# Schematic_Central_Unit_for_AgOpenGPS.net
KiCad netlist of a schematic drawn in EasyEDA
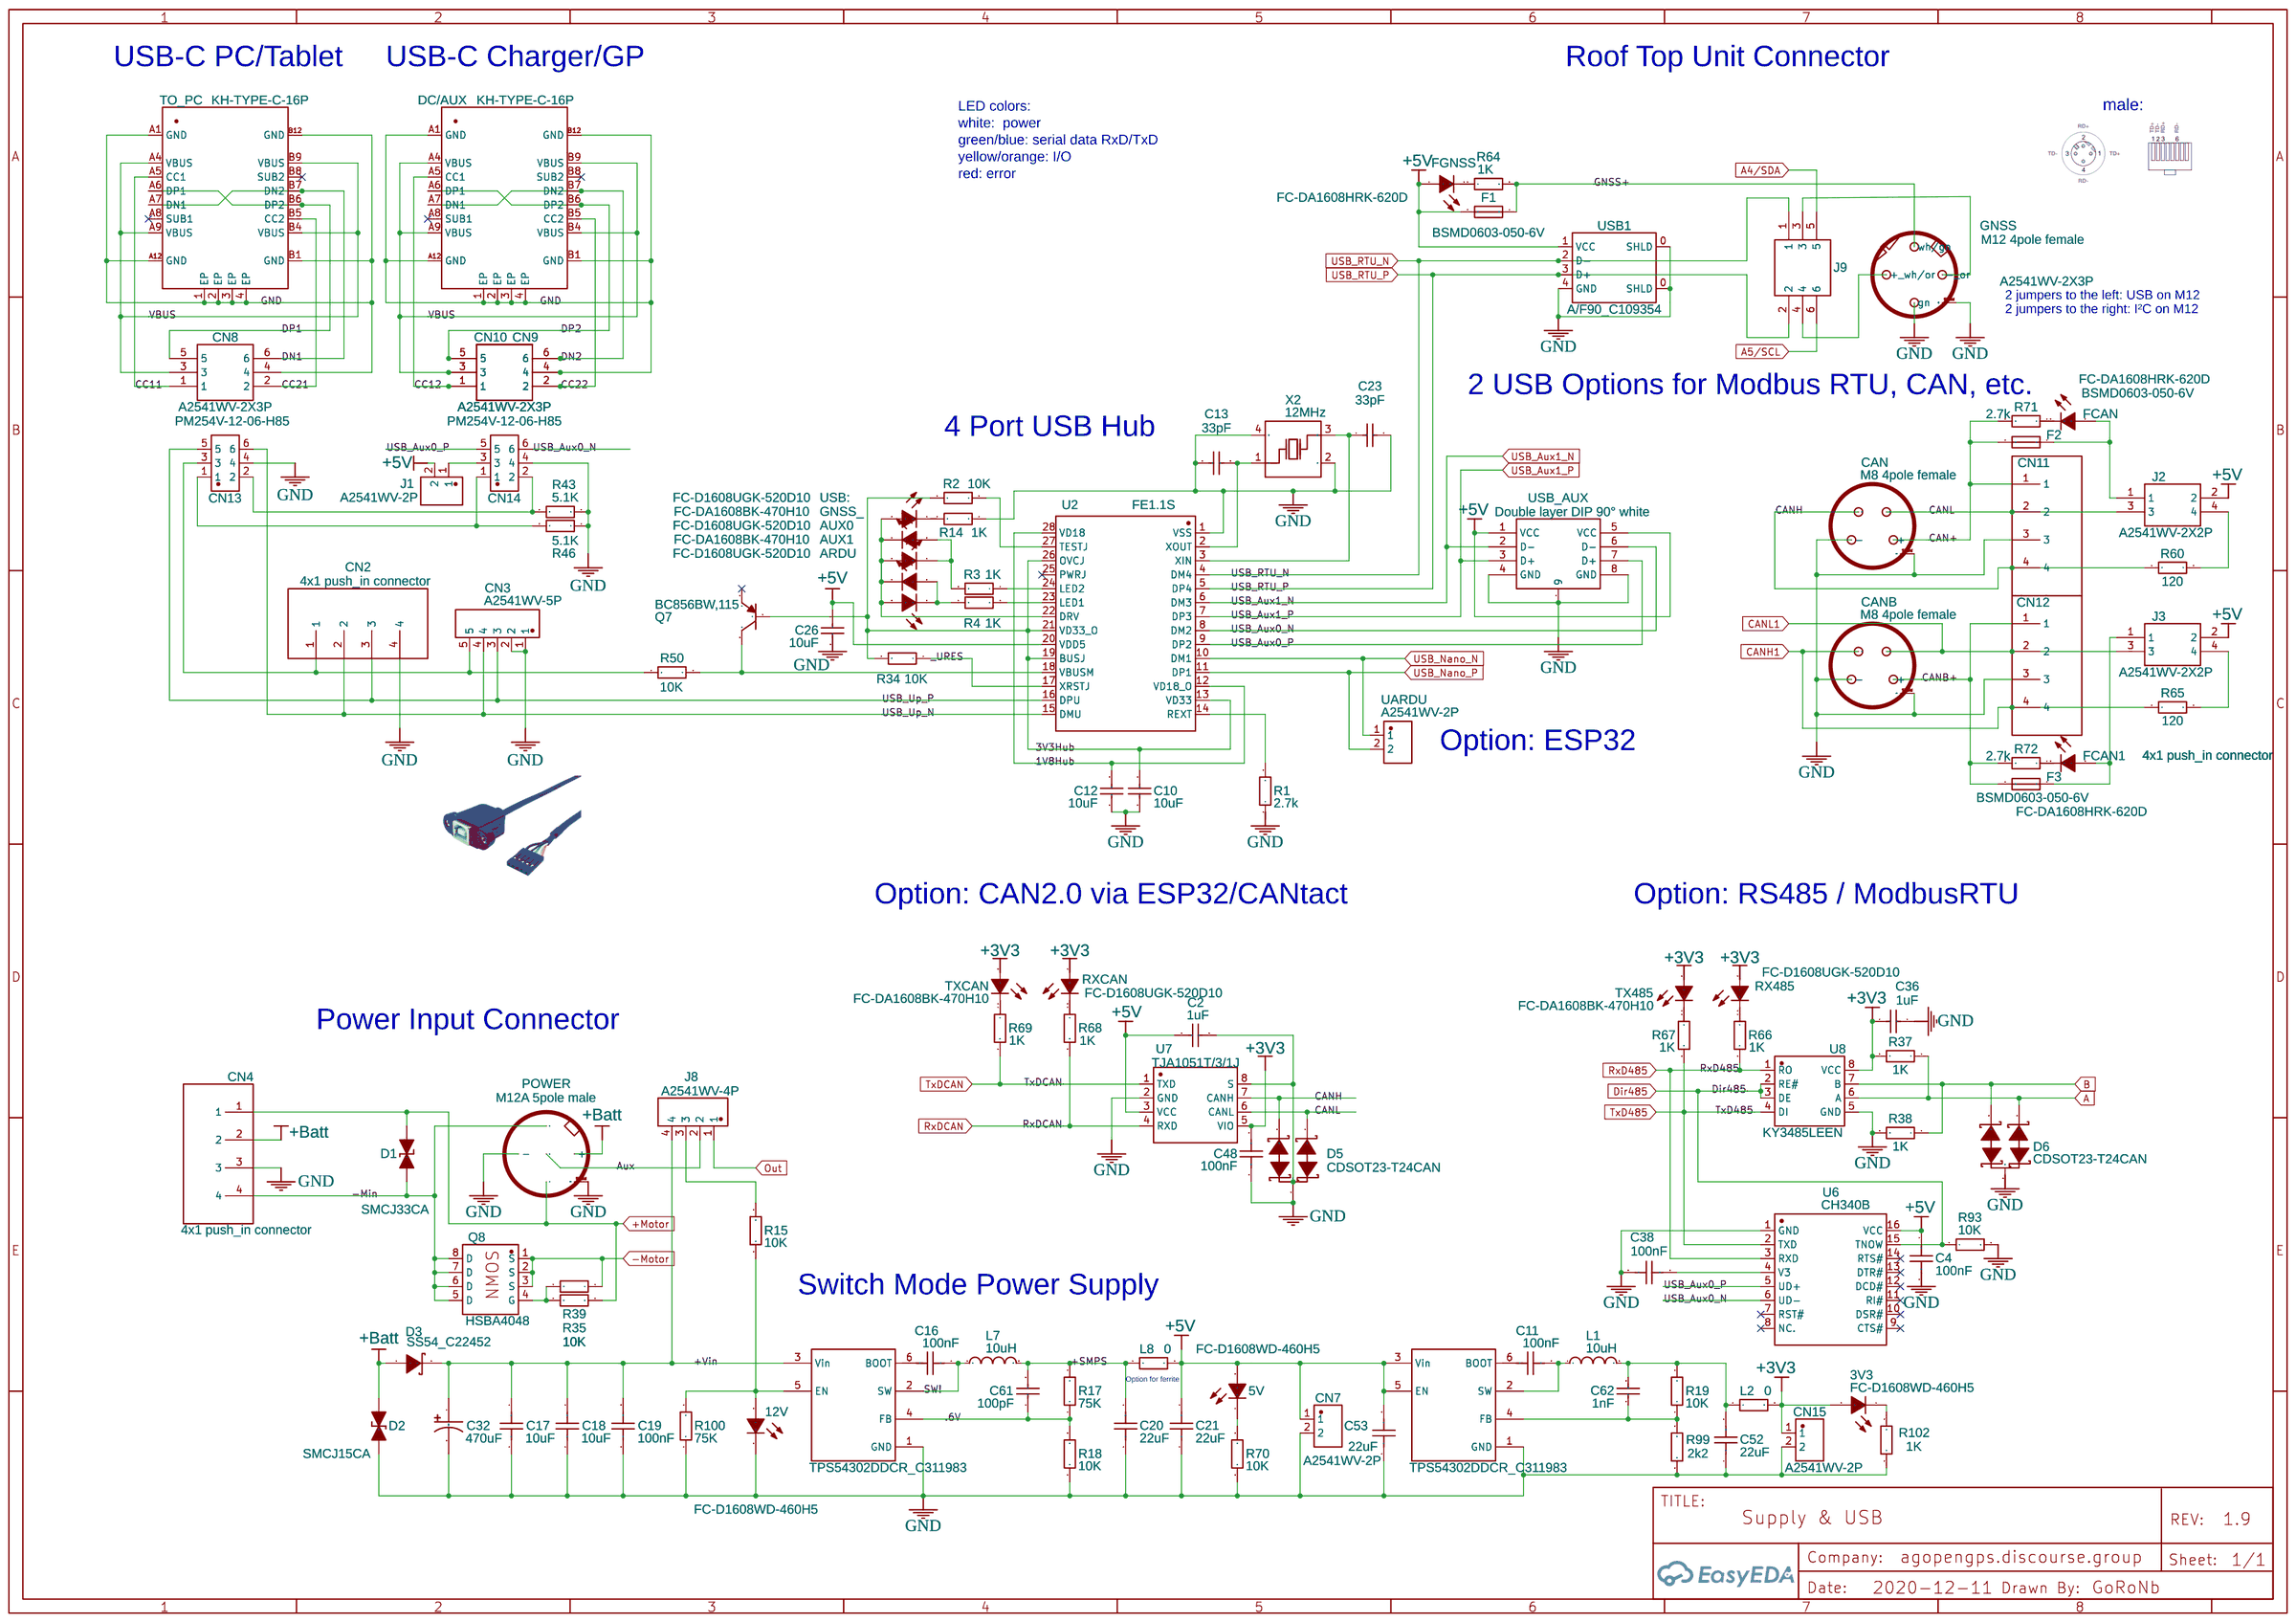
[diagram p0: Supply_USB]
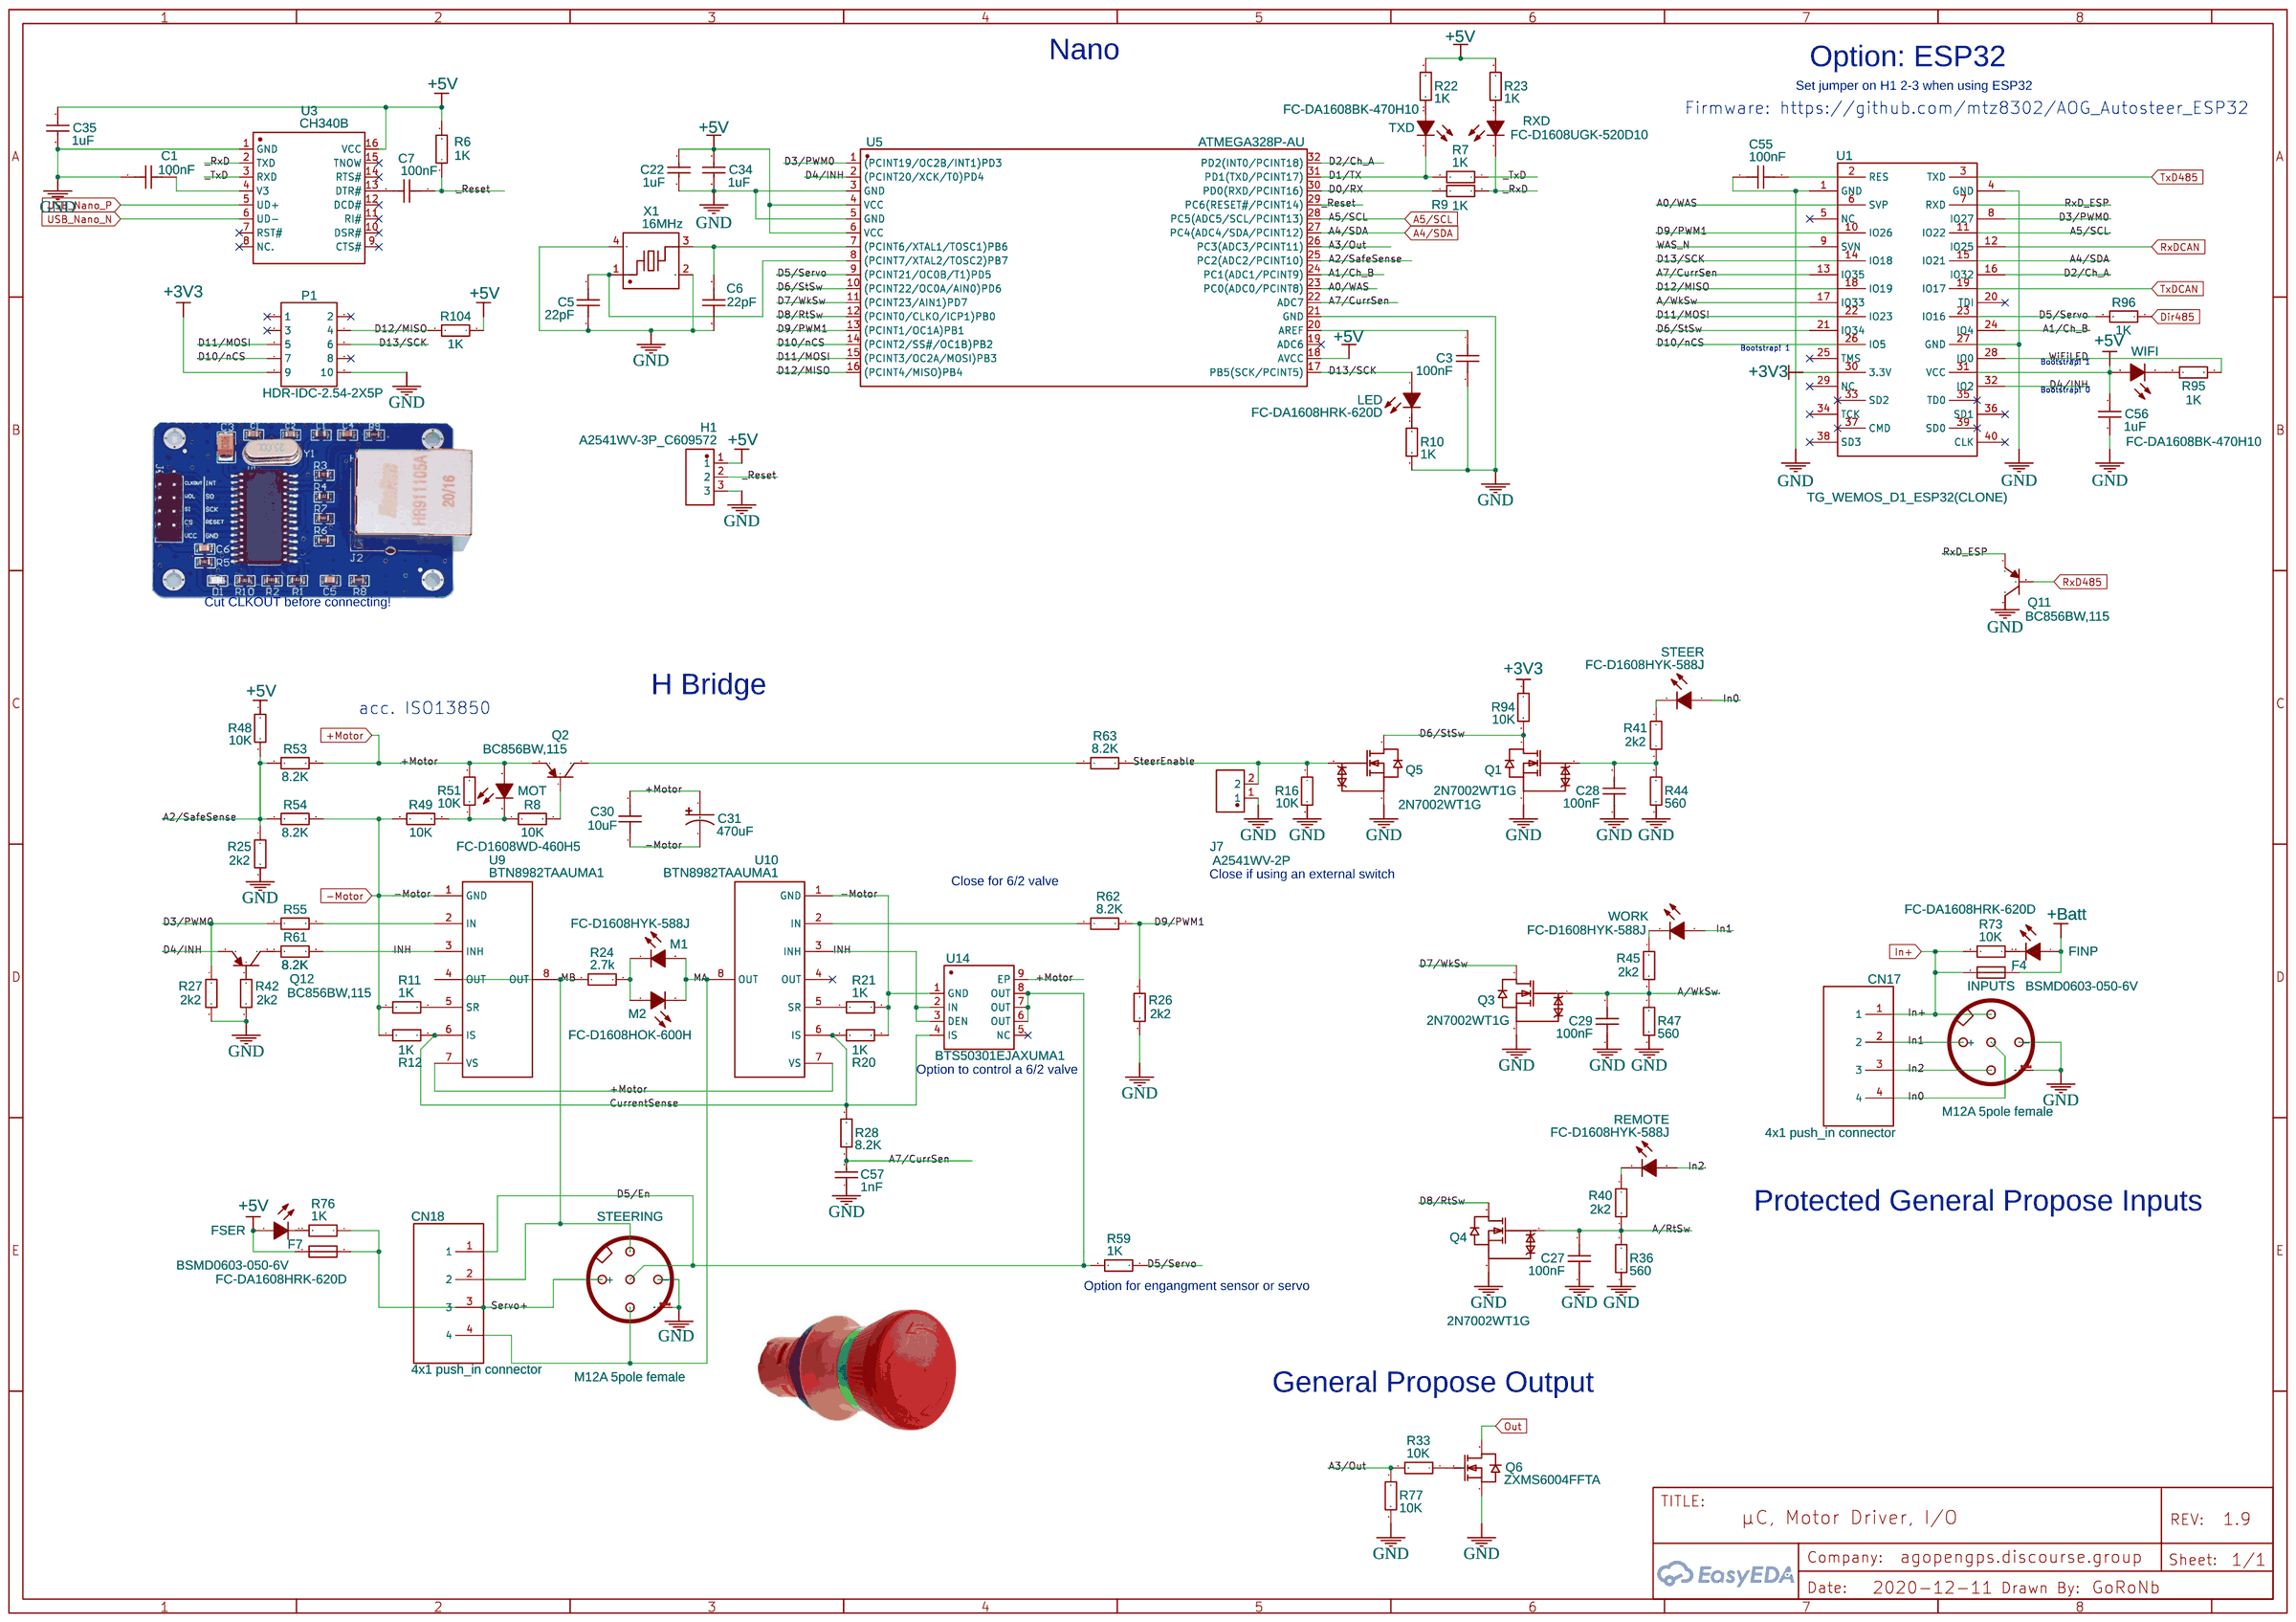
[diagram p1: Motor control]
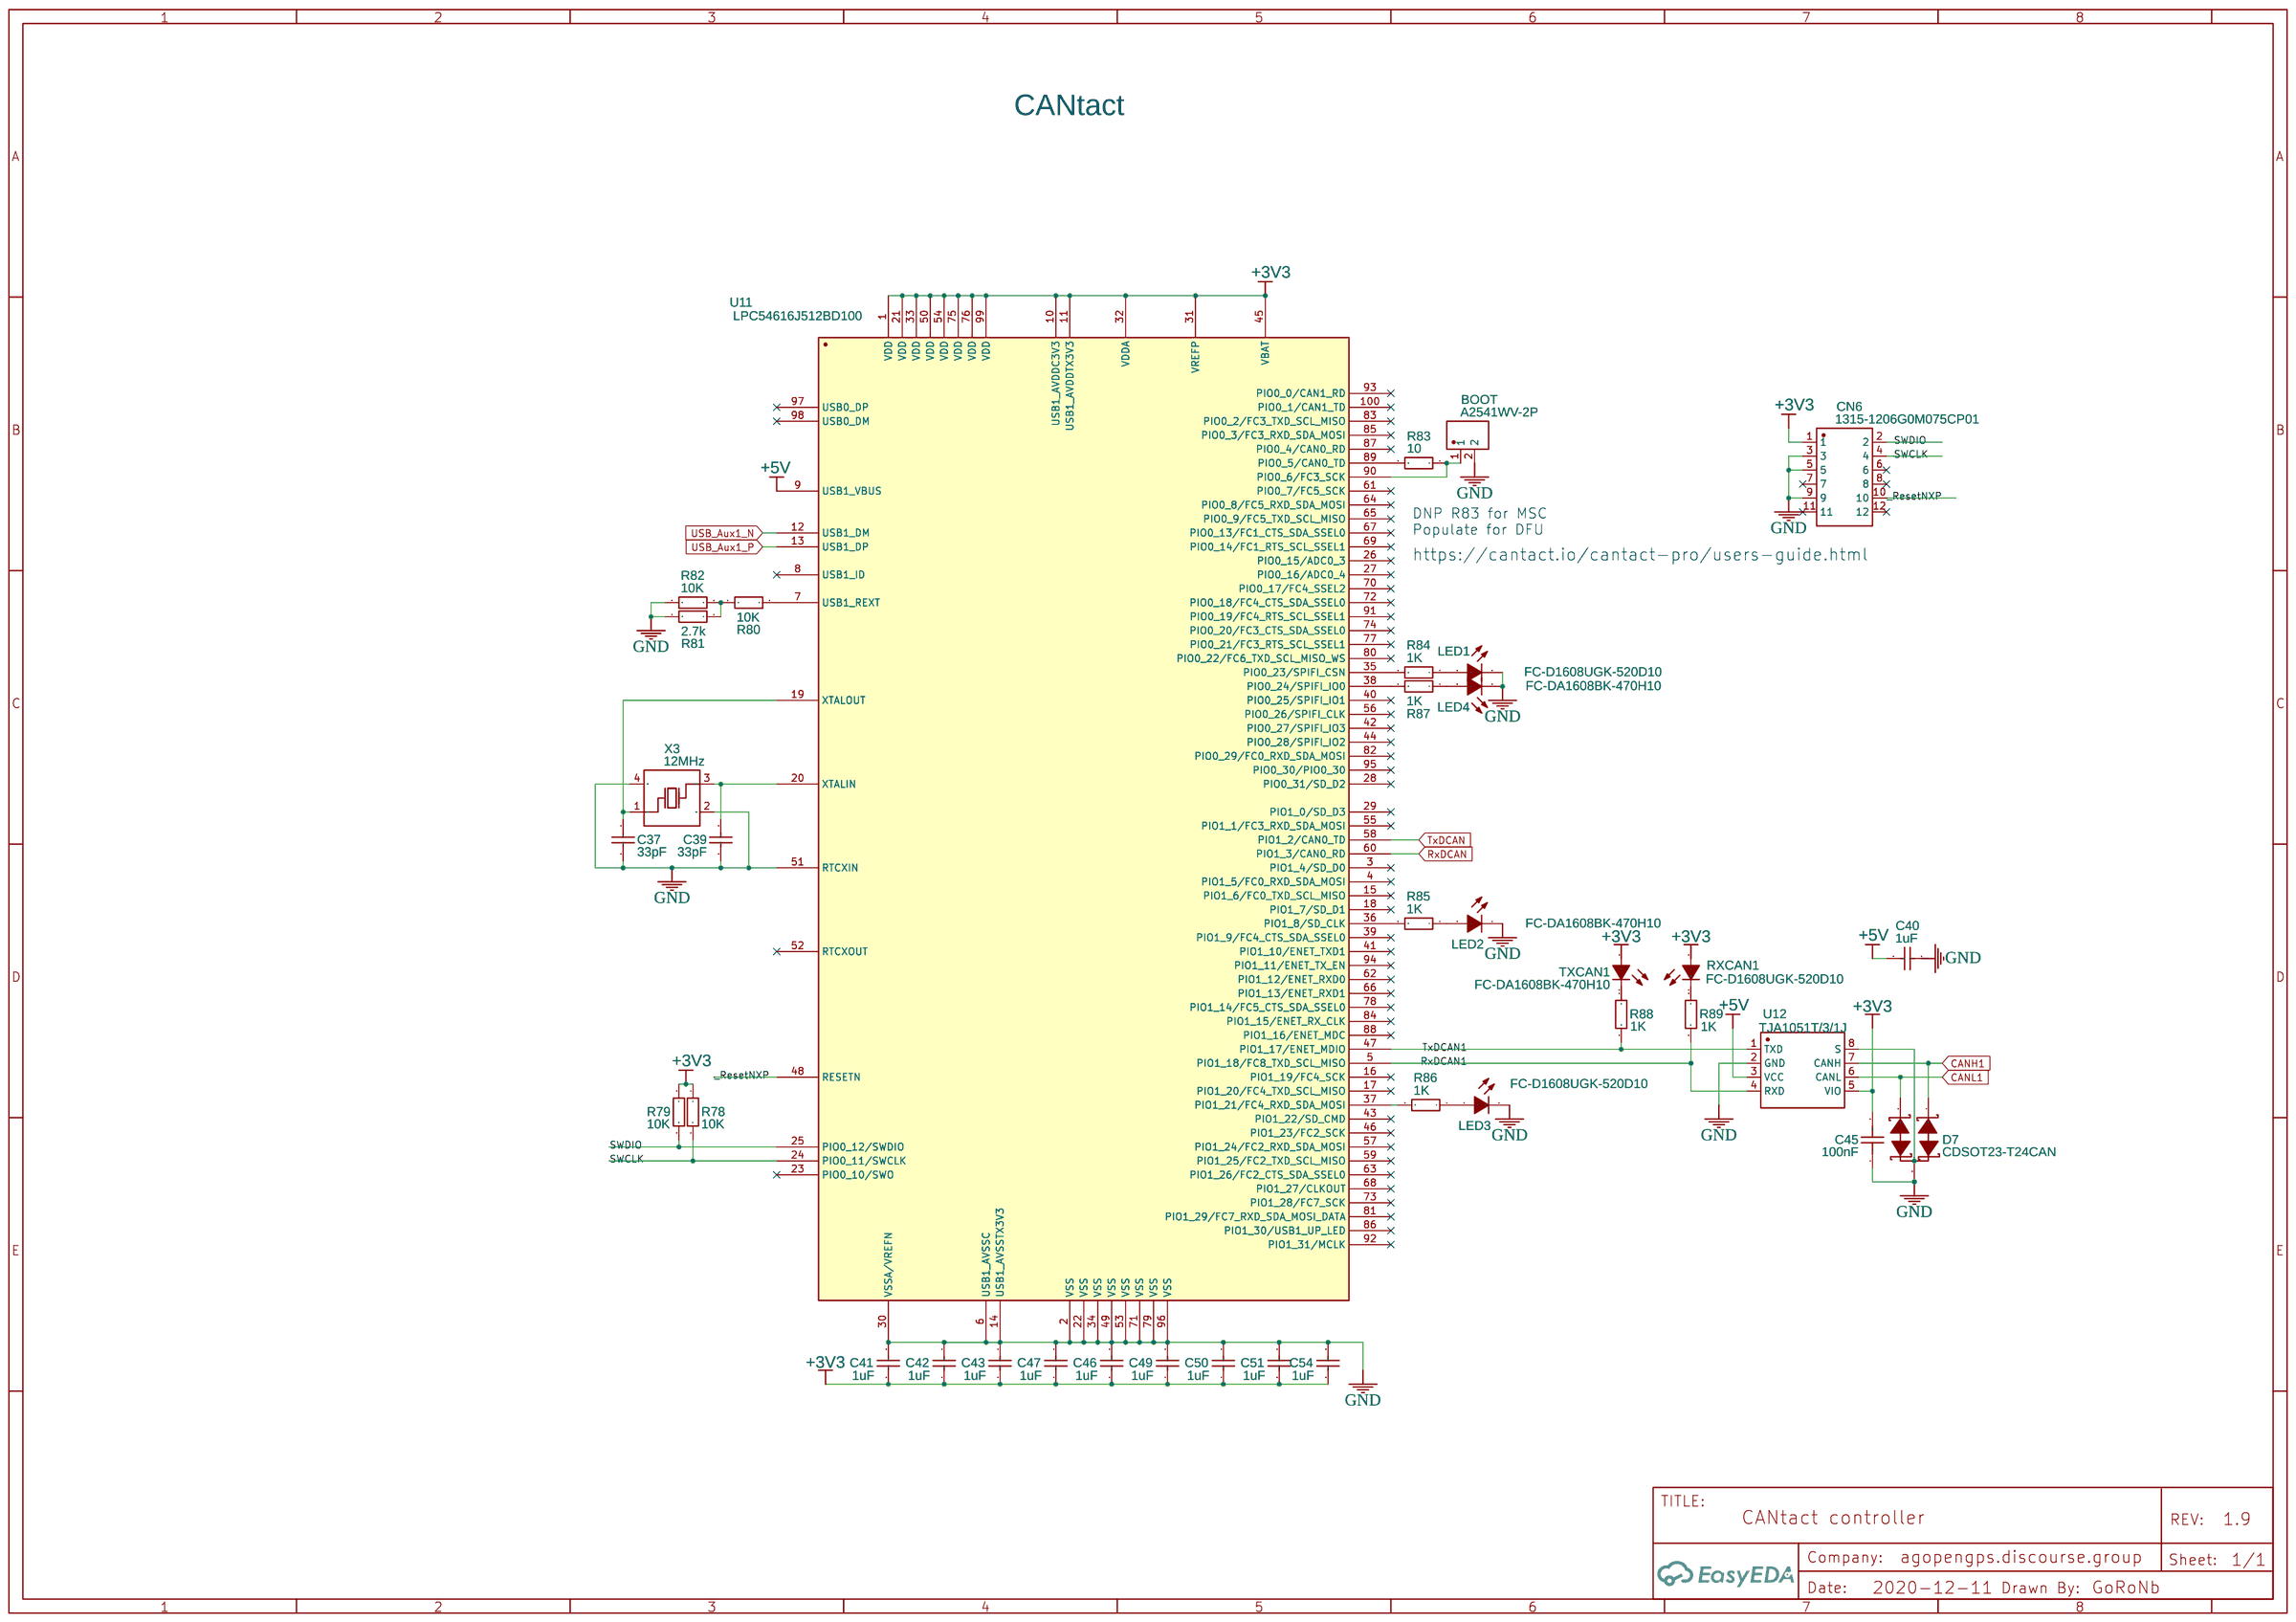
[diagram p2: CANtact]
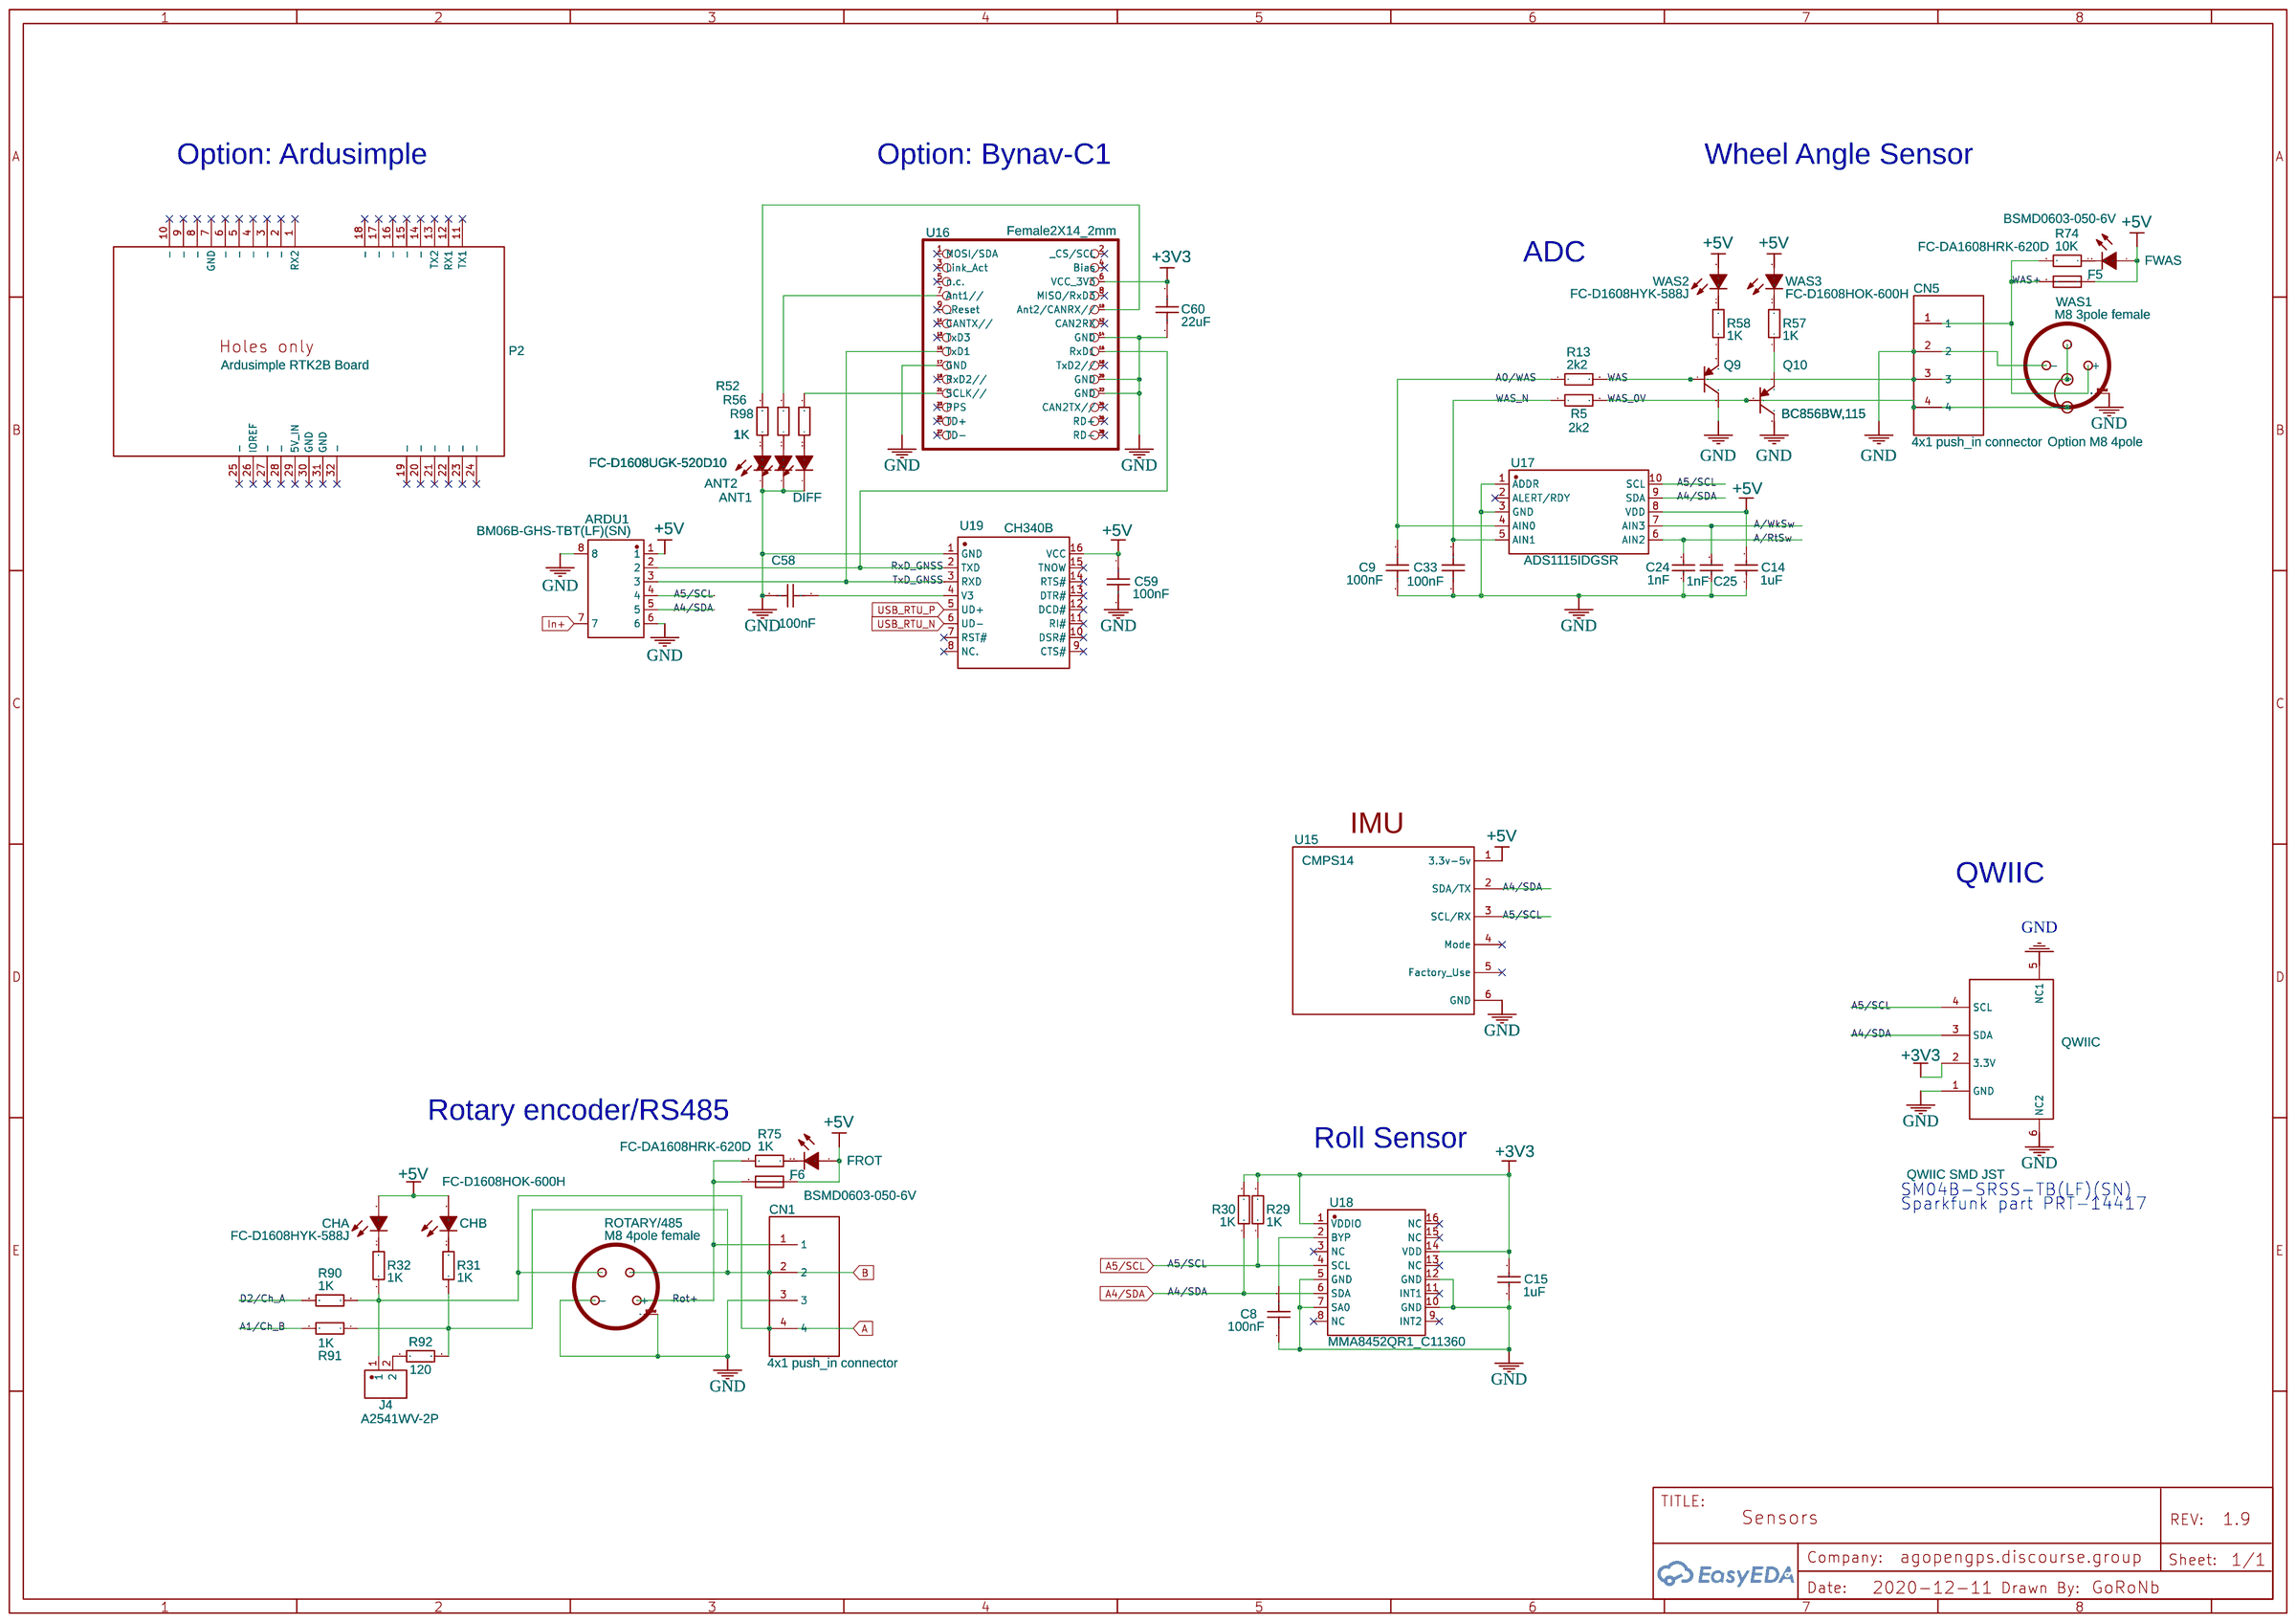
[diagram p3: Sensors]

(export (version "E")
  (design (tool "Eeschema 10.0.6"))
  (components
    (comp (ref "3V3")
      (value "FC-D1608WD-460H5")
      (fields (field (name "BOM_Supplier Part") "C84265"))
      (libsource (lib "") (part "FC-D1608WD-460H5_2"))
    )
    (comp (ref "5V")
      (value "FC-D1608WD-460H5")
      (fields (field (name "BOM_Supplier Part") "C84265"))
      (libsource (lib "") (part "FC-D1608WD-460H5_1"))
    )
    (comp (ref "12V")
      (value "FC-D1608WD-460H5")
      (fields (field (name "BOM_Supplier Part") "C84265"))
      (libsource (lib "") (part "FC-D1608WD-460H5"))
    )
    (comp (ref "ARDU")
      (value "FC-D1608UGK-520D10")
      (fields (field (name "BOM_Supplier Part") "C84267"))
      (libsource (lib "") (part "FC-D1608UGK-520D10_3"))
    )
    (comp (ref "AUX0")
      (value "FC-D1608UGK-520D10")
      (fields (field (name "BOM_Supplier Part") "C84267"))
      (libsource (lib "") (part "FC-D1608UGK-520D10_2"))
    )
    (comp (ref "AUX1")
      (value "FC-DA1608BK-470H10")
      (fields (field (name "BOM_Supplier Part") "C84266"))
      (libsource (lib "") (part "FC-DA1608BK-470H10"))
    )
    (comp (ref "C2")
      (value "1uF")
      (fields
        (field (name "BOM_Manufacturer Part") "CL10A105KP8NNNC")
        (field (name "BOM_Supplier Part") "C26413")
      )
      (libsource (lib "") (part "CL10A105KP8NNNC"))
    )
    (comp (ref "C4")
      (value "100nF")
      (fields
        (field (name "BOM_Manufacturer Part") "CC0603JRX7R8BB104")
        (field (name "BOM_Supplier Part") "C327087")
      )
      (libsource (lib "") (part "CC0603JRX7R8BB104_3"))
    )
    (comp (ref "C10")
      (value "10uF")
      (fields
        (field (name "BOM_Manufacturer Part") "0805X106K100")
        (field (name "BOM_Supplier Part") "C105505")
      )
      (libsource (lib "") (part "0805X106K100_2"))
    )
    (comp (ref "C11")
      (value "100nF")
      (fields
        (field (name "BOM_Manufacturer Part") "CC0603JRX7R8BB104")
        (field (name "BOM_Supplier Part") "C327087")
      )
      (libsource (lib "") (part "CC0603JRX7R8BB104"))
    )
    (comp (ref "C12")
      (value "10uF")
      (fields
        (field (name "BOM_Manufacturer Part") "0805X106K100")
        (field (name "BOM_Supplier Part") "C105505")
      )
      (libsource (lib "") (part "0805X106K100"))
    )
    (comp (ref "C13")
      (value "33pF")
      (fields
        (field (name "BOM_Manufacturer Part") "CL10C330JB8NNNC")
        (field (name "BOM_Supplier Part") "C1663")
      )
      (libsource (lib "") (part "CC0603JRNPO9BN330"))
    )
    (comp (ref "C16")
      (value "100nF")
      (fields
        (field (name "BOM_Manufacturer Part") "CC0603JRX7R8BB104")
        (field (name "BOM_Supplier Part") "C327087")
      )
      (libsource (lib "") (part "CC0603JRX7R8BB104"))
    )
    (comp (ref "C17")
      (value "10uF")
      (fields
        (field (name "BOM_Manufacturer Part") "TCC1206X7R106K250HT")
        (field (name "BOM_Supplier Part") "C380364")
      )
      (libsource (lib "") (part "TCC1206X7R106K250HT"))
    )
    (comp (ref "C18")
      (value "10uF")
      (fields
        (field (name "BOM_Manufacturer Part") "TCC1206X7R106K250HT")
        (field (name "BOM_Supplier Part") "C380364")
      )
      (libsource (lib "") (part "TCC1206X7R106K250HT"))
    )
    (comp (ref "C19")
      (value "100nF")
      (fields
        (field (name "BOM_Manufacturer Part") "CC0603JRX7R8BB104")
        (field (name "BOM_Supplier Part") "C327087")
      )
      (libsource (lib "") (part "CC0603JRX7R8BB104_1"))
    )
    (comp (ref "C20")
      (value "22uF")
      (fields
        (field (name "BOM_Manufacturer Part") "CL21A226MAQNNNE")
        (field (name "BOM_Supplier Part") "C45783")
      )
      (libsource (lib "") (part "CL21A226MAQNNNE"))
    )
    (comp (ref "C21")
      (value "22uF")
      (fields
        (field (name "BOM_Manufacturer Part") "CL21A226MAQNNNE")
        (field (name "BOM_Supplier Part") "C45783")
      )
      (libsource (lib "") (part "CL21A226MAQNNNE"))
    )
    (comp (ref "C23")
      (value "33pF")
      (fields
        (field (name "BOM_Manufacturer Part") "CL10C330JB8NNNC")
        (field (name "BOM_Supplier Part") "C1663")
      )
      (libsource (lib "") (part "CC0603JRNPO9BN330"))
    )
    (comp (ref "C26")
      (value "10uF")
      (fields
        (field (name "BOM_Manufacturer Part") "0805X106K100")
        (field (name "BOM_Supplier Part") "C105505")
      )
      (libsource (lib "") (part "0805X106K100_1"))
    )
    (comp (ref "C32")
      (value "470uF")
      (fields
        (field (name "BOM_Manufacturer Part") "HV471M016F105R")
        (field (name "BOM_Supplier Part") "C59924")
      )
      (libsource (lib "") (part "RT1E471M1010"))
    )
    (comp (ref "C36")
      (value "1uF")
      (fields
        (field (name "BOM_Manufacturer Part") "CL10A105KP8NNNC")
        (field (name "BOM_Supplier Part") "C26413")
      )
      (libsource (lib "") (part "CL10A105KP8NNNC"))
    )
    (comp (ref "C38")
      (value "100nF")
      (fields
        (field (name "BOM_Manufacturer Part") "CC0603JRX7R8BB104")
        (field (name "BOM_Supplier Part") "C327087")
      )
      (libsource (lib "") (part "CC0603JRX7R8BB104_2"))
    )
    (comp (ref "C48")
      (value "100nF")
      (fields
        (field (name "BOM_Manufacturer Part") "CC0603JRX7R8BB104")
        (field (name "BOM_Supplier Part") "C327087")
      )
      (libsource (lib "") (part "CC0603JRX7R8BB104_1"))
    )
    (comp (ref "C52")
      (value "22uF")
      (fields
        (field (name "BOM_Manufacturer Part") "CL21A226MAQNNNE")
        (field (name "BOM_Supplier Part") "C45783")
      )
      (libsource (lib "") (part "CL21A226MAQNNNE"))
    )
    (comp (ref "C53")
      (value "22uF")
      (fields
        (field (name "BOM_Manufacturer Part") "CL21A226MAQNNNE")
        (field (name "BOM_Supplier Part") "C45783")
      )
      (libsource (lib "") (part "CL21A226MAQNNNE"))
    )
    (comp (ref "C61")
      (value "100pF")
      (fields
        (field (name "BOM_Manufacturer Part") "CL10C101JB8NNNC")
        (field (name "BOM_Supplier Part") "C14858")
      )
      (libsource (lib "") (part "CL10C101JB8NNNC"))
    )
    (comp (ref "C62")
      (value "1nF")
      (fields
        (field (name "BOM_Manufacturer Part") "0603CG102F500NT")
        (field (name "BOM_Supplier Part") "C507408")
      )
      (libsource (lib "") (part "0603CG102F500NT"))
    )
    (comp (ref "CAN") (value "M8 4pole female") (libsource (lib "") (part "M8 4pole female_1")))
    (comp (ref "CANB") (value "M8 4pole female") (libsource (lib "") (part "M8 4pole female")))
    (comp (ref "CN2")
      (value "4x1 push_in connector")
      (fields
        (field (name "BOM_Manufacturer Part") "1825660000")
        (field (name "BOM_Supplier Part") "281-2044-ND")
      )
      (libsource (lib "") (part "4x1 push_in connector"))
    )
    (comp (ref "CN3")
      (value "A2541WV-5P")
      (fields (field (name "BOM_Supplier Part") "C225480"))
      (libsource (lib "") (part "A2541WV-5P"))
    )
    (comp (ref "CN4")
      (value "4x1 push_in connector")
      (fields
        (field (name "BOM_Manufacturer Part") "1825660000")
        (field (name "BOM_Supplier Part") "281-2044-ND")
      )
      (libsource (lib "") (part "4x1 push_in connector_2"))
    )
    (comp (ref "CN7")
      (value "A2541WV-2P")
      (fields (field (name "BOM_Supplier Part") "C225477"))
      (libsource (lib "") (part "A2541WV-2P"))
    )
    (comp (ref "CN8")
      (value "A2541WV-2X3P")
      (fields
        (field (name "BOM_Manufacturer Part") "A2541WV-2x3P")
        (field (name "BOM_Supplier Part") "C225518")
      )
      (libsource (lib "") (part "A2541WV-2X3P"))
    )
    (comp (ref "CN9")
      (value "A2541WV-2X3P")
      (fields
        (field (name "BOM_Manufacturer Part") "A2541WV-2x3P")
        (field (name "BOM_Supplier Part") "C225518")
      )
      (libsource (lib "") (part "A2541WV-2X3P"))
    )
    (comp (ref "CN10")
      (value "A2541WV-2X3P")
      (fields
        (field (name "BOM_Manufacturer Part") "A2541WV-2x3P")
        (field (name "BOM_Supplier Part") "C225518")
      )
      (libsource (lib "") (part "A2541WV-2X3P"))
    )
    (comp (ref "CN11")
      (value "4x1 push_in connector")
      (fields
        (field (name "BOM_Manufacturer Part") "1825660000")
        (field (name "BOM_Supplier Part") "281-2044-ND")
      )
      (libsource (lib "") (part "4x1 push_in connector_1"))
    )
    (comp (ref "CN12")
      (value "4x1 push_in connector")
      (fields
        (field (name "BOM_Manufacturer Part") "1825660000")
        (field (name "BOM_Supplier Part") "281-2044-ND")
      )
      (libsource (lib "") (part "4x1 push_in connector_1"))
    )
    (comp (ref "CN13")
      (value "PM254V-12-06-H85")
      (fields (field (name "BOM_Supplier Part") "C541853"))
      (libsource (lib "") (part "PM254V-12-06-H85"))
    )
    (comp (ref "CN14")
      (value "PM254V-12-06-H85")
      (fields (field (name "BOM_Supplier Part") "C541853"))
      (libsource (lib "") (part "PM254V-12-06-H85"))
    )
    (comp (ref "CN15")
      (value "A2541WV-2P")
      (fields (field (name "BOM_Supplier Part") "C225477"))
      (libsource (lib "") (part "A2541WV-2P"))
    )
    (comp (ref "D1")
      (value "SMCJ33CA")
      (fields (field (name "BOM_Supplier Part") "C310048"))
      (libsource (lib "") (part "SMCJ33CA_C310048"))
    )
    (comp (ref "D2")
      (value "SMCJ15CA")
      (fields (field (name "BOM_Supplier Part") "C310017"))
      (libsource (lib "") (part "SMCJ15CA_C310017"))
    )
    (comp (ref "D3")
      (value "SS54_C22452")
      (fields (field (name "BOM_Manufacturer Part") "SS54") (field (name "BOM_Supplier Part") "C22452"))
      (libsource (lib "") (part "SS54_C22452"))
    )
    (comp (ref "D5")
      (value "CDSOT23-T24CAN")
      (fields (field (name "BOM_Supplier Part") "C252430"))
      (libsource (lib "") (part "CDSOT23-T24CAN"))
    )
    (comp (ref "D6")
      (value "CDSOT23-T24CAN")
      (fields (field (name "BOM_Supplier Part") "C252430"))
      (libsource (lib "") (part "CDSOT23-T24CAN"))
    )
    (comp (ref "DC/AUX")
      (value "KH-TYPE-C-16P")
      (fields (field (name "BOM_Supplier Part") "C709357"))
      (libsource (lib "") (part "KH-TYPE-C-16P_1"))
    )
    (comp (ref "F1")
      (value "BSMD0603-050-6V")
      (fields (field (name "BOM_Supplier Part") "C883095"))
      (libsource (lib "") (part "BSMD0603-050-6V"))
    )
    (comp (ref "F2")
      (value "BSMD0603-050-6V")
      (fields (field (name "BOM_Supplier Part") "C883095"))
      (libsource (lib "") (part "BSMD0603-050-6V"))
    )
    (comp (ref "F3")
      (value "BSMD0603-050-6V")
      (fields (field (name "BOM_Supplier Part") "C883095"))
      (libsource (lib "") (part "BSMD0603-050-6V"))
    )
    (comp (ref "FCAN")
      (value "FC-DA1608HRK-620D")
      (fields (field (name "BOM_Supplier Part") "C84263"))
      (libsource (lib "") (part "FC-DA1608HRK-620D"))
    )
    (comp (ref "FCAN1")
      (value "FC-DA1608HRK-620D")
      (fields (field (name "BOM_Supplier Part") "C84263"))
      (libsource (lib "") (part "FC-DA1608HRK-620D"))
    )
    (comp (ref "FGNSS")
      (value "FC-DA1608HRK-620D")
      (fields (field (name "BOM_Supplier Part") "C84263"))
      (libsource (lib "") (part "FC-DA1608HRK-620D_1"))
    )
    (comp (ref "GNSS") (value "M12 4pole female") (libsource (lib "") (part "M12 4pole female")))
    (comp (ref "GNSS_")
      (value "FC-DA1608BK-470H10")
      (fields (field (name "BOM_Supplier Part") "C84266"))
      (libsource (lib "") (part "FC-DA1608BK-470H10_3"))
    )
    (comp (ref "J1")
      (value "A2541WV-2P")
      (fields (field (name "BOM_Supplier Part") "C225477"))
      (libsource (lib "") (part "A2541WV-2P_1"))
    )
    (comp (ref "J2")
      (value "A2541WV-2X2P")
      (fields
        (field (name "BOM_Manufacturer Part") "A2541WV-2x2P")
        (field (name "BOM_Supplier Part") "C225517")
      )
      (libsource (lib "") (part "A2541WV-2X2P"))
    )
    (comp (ref "J3")
      (value "A2541WV-2X2P")
      (fields
        (field (name "BOM_Manufacturer Part") "A2541WV-2x2P")
        (field (name "BOM_Supplier Part") "C225517")
      )
      (libsource (lib "") (part "A2541WV-2X2P"))
    )
    (comp (ref "J8")
      (value "A2541WV-4P")
      (fields (field (name "BOM_Supplier Part") "C225479"))
      (libsource (lib "") (part "A2541WV-4P"))
    )
    (comp (ref "J9")
      (value "A2541WV-2X3P")
      (fields
        (field (name "BOM_Manufacturer Part") "A2541WV-2x3P")
        (field (name "BOM_Supplier Part") "C225518")
      )
      (libsource (lib "") (part "A2541WV-2X3P_1"))
    )
    (comp (ref "L1")
      (value "10uH")
      (fields
        (field (name "BOM_Manufacturer Part") "MWSA0503-100MT")
        (field (name "BOM_Supplier Part") "C139506")
      )
      (libsource (lib "") (part "MWSA0503-100MT"))
    )
    (comp (ref "L2")
      (value "0")
      (fields
        (field (name "BOM_Manufacturer Part") "0603WAF0000T5E")
        (field (name "BOM_Supplier Part") "C21189")
      )
      (libsource (lib "") (part "0603WAF0000T5E"))
    )
    (comp (ref "L7")
      (value "10uH")
      (fields
        (field (name "BOM_Manufacturer Part") "MWSA0503-100MT")
        (field (name "BOM_Supplier Part") "C139506")
      )
      (libsource (lib "") (part "MWSA0503-100MT_1"))
    )
    (comp (ref "L8")
      (value "0")
      (fields
        (field (name "BOM_Manufacturer Part") "0603WAF0000T5E")
        (field (name "BOM_Supplier Part") "C21189")
      )
      (libsource (lib "") (part "0603WAF0000T5E"))
    )
    (comp (ref "POWER") (value "M12A 5pole male") (libsource (lib "") (part "M12A 5pole male")))
    (comp (ref "Q7")
      (value "BC856BW,115")
      (fields (field (name "BOM_Supplier Part") "C28063"))
      (libsource (lib "") (part "BC856BW,115"))
    )
    (comp (ref "Q8")
      (value "HSBA4048")
      (fields (field (name "BOM_Supplier Part") "C508827"))
      (libsource (lib "") (part "HSBA4048"))
    )
    (comp (ref "R1")
      (value "2.7k")
      (fields (field (name "BOM_Manufacturer Part") "RTT03272JTP"))
      (libsource (lib "") (part "RTT03473JTP_1"))
    )
    (comp (ref "R2")
      (value "10K")
      (fields
        (field (name "BOM_Manufacturer Part") "RTT03103JTP")
        (field (name "BOM_Supplier Part") "C103210")
      )
      (libsource (lib "") (part "RTT03103JTP"))
    )
    (comp (ref "R3")
      (value "1K")
      (fields
        (field (name "BOM_Manufacturer Part") "RTT03102JTP")
        (field (name "BOM_Supplier Part") "C103209")
      )
      (libsource (lib "") (part "RTT03102JTP_1"))
    )
    (comp (ref "R4")
      (value "1K")
      (fields
        (field (name "BOM_Manufacturer Part") "RTT03102JTP")
        (field (name "BOM_Supplier Part") "C103209")
      )
      (libsource (lib "") (part "RTT03102JTP"))
    )
    (comp (ref "R14")
      (value "1K")
      (fields
        (field (name "BOM_Manufacturer Part") "RTT03102JTP")
        (field (name "BOM_Supplier Part") "C103209")
      )
      (libsource (lib "") (part "RTT03102JTP_1"))
    )
    (comp (ref "R15")
      (value "10K")
      (fields
        (field (name "BOM_Manufacturer Part") "RTT03103JTP")
        (field (name "BOM_Supplier Part") "C103210")
      )
      (libsource (lib "") (part "RTT03103JTP_1"))
    )
    (comp (ref "R17")
      (value "75K")
      (fields
        (field (name "BOM_Manufacturer Part") "0603WAF7502T5E")
        (field (name "BOM_Supplier Part") "C23242")
      )
      (libsource (lib "") (part "0603WAF7502T5E"))
    )
    (comp (ref "R18")
      (value "10K")
      (fields
        (field (name "BOM_Manufacturer Part") "RTT03103JTP")
        (field (name "BOM_Supplier Part") "C103210")
      )
      (libsource (lib "") (part "RTT03103JTP_1"))
    )
    (comp (ref "R19")
      (value "10K")
      (fields
        (field (name "BOM_Manufacturer Part") "RTT03103JTP")
        (field (name "BOM_Supplier Part") "C103210")
      )
      (libsource (lib "") (part "RTT03103JTP_1"))
    )
    (comp (ref "R34")
      (value "10K")
      (fields
        (field (name "BOM_Manufacturer Part") "RTT03103JTP")
        (field (name "BOM_Supplier Part") "C103210")
      )
      (libsource (lib "") (part "RTT03103JTP"))
    )
    (comp (ref "R35")
      (value "10K")
      (fields
        (field (name "BOM_Manufacturer Part") "RTT03103JTP")
        (field (name "BOM_Supplier Part") "C103210")
      )
      (libsource (lib "") (part "RTT03103JTP"))
    )
    (comp (ref "R37")
      (value "1K")
      (fields
        (field (name "BOM_Manufacturer Part") "RTT03102JTP")
        (field (name "BOM_Supplier Part") "C103209")
      )
      (libsource (lib "") (part "RTT03102JTP_1"))
    )
    (comp (ref "R38")
      (value "1K")
      (fields
        (field (name "BOM_Manufacturer Part") "RTT03102JTP")
        (field (name "BOM_Supplier Part") "C103209")
      )
      (libsource (lib "") (part "RTT03102JTP_1"))
    )
    (comp (ref "R39")
      (value "10K")
      (fields
        (field (name "BOM_Manufacturer Part") "RTT03103JTP")
        (field (name "BOM_Supplier Part") "C103210")
      )
      (libsource (lib "") (part "RTT03103JTP"))
    )
    (comp (ref "R43")
      (value "5.1K")
      (fields
        (field (name "BOM_Manufacturer Part") "0603WAF5101T5E")
        (field (name "BOM_Supplier Part") "C23186")
      )
      (libsource (lib "") (part "0603WAF5101T5E"))
    )
    (comp (ref "R46")
      (value "5.1K")
      (fields
        (field (name "BOM_Manufacturer Part") "0603WAF5101T5E")
        (field (name "BOM_Supplier Part") "C23186")
      )
      (libsource (lib "") (part "0603WAF5101T5E"))
    )
    (comp (ref "R50")
      (value "10K")
      (fields
        (field (name "BOM_Manufacturer Part") "RTT03103JTP")
        (field (name "BOM_Supplier Part") "C103210")
      )
      (libsource (lib "") (part "RTT03103JTP_2"))
    )
    (comp (ref "R60")
      (value "120")
      (fields
        (field (name "BOM_Manufacturer Part") "RTT06121JTP")
        (field (name "BOM_Supplier Part") "C104621")
      )
      (libsource (lib "") (part "RTT06121JTP"))
    )
    (comp (ref "R64")
      (value "1K")
      (fields
        (field (name "BOM_Manufacturer Part") "RTT03102JTP")
        (field (name "BOM_Supplier Part") "C103209")
      )
      (libsource (lib "") (part "RTT03102JTP"))
    )
    (comp (ref "R65")
      (value "120")
      (fields
        (field (name "BOM_Manufacturer Part") "RTT06121JTP")
        (field (name "BOM_Supplier Part") "C104621")
      )
      (libsource (lib "") (part "RTT06121JTP"))
    )
    (comp (ref "R66")
      (value "1K")
      (fields
        (field (name "BOM_Manufacturer Part") "RTT03102JTP")
        (field (name "BOM_Supplier Part") "C103209")
      )
      (libsource (lib "") (part "RTT03102JTP_2"))
    )
    (comp (ref "R67")
      (value "1K")
      (fields
        (field (name "BOM_Manufacturer Part") "RTT03102JTP")
        (field (name "BOM_Supplier Part") "C103209")
      )
      (libsource (lib "") (part "RTT03102JTP_2"))
    )
    (comp (ref "R68")
      (value "1K")
      (fields
        (field (name "BOM_Manufacturer Part") "RTT03102JTP")
        (field (name "BOM_Supplier Part") "C103209")
      )
      (libsource (lib "") (part "RTT03102JTP_2"))
    )
    (comp (ref "R69")
      (value "1K")
      (fields
        (field (name "BOM_Manufacturer Part") "RTT03102JTP")
        (field (name "BOM_Supplier Part") "C103209")
      )
      (libsource (lib "") (part "RTT03102JTP_2"))
    )
    (comp (ref "R70")
      (value "10K")
      (fields
        (field (name "BOM_Manufacturer Part") "RTT03103JTP")
        (field (name "BOM_Supplier Part") "C103210")
      )
      (libsource (lib "") (part "RTT03103JTP_1"))
    )
    (comp (ref "R71")
      (value "2.7k")
      (fields (field (name "BOM_Manufacturer Part") "RTT03272JTP"))
      (libsource (lib "") (part "RTT03473JTP"))
    )
    (comp (ref "R72")
      (value "2.7k")
      (fields (field (name "BOM_Manufacturer Part") "RTT03272JTP"))
      (libsource (lib "") (part "RTT03473JTP"))
    )
    (comp (ref "R93")
      (value "10K")
      (fields
        (field (name "BOM_Manufacturer Part") "RTT03103JTP")
        (field (name "BOM_Supplier Part") "C103210")
      )
      (libsource (lib "") (part "RTT03103JTP_2"))
    )
    (comp (ref "R99")
      (value "2k2")
      (fields
        (field (name "BOM_Manufacturer Part") "RTT03222JTP")
        (field (name "BOM_Supplier Part") "C103203")
      )
      (libsource (lib "") (part "RTT03100JTP"))
    )
    (comp (ref "R100")
      (value "75K")
      (fields
        (field (name "BOM_Manufacturer Part") "0603WAF7502T5E")
        (field (name "BOM_Supplier Part") "C23242")
      )
      (libsource (lib "") (part "0603WAF7502T5E"))
    )
    (comp (ref "R102")
      (value "1K")
      (fields
        (field (name "BOM_Manufacturer Part") "RTT03102JTP")
        (field (name "BOM_Supplier Part") "C103209")
      )
      (libsource (lib "") (part "RTT03102JTP_2"))
    )
    (comp (ref "RX485")
      (value "FC-D1608UGK-520D10")
      (fields (field (name "BOM_Supplier Part") "C84267"))
      (libsource (lib "") (part "FC-D1608UGK-520D10_1"))
    )
    (comp (ref "RXCAN")
      (value "FC-D1608UGK-520D10")
      (fields (field (name "BOM_Supplier Part") "C84267"))
      (libsource (lib "") (part "FC-D1608UGK-520D10_4"))
    )
    (comp (ref "TO_PC")
      (value "KH-TYPE-C-16P")
      (fields (field (name "BOM_Supplier Part") "C709357"))
      (libsource (lib "") (part "KH-TYPE-C-16P"))
    )
    (comp (ref "TX485")
      (value "FC-DA1608BK-470H10")
      (fields (field (name "BOM_Supplier Part") "C84266"))
      (libsource (lib "") (part "FC-DA1608BK-470H10_2"))
    )
    (comp (ref "TXCAN")
      (value "FC-DA1608BK-470H10")
      (fields (field (name "BOM_Supplier Part") "C84266"))
      (libsource (lib "") (part "FC-DA1608BK-470H10_1"))
    )
    (comp (ref "U2")
      (value "FE1.1S")
      (fields (field (name "BOM_Supplier Part") "C9359"))
      (libsource (lib "") (part "FE1.1S"))
    )
    (comp (ref "U4")
      (value "TPS54302DDCR_C311983")
      (fields
        (field (name "BOM_Manufacturer Part") "TPS54302DDCR")
        (field (name "BOM_Supplier Part") "C311983")
      )
      (libsource (lib "") (part "TPS56339"))
    )
    (comp (ref "U6")
      (value "CH340B")
      (fields (field (name "BOM_Supplier Part") "C81010"))
      (libsource (lib "") (part "CH340B"))
    )
    (comp (ref "U7")
      (value "TJA1051T/3/1J")
      (fields (field (name "BOM_Supplier Part") "C38695"))
      (libsource (lib "") (part "TJA1051T/3/1J"))
    )
    (comp (ref "U8")
      (value "KY3485LEEN")
      (fields (field (name "BOM_Supplier Part") "C428902"))
      (libsource (lib "") (part "KY3485LEEN"))
    )
    (comp (ref "U13")
      (value "TPS54302DDCR_C311983")
      (fields
        (field (name "BOM_Manufacturer Part") "TPS54302DDCR")
        (field (name "BOM_Supplier Part") "C311983")
      )
      (libsource (lib "") (part "TPS56339"))
    )
    (comp (ref "UARDU")
      (value "A2541WV-2P")
      (fields (field (name "BOM_Supplier Part") "C225477"))
      (libsource (lib "") (part "A2541WV-2P_2"))
    )
    (comp (ref "USB1")
      (value "A/F90_C109354")
      (fields (field (name "BOM_Supplier Part") "C109354"))
      (libsource (lib "") (part "A/F90_C109354"))
    )
    (comp (ref "USB:")
      (value "FC-D1608UGK-520D10")
      (fields (field (name "BOM_Supplier Part") "C84267"))
      (libsource (lib "") (part "FC-D1608UGK-520D10"))
    )
    (comp (ref "USB_AUX")
      (value "Double layer DIP 90° white")
      (fields (field (name "BOM_Supplier Part") "C2341"))
      (libsource (lib "") (part "Double layer DIP 90° white"))
    )
    (comp (ref "X2")
      (value "12MHz")
      (fields
        (field (name "BOM_Manufacturer Part") "X322512MSB4SI")
        (field (name "BOM_Supplier Part") "C9002")
      )
      (libsource (lib "") (part "X322512MSB4SI"))
    )
    (comp (ref "C1")
      (value "100nF")
      (fields
        (field (name "BOM_Manufacturer Part") "CC0603JRX7R8BB104")
        (field (name "BOM_Supplier Part") "C327087")
      )
      (libsource (lib "") (part "CC0603JRX7R8BB104_1"))
    )
    (comp (ref "C3")
      (value "100nF")
      (fields
        (field (name "BOM_Manufacturer Part") "CC0603JRX7R8BB104")
        (field (name "BOM_Supplier Part") "C327087")
      )
      (libsource (lib "") (part "CC0603JRX7R8BB104_3"))
    )
    (comp (ref "C5")
      (value "22pF")
      (fields
        (field (name "BOM_Manufacturer Part") "TCC0603COG220J500CT")
        (field (name "BOM_Supplier Part") "C376775")
      )
      (libsource (lib "") (part "TCC0603COG220J500CT"))
    )
    (comp (ref "C6")
      (value "22pF")
      (fields
        (field (name "BOM_Manufacturer Part") "TCC0603COG220J500CT")
        (field (name "BOM_Supplier Part") "C376775")
      )
      (libsource (lib "") (part "TCC0603COG220J500CT_1"))
    )
    (comp (ref "C7")
      (value "100nF")
      (fields
        (field (name "BOM_Manufacturer Part") "CC0603JRX7R8BB104")
        (field (name "BOM_Supplier Part") "C327087")
      )
      (libsource (lib "") (part "CC0603JRX7R8BB104_1"))
    )
    (comp (ref "C22")
      (value "1uF")
      (fields
        (field (name "BOM_Manufacturer Part") "CL10A105KP8NNNC")
        (field (name "BOM_Supplier Part") "C26413")
      )
      (libsource (lib "") (part "CL10A105KP8NNNC"))
    )
    (comp (ref "C27")
      (value "100nF")
      (fields
        (field (name "BOM_Manufacturer Part") "CC0603JRX7R8BB104")
        (field (name "BOM_Supplier Part") "C327087")
      )
      (libsource (lib "") (part "CC0603JRX7R8BB104"))
    )
    (comp (ref "C28")
      (value "100nF")
      (fields
        (field (name "BOM_Manufacturer Part") "CC0603JRX7R8BB104")
        (field (name "BOM_Supplier Part") "C327087")
      )
      (libsource (lib "") (part "CC0603JRX7R8BB104"))
    )
    (comp (ref "C29")
      (value "100nF")
      (fields
        (field (name "BOM_Manufacturer Part") "CC0603JRX7R8BB104")
        (field (name "BOM_Supplier Part") "C327087")
      )
      (libsource (lib "") (part "CC0603JRX7R8BB104"))
    )
    (comp (ref "C30")
      (value "10uF")
      (fields
        (field (name "BOM_Manufacturer Part") "TCC1206X7R106K250HT")
        (field (name "BOM_Supplier Part") "C380364")
      )
      (libsource (lib "") (part "TCC1206X7R106K250HT"))
    )
    (comp (ref "C31")
      (value "470uF")
      (fields
        (field (name "BOM_Manufacturer Part") "HV471M016F105R")
        (field (name "BOM_Supplier Part") "C59924")
      )
      (libsource (lib "") (part "RT1E471M1010"))
    )
    (comp (ref "C34")
      (value "1uF")
      (fields
        (field (name "BOM_Manufacturer Part") "CL10A105KP8NNNC")
        (field (name "BOM_Supplier Part") "C26413")
      )
      (libsource (lib "") (part "CL10A105KP8NNNC_1"))
    )
    (comp (ref "C35")
      (value "1uF")
      (fields
        (field (name "BOM_Manufacturer Part") "CL10A105KP8NNNC")
        (field (name "BOM_Supplier Part") "C26413")
      )
      (libsource (lib "") (part "CL10A105KP8NNNC_1"))
    )
    (comp (ref "C55")
      (value "100nF")
      (fields
        (field (name "BOM_Manufacturer Part") "CC0603JRX7R8BB104")
        (field (name "BOM_Supplier Part") "C327087")
      )
      (libsource (lib "") (part "CC0603JRX7R8BB104_2"))
    )
    (comp (ref "C56")
      (value "1uF")
      (fields
        (field (name "BOM_Manufacturer Part") "CL10A105KP8NNNC")
        (field (name "BOM_Supplier Part") "C26413")
      )
      (libsource (lib "") (part "CL10A105KP8NNNC_1"))
    )
    (comp (ref "C57")
      (value "1nF")
      (fields
        (field (name "BOM_Manufacturer Part") "0603CG102F500NT")
        (field (name "BOM_Supplier Part") "C507408")
      )
      (libsource (lib "") (part "0603CG102F500NT"))
    )
    (comp (ref "CN17")
      (value "4x1 push_in connector")
      (fields
        (field (name "BOM_Manufacturer Part") "1825660000")
        (field (name "BOM_Supplier Part") "281-2044-ND")
      )
      (libsource (lib "") (part "4x1 push_in connector"))
    )
    (comp (ref "CN18")
      (value "4x1 push_in connector")
      (fields
        (field (name "BOM_Manufacturer Part") "1825660000")
        (field (name "BOM_Supplier Part") "281-2044-ND")
      )
      (libsource (lib "") (part "4x1 push_in connector"))
    )
    (comp (ref "F4")
      (value "BSMD0603-050-6V")
      (fields (field (name "BOM_Supplier Part") "C883095"))
      (libsource (lib "") (part "BSMD0603-050-6V"))
    )
    (comp (ref "F7")
      (value "BSMD0603-050-6V")
      (fields (field (name "BOM_Supplier Part") "C883095"))
      (libsource (lib "") (part "BSMD0603-050-6V_1"))
    )
    (comp (ref "FINP")
      (value "FC-DA1608HRK-620D")
      (fields (field (name "BOM_Supplier Part") "C84263"))
      (libsource (lib "") (part "FC-DA1608HRK-620D_2"))
    )
    (comp (ref "FSER")
      (value "FC-DA1608HRK-620D")
      (fields (field (name "BOM_Supplier Part") "C84263"))
      (libsource (lib "") (part "FC-DA1608HRK-620D_1"))
    )
    (comp (ref "H1")
      (value "A2541WV-3P_C609572")
      (fields
        (field (name "BOM_Manufacturer Part") "A2541WV-3P")
        (field (name "BOM_Supplier Part") "C609572")
      )
      (libsource (lib "") (part "A2541WV-3P_C609572"))
    )
    (comp (ref "INPUTS") (value "M12A 5pole female") (libsource (lib "") (part "M12A 5pole female_1")))
    (comp (ref "J7")
      (value "A2541WV-2P")
      (fields (field (name "BOM_Supplier Part") "C225477"))
      (libsource (lib "") (part "A2541WV-2P"))
    )
    (comp (ref "LED")
      (value "FC-DA1608HRK-620D")
      (fields (field (name "BOM_Supplier Part") "C84263"))
      (libsource (lib "") (part "FC-DA1608HRK-620D"))
    )
    (comp (ref "M1")
      (value "FC-D1608HYK-588J")
      (fields (field (name "BOM_Supplier Part") "C84268"))
      (libsource (lib "") (part "FC-D1608HYK-588J"))
    )
    (comp (ref "M2")
      (value "FC-D1608HOK-600H")
      (fields (field (name "BOM_Supplier Part") "C84269"))
      (libsource (lib "") (part "FC-D1608HOK-600H"))
    )
    (comp (ref "MOT")
      (value "FC-D1608WD-460H5")
      (fields (field (name "BOM_Supplier Part") "C84265"))
      (libsource (lib "") (part "FC-D1608WD-460H5"))
    )
    (comp (ref "P1")
      (value "HDR-IDC-2.54-2X5P")
      (fields
        (field (name "BOM_Manufacturer Part") "IDC Box 2.54mm 2X5P")
        (field (name "BOM_Supplier Part") "C5665")
      )
      (libsource (lib "") (part "HDR-IDC-2.54-2X5P"))
    )
    (comp (ref "Q1")
      (value "2N7002WT1G")
      (fields (field (name "BOM_Supplier Part") "C12778"))
      (libsource (lib "") (part "2N7002WT1G"))
    )
    (comp (ref "Q2")
      (value "BC856BW,115")
      (fields (field (name "BOM_Supplier Part") "C28063"))
      (libsource (lib "") (part "BC856BW,115_1"))
    )
    (comp (ref "Q3")
      (value "2N7002WT1G")
      (fields (field (name "BOM_Supplier Part") "C12778"))
      (libsource (lib "") (part "2N7002WT1G"))
    )
    (comp (ref "Q4")
      (value "2N7002WT1G")
      (fields (field (name "BOM_Supplier Part") "C12778"))
      (libsource (lib "") (part "2N7002WT1G"))
    )
    (comp (ref "Q5")
      (value "2N7002WT1G")
      (fields (field (name "BOM_Supplier Part") "C12778"))
      (libsource (lib "") (part "2N7002WT1G_1"))
    )
    (comp (ref "Q6")
      (value "ZXMS6004FFTA")
      (fields (field (name "BOM_Supplier Part") "C95063"))
      (libsource (lib "") (part "ZXMS6004FFTA"))
    )
    (comp (ref "Q11")
      (value "BC856BW,115")
      (fields (field (name "BOM_Supplier Part") "C28063"))
      (libsource (lib "") (part "BC856BW,115"))
    )
    (comp (ref "Q12")
      (value "BC856BW,115")
      (fields (field (name "BOM_Supplier Part") "C28063"))
      (libsource (lib "") (part "BC856BW,115_1"))
    )
    (comp (ref "R6")
      (value "1K")
      (fields
        (field (name "BOM_Manufacturer Part") "RTT03102JTP")
        (field (name "BOM_Supplier Part") "C103210")
      )
      (libsource (lib "") (part "RTT03103JTP_2"))
    )
    (comp (ref "R7")
      (value "1K")
      (fields
        (field (name "BOM_Manufacturer Part") "RTT03102JTP")
        (field (name "BOM_Supplier Part") "C103210")
      )
      (libsource (lib "") (part "RTT03103JTP"))
    )
    (comp (ref "R8")
      (value "10K")
      (fields
        (field (name "BOM_Manufacturer Part") "RTT03103JTP")
        (field (name "BOM_Supplier Part") "C103210")
      )
      (libsource (lib "") (part "RTT03103JTP_3"))
    )
    (comp (ref "R9")
      (value "1K")
      (fields
        (field (name "BOM_Manufacturer Part") "RTT03102JTP")
        (field (name "BOM_Supplier Part") "C103210")
      )
      (libsource (lib "") (part "RTT03103JTP_3"))
    )
    (comp (ref "R10")
      (value "1K")
      (fields
        (field (name "BOM_Manufacturer Part") "RTT03102JTP")
        (field (name "BOM_Supplier Part") "C103210")
      )
      (libsource (lib "") (part "RTT03103JTP_2"))
    )
    (comp (ref "R11")
      (value "1K")
      (fields
        (field (name "BOM_Manufacturer Part") "RTT03102JTP")
        (field (name "BOM_Supplier Part") "C103210")
      )
      (libsource (lib "") (part "RTT03103JTP_3"))
    )
    (comp (ref "R12")
      (value "1K")
      (fields
        (field (name "BOM_Manufacturer Part") "RTT03102JTP")
        (field (name "BOM_Supplier Part") "C103210")
      )
      (libsource (lib "") (part "RTT03103JTP_3"))
    )
    (comp (ref "R16")
      (value "10K")
      (fields
        (field (name "BOM_Manufacturer Part") "RTT03103JTP")
        (field (name "BOM_Supplier Part") "C103210")
      )
      (libsource (lib "") (part "RTT03103JTP_1"))
    )
    (comp (ref "R20")
      (value "1K")
      (fields
        (field (name "BOM_Manufacturer Part") "RTT03102JTP")
        (field (name "BOM_Supplier Part") "C103210")
      )
      (libsource (lib "") (part "RTT03103JTP_3"))
    )
    (comp (ref "R21")
      (value "1K")
      (fields
        (field (name "BOM_Manufacturer Part") "RTT03102JTP")
        (field (name "BOM_Supplier Part") "C103210")
      )
      (libsource (lib "") (part "RTT03103JTP_3"))
    )
    (comp (ref "R22")
      (value "1K")
      (fields
        (field (name "BOM_Manufacturer Part") "RTT03102JTP")
        (field (name "BOM_Supplier Part") "C103210")
      )
      (libsource (lib "") (part "RTT03103JTP_2"))
    )
    (comp (ref "R23")
      (value "1K")
      (fields
        (field (name "BOM_Manufacturer Part") "RTT03102JTP")
        (field (name "BOM_Supplier Part") "C103210")
      )
      (libsource (lib "") (part "RTT03103JTP_2"))
    )
    (comp (ref "R24")
      (value "2.7k")
      (fields (field (name "BOM_Manufacturer Part") "RTT03272JTP"))
      (libsource (lib "") (part "RTT03473JTP"))
    )
    (comp (ref "R25")
      (value "2k2")
      (fields
        (field (name "BOM_Manufacturer Part") "RTT03222JTP")
        (field (name "BOM_Supplier Part") "C103203")
      )
      (libsource (lib "") (part "RTT03100JTP"))
    )
    (comp (ref "R26")
      (value "2k2")
      (fields
        (field (name "BOM_Manufacturer Part") "RTT03222JTP")
        (field (name "BOM_Supplier Part") "C103203")
      )
      (libsource (lib "") (part "RTT03100JTP"))
    )
    (comp (ref "R27")
      (value "2k2")
      (fields
        (field (name "BOM_Manufacturer Part") "RTT03222JTP")
        (field (name "BOM_Supplier Part") "C103203")
      )
      (libsource (lib "") (part "RTT03100JTP"))
    )
    (comp (ref "R28")
      (value "8.2K")
      (fields
        (field (name "BOM_Manufacturer Part") "MElF-MFR02041/4WS130ΩFT50")
        (field (name "BOM_Supplier Part") "C265574")
      )
      (libsource (lib "") (part "MELF-MFR02041/4WS8.2KΩFT50"))
    )
    (comp (ref "R33")
      (value "10K")
      (fields
        (field (name "BOM_Manufacturer Part") "RTT03103JTP")
        (field (name "BOM_Supplier Part") "C103210")
      )
      (libsource (lib "") (part "RTT03103JTP"))
    )
    (comp (ref "R36")
      (value "560")
      (fields
        (field (name "BOM_Manufacturer Part") "RTT03561JTP")
        (field (name "BOM_Supplier Part") "C103717")
      )
      (libsource (lib "") (part "RTT03561JTP"))
    )
    (comp (ref "R40")
      (value "2k2")
      (fields
        (field (name "BOM_Manufacturer Part") "RTT03222JTP")
        (field (name "BOM_Supplier Part") "C103203")
      )
      (libsource (lib "") (part "RTT03100JTP"))
    )
    (comp (ref "R41")
      (value "2k2")
      (fields
        (field (name "BOM_Manufacturer Part") "RTT03222JTP")
        (field (name "BOM_Supplier Part") "C103203")
      )
      (libsource (lib "") (part "RTT03100JTP"))
    )
    (comp (ref "R42")
      (value "2k2")
      (fields
        (field (name "BOM_Manufacturer Part") "RTT03222JTP")
        (field (name "BOM_Supplier Part") "C103203")
      )
      (libsource (lib "") (part "RTT03100JTP"))
    )
    (comp (ref "R44")
      (value "560")
      (fields
        (field (name "BOM_Manufacturer Part") "RTT03561JTP")
        (field (name "BOM_Supplier Part") "C103717")
      )
      (libsource (lib "") (part "RTT03561JTP"))
    )
    (comp (ref "R45")
      (value "2k2")
      (fields
        (field (name "BOM_Manufacturer Part") "RTT03222JTP")
        (field (name "BOM_Supplier Part") "C103203")
      )
      (libsource (lib "") (part "RTT03100JTP"))
    )
    (comp (ref "R47")
      (value "560")
      (fields
        (field (name "BOM_Manufacturer Part") "RTT03561JTP")
        (field (name "BOM_Supplier Part") "C103717")
      )
      (libsource (lib "") (part "RTT03561JTP"))
    )
    (comp (ref "R48")
      (value "10K")
      (fields
        (field (name "BOM_Manufacturer Part") "RTT03103JTP")
        (field (name "BOM_Supplier Part") "C103210")
      )
      (libsource (lib "") (part "RTT03103JTP_1"))
    )
    (comp (ref "R49")
      (value "10K")
      (fields
        (field (name "BOM_Manufacturer Part") "RTT03103JTP")
        (field (name "BOM_Supplier Part") "C103210")
      )
      (libsource (lib "") (part "RTT03103JTP_3"))
    )
    (comp (ref "R51")
      (value "10K")
      (fields
        (field (name "BOM_Manufacturer Part") "RTT03103JTP")
        (field (name "BOM_Supplier Part") "C103210")
      )
      (libsource (lib "") (part "RTT03103JTP_2"))
    )
    (comp (ref "R53")
      (value "8.2K")
      (fields
        (field (name "BOM_Manufacturer Part") "MElF-MFR02041/4WS130ΩFT50")
        (field (name "BOM_Supplier Part") "C265574")
      )
      (libsource (lib "") (part "MELF-MFR02041/4WS8.2KΩFT50_1"))
    )
    (comp (ref "R54")
      (value "8.2K")
      (fields
        (field (name "BOM_Manufacturer Part") "MElF-MFR02041/4WS130ΩFT50")
        (field (name "BOM_Supplier Part") "C265574")
      )
      (libsource (lib "") (part "MELF-MFR02041/4WS8.2KΩFT50_1"))
    )
    (comp (ref "R55")
      (value "8.2K")
      (fields
        (field (name "BOM_Manufacturer Part") "MElF-MFR02041/4WS130ΩFT50")
        (field (name "BOM_Supplier Part") "C265574")
      )
      (libsource (lib "") (part "MELF-MFR02041/4WS8.2KΩFT50_1"))
    )
    (comp (ref "R59")
      (value "1K")
      (fields
        (field (name "BOM_Manufacturer Part") "RTT03102JTP")
        (field (name "BOM_Supplier Part") "C103210")
      )
      (libsource (lib "") (part "RTT03103JTP"))
    )
    (comp (ref "R61")
      (value "8.2K")
      (fields
        (field (name "BOM_Manufacturer Part") "MElF-MFR02041/4WS130ΩFT50")
        (field (name "BOM_Supplier Part") "C265574")
      )
      (libsource (lib "") (part "MELF-MFR02041/4WS8.2KΩFT50_1"))
    )
    (comp (ref "R62")
      (value "8.2K")
      (fields
        (field (name "BOM_Manufacturer Part") "MElF-MFR02041/4WS130ΩFT50")
        (field (name "BOM_Supplier Part") "C265574")
      )
      (libsource (lib "") (part "MELF-MFR02041/4WS8.2KΩFT50_1"))
    )
    (comp (ref "R63")
      (value "8.2K")
      (fields
        (field (name "BOM_Manufacturer Part") "MElF-MFR02041/4WS130ΩFT50")
        (field (name "BOM_Supplier Part") "C265574")
      )
      (libsource (lib "") (part "MELF-MFR02041/4WS8.2KΩFT50_1"))
    )
    (comp (ref "R73")
      (value "10K")
      (fields
        (field (name "BOM_Manufacturer Part") "RTT03103JTP")
        (field (name "BOM_Supplier Part") "C103210")
      )
      (libsource (lib "") (part "RTT03103JTP"))
    )
    (comp (ref "R76")
      (value "1K")
      (fields
        (field (name "BOM_Manufacturer Part") "RTT03102JTP")
        (field (name "BOM_Supplier Part") "C103210")
      )
      (libsource (lib "") (part "RTT03103JTP"))
    )
    (comp (ref "R77")
      (value "10K")
      (fields
        (field (name "BOM_Manufacturer Part") "RTT03103JTP")
        (field (name "BOM_Supplier Part") "C103210")
      )
      (libsource (lib "") (part "RTT03103JTP_1"))
    )
    (comp (ref "R94")
      (value "10K")
      (fields
        (field (name "BOM_Manufacturer Part") "RTT03103JTP")
        (field (name "BOM_Supplier Part") "C103210")
      )
      (libsource (lib "") (part "RTT03103JTP_1"))
    )
    (comp (ref "R95")
      (value "1K")
      (fields
        (field (name "BOM_Manufacturer Part") "RTT03102JTP")
        (field (name "BOM_Supplier Part") "C103210")
      )
      (libsource (lib "") (part "RTT03103JTP"))
    )
    (comp (ref "R96")
      (value "1K")
      (fields
        (field (name "BOM_Manufacturer Part") "RTT03102JTP")
        (field (name "BOM_Supplier Part") "C103210")
      )
      (libsource (lib "") (part "RTT03103JTP"))
    )
    (comp (ref "R104")
      (value "1K")
      (fields
        (field (name "BOM_Manufacturer Part") "RTT03102JTP")
        (field (name "BOM_Supplier Part") "C103210")
      )
      (libsource (lib "") (part "RTT03103JTP"))
    )
    (comp (ref "REMOTE")
      (value "FC-D1608HYK-588J")
      (fields (field (name "BOM_Supplier Part") "C84268"))
      (libsource (lib "") (part "FC-D1608HYK-588J_3"))
    )
    (comp (ref "RXD")
      (value "FC-D1608UGK-520D10")
      (fields (field (name "BOM_Supplier Part") "C84267"))
      (libsource (lib "") (part "FC-D1608UGK-520D10"))
    )
    (comp (ref "STEER")
      (value "FC-D1608HYK-588J")
      (fields (field (name "BOM_Supplier Part") "C84268"))
      (libsource (lib "") (part "FC-D1608HYK-588J_1"))
    )
    (comp (ref "STEERING") (value "M12A 5pole female") (libsource (lib "") (part "M12A 5pole female")))
    (comp (ref "TXD")
      (value "FC-DA1608BK-470H10")
      (fields (field (name "BOM_Supplier Part") "C84266"))
      (libsource (lib "") (part "FC-DA1608BK-470H10_1"))
    )
    (comp (ref "U1")
      (value "TG_WEMOS_D1_ESP32(CLONE)")
      (fields
        (field (name "BOM_Manufacturer Part") "New SchematicLib")
        (field (name "BOM_Supplier Part") "undefined")
      )
      (libsource (lib "") (part "TG_WEMOS_D1_ESP32(CLONE)"))
    )
    (comp (ref "U3")
      (value "CH340B")
      (fields (field (name "BOM_Supplier Part") "C81010"))
      (libsource (lib "") (part "CH340B"))
    )
    (comp (ref "U5")
      (value "ATMEGA328P-AU")
      (fields (field (name "BOM_Supplier Part") "C14877"))
      (libsource (lib "") (part "ATMEGA328P-AU"))
    )
    (comp (ref "U9")
      (value "BTN8982TAAUMA1")
      (fields (field (name "BOM_Supplier Part") "C74175"))
      (libsource (lib "") (part "BTN8982TAAUMA1_1"))
    )
    (comp (ref "U10")
      (value "BTN8982TAAUMA1")
      (fields (field (name "BOM_Supplier Part") "C74175"))
      (libsource (lib "") (part "BTN8982TAAUMA1"))
    )
    (comp (ref "U14")
      (value "BTS50301EJAXUMA1")
      (fields (field (name "BOM_Supplier Part") "C454924"))
      (libsource (lib "") (part "BTS50301EJAXUMA1"))
    )
    (comp (ref "WIFI")
      (value "FC-DA1608BK-470H10")
      (fields (field (name "BOM_Supplier Part") "C84266"))
      (libsource (lib "") (part "FC-DA1608BK-470H10"))
    )
    (comp (ref "WORK")
      (value "FC-D1608HYK-588J")
      (fields (field (name "BOM_Supplier Part") "C84268"))
      (libsource (lib "") (part "FC-D1608HYK-588J_2"))
    )
    (comp (ref "X1")
      (value "16MHz")
      (fields
        (field (name "BOM_Manufacturer Part") "X201616MPB4SC")
        (field (name "BOM_Supplier Part") "C108156")
      )
      (libsource (lib "") (part "TZ2315C"))
    )
    (comp (ref "BOOT")
      (value "A2541WV-2P")
      (fields (field (name "BOM_Supplier Part") "C225477"))
      (libsource (lib "") (part "A2541WV-2P"))
    )
    (comp (ref "C37")
      (value "33pF")
      (fields
        (field (name "BOM_Manufacturer Part") "CL10C330JB8NNNC")
        (field (name "BOM_Supplier Part") "C1663")
      )
      (libsource (lib "") (part "CC0603JRNPO9BN330_1"))
    )
    (comp (ref "C39")
      (value "33pF")
      (fields
        (field (name "BOM_Manufacturer Part") "CL10C330JB8NNNC")
        (field (name "BOM_Supplier Part") "C1663")
      )
      (libsource (lib "") (part "CC0603JRNPO9BN330"))
    )
    (comp (ref "C40")
      (value "1uF")
      (fields
        (field (name "BOM_Manufacturer Part") "CL10A105KP8NNNC")
        (field (name "BOM_Supplier Part") "C26413")
      )
      (libsource (lib "") (part "CL10A105KP8NNNC_1"))
    )
    (comp (ref "C41")
      (value "1uF")
      (fields
        (field (name "BOM_Manufacturer Part") "CL10A105KP8NNNC")
        (field (name "BOM_Supplier Part") "C26413")
      )
      (libsource (lib "") (part "CL10A105KP8NNNC"))
    )
    (comp (ref "C42")
      (value "1uF")
      (fields
        (field (name "BOM_Manufacturer Part") "CL10A105KP8NNNC")
        (field (name "BOM_Supplier Part") "C26413")
      )
      (libsource (lib "") (part "CL10A105KP8NNNC"))
    )
    (comp (ref "C43")
      (value "1uF")
      (fields
        (field (name "BOM_Manufacturer Part") "CL10A105KP8NNNC")
        (field (name "BOM_Supplier Part") "C26413")
      )
      (libsource (lib "") (part "CL10A105KP8NNNC"))
    )
    (comp (ref "C45")
      (value "100nF")
      (fields
        (field (name "BOM_Manufacturer Part") "CC0603JRX7R8BB104")
        (field (name "BOM_Supplier Part") "C327087")
      )
      (libsource (lib "") (part "CC0603JRX7R8BB104"))
    )
    (comp (ref "C46")
      (value "1uF")
      (fields
        (field (name "BOM_Manufacturer Part") "CL10A105KP8NNNC")
        (field (name "BOM_Supplier Part") "C26413")
      )
      (libsource (lib "") (part "CL10A105KP8NNNC"))
    )
    (comp (ref "C47")
      (value "1uF")
      (fields
        (field (name "BOM_Manufacturer Part") "CL10A105KP8NNNC")
        (field (name "BOM_Supplier Part") "C26413")
      )
      (libsource (lib "") (part "CL10A105KP8NNNC"))
    )
    (comp (ref "C49")
      (value "1uF")
      (fields
        (field (name "BOM_Manufacturer Part") "CL10A105KP8NNNC")
        (field (name "BOM_Supplier Part") "C26413")
      )
      (libsource (lib "") (part "CL10A105KP8NNNC"))
    )
    (comp (ref "C50")
      (value "1uF")
      (fields
        (field (name "BOM_Manufacturer Part") "CL10A105KP8NNNC")
        (field (name "BOM_Supplier Part") "C26413")
      )
      (libsource (lib "") (part "CL10A105KP8NNNC"))
    )
    (comp (ref "C51")
      (value "1uF")
      (fields
        (field (name "BOM_Manufacturer Part") "CL10A105KP8NNNC")
        (field (name "BOM_Supplier Part") "C26413")
      )
      (libsource (lib "") (part "CL10A105KP8NNNC"))
    )
    (comp (ref "C54")
      (value "1uF")
      (fields
        (field (name "BOM_Manufacturer Part") "CL10A105KP8NNNC")
        (field (name "BOM_Supplier Part") "C26413")
      )
      (libsource (lib "") (part "CL10A105KP8NNNC"))
    )
    (comp (ref "CN6")
      (value "1315-1206G0M075CP01")
      (fields (field (name "BOM_Supplier Part") "C721777"))
      (libsource (lib "") (part "1315-1206G0M075CP01"))
    )
    (comp (ref "D7")
      (value "CDSOT23-T24CAN")
      (fields (field (name "BOM_Supplier Part") "C252430"))
      (libsource (lib "") (part "CDSOT23-T24CAN"))
    )
    (comp (ref "LED1")
      (value "FC-D1608UGK-520D10")
      (fields (field (name "BOM_Supplier Part") "C84267"))
      (libsource (lib "") (part "FC-D1608UGK-520D10"))
    )
    (comp (ref "LED2")
      (value "FC-DA1608BK-470H10")
      (fields (field (name "BOM_Supplier Part") "C84266"))
      (libsource (lib "") (part "FC-DA1608BK-470H10_2"))
    )
    (comp (ref "LED3")
      (value "FC-D1608UGK-520D10")
      (fields (field (name "BOM_Supplier Part") "C84267"))
      (libsource (lib "") (part "FC-D1608UGK-520D10"))
    )
    (comp (ref "LED4")
      (value "FC-DA1608BK-470H10")
      (fields (field (name "BOM_Supplier Part") "C84266"))
      (libsource (lib "") (part "FC-DA1608BK-470H10"))
    )
    (comp (ref "R78")
      (value "10K")
      (fields
        (field (name "BOM_Manufacturer Part") "RTT03103JTP")
        (field (name "BOM_Supplier Part") "C103210")
      )
      (libsource (lib "") (part "RTT03103JTP_1"))
    )
    (comp (ref "R79")
      (value "10K")
      (fields
        (field (name "BOM_Manufacturer Part") "RTT03103JTP")
        (field (name "BOM_Supplier Part") "C103210")
      )
      (libsource (lib "") (part "RTT03103JTP_1"))
    )
    (comp (ref "R80")
      (value "10K")
      (fields
        (field (name "BOM_Manufacturer Part") "RTT03103JTP")
        (field (name "BOM_Supplier Part") "C103210")
      )
      (libsource (lib "") (part "RTT03103JTP"))
    )
    (comp (ref "R81")
      (value "2.7k")
      (fields (field (name "BOM_Manufacturer Part") "RTT03272JTP"))
      (libsource (lib "") (part "RTT03473JTP"))
    )
    (comp (ref "R82")
      (value "10K")
      (fields
        (field (name "BOM_Manufacturer Part") "RTT03103JTP")
        (field (name "BOM_Supplier Part") "C103210")
      )
      (libsource (lib "") (part "RTT03103JTP"))
    )
    (comp (ref "R83")
      (value "10")
      (fields
        (field (name "BOM_Manufacturer Part") "RTT03100JTP")
        (field (name "BOM_Supplier Part") "C103203")
      )
      (libsource (lib "") (part "RTT03100JTP"))
    )
    (comp (ref "R84")
      (value "1K")
      (fields
        (field (name "BOM_Manufacturer Part") "RTT03102JTP")
        (field (name "BOM_Supplier Part") "C103209")
      )
      (libsource (lib "") (part "RTT03102JTP"))
    )
    (comp (ref "R85")
      (value "1K")
      (fields
        (field (name "BOM_Manufacturer Part") "RTT03102JTP")
        (field (name "BOM_Supplier Part") "C103209")
      )
      (libsource (lib "") (part "RTT03102JTP"))
    )
    (comp (ref "R86")
      (value "1K")
      (fields
        (field (name "BOM_Manufacturer Part") "RTT03102JTP")
        (field (name "BOM_Supplier Part") "C103209")
      )
      (libsource (lib "") (part "RTT03102JTP"))
    )
    (comp (ref "R87")
      (value "1K")
      (fields
        (field (name "BOM_Manufacturer Part") "RTT03102JTP")
        (field (name "BOM_Supplier Part") "C103209")
      )
      (libsource (lib "") (part "RTT03102JTP"))
    )
    (comp (ref "R88")
      (value "1K")
      (fields
        (field (name "BOM_Manufacturer Part") "RTT03102JTP")
        (field (name "BOM_Supplier Part") "C103209")
      )
      (libsource (lib "") (part "RTT03102JTP_1"))
    )
    (comp (ref "R89")
      (value "1K")
      (fields
        (field (name "BOM_Manufacturer Part") "RTT03102JTP")
        (field (name "BOM_Supplier Part") "C103209")
      )
      (libsource (lib "") (part "RTT03102JTP_1"))
    )
    (comp (ref "RXCAN1")
      (value "FC-D1608UGK-520D10")
      (fields (field (name "BOM_Supplier Part") "C84267"))
      (libsource (lib "") (part "FC-D1608UGK-520D10_1"))
    )
    (comp (ref "TXCAN1")
      (value "FC-DA1608BK-470H10")
      (fields (field (name "BOM_Supplier Part") "C84266"))
      (libsource (lib "") (part "FC-DA1608BK-470H10_1"))
    )
    (comp (ref "U11")
      (value "LPC54616J512BD100")
      (fields (field (name "BOM_Supplier Part") "568-13457-ND"))
      (libsource (lib "") (part "LPC54616J512BD100"))
    )
    (comp (ref "U12")
      (value "TJA1051T/3/1J")
      (fields (field (name "BOM_Supplier Part") "C38695"))
      (libsource (lib "") (part "TJA1051T/3/1J"))
    )
    (comp (ref "X3")
      (value "12MHz")
      (fields
        (field (name "BOM_Manufacturer Part") "X322512MSB4SI")
        (field (name "BOM_Supplier Part") "C9002")
      )
      (libsource (lib "") (part "X322512MSB4SI"))
    )
    (comp (ref "ANT1")
      (value "FC-D1608UGK-520D10")
      (fields (field (name "BOM_Supplier Part") "C84267"))
      (libsource (lib "") (part "FC-D1608UGK-520D10_1"))
    )
    (comp (ref "ANT2")
      (value "FC-D1608UGK-520D10")
      (fields (field (name "BOM_Supplier Part") "C84267"))
      (libsource (lib "") (part "FC-D1608UGK-520D10_1"))
    )
    (comp (ref "ARDU1")
      (value "BM06B-GHS-TBT(LF)(SN)")
      (fields
        (field (name "BOM_Manufacturer Part") "SM06B-GHS-TB(LF)(SN)")
        (field (name "BOM_Supplier Part") "C133065")
      )
      (libsource (lib "") (part "SM06B-GHS-TB(LF)(SN)"))
    )
    (comp (ref "C8")
      (value "100nF")
      (fields
        (field (name "BOM_Manufacturer Part") "CC0603JRX7R8BB104")
        (field (name "BOM_Supplier Part") "C327087")
      )
      (libsource (lib "") (part "CC0603JRX7R8BB104"))
    )
    (comp (ref "C9")
      (value "100nF")
      (fields
        (field (name "BOM_Manufacturer Part") "CC0603JRX7R8BB104")
        (field (name "BOM_Supplier Part") "C327087")
      )
      (libsource (lib "") (part "CC0603JRX7R8BB104"))
    )
    (comp (ref "C14")
      (value "1uF")
      (fields
        (field (name "BOM_Manufacturer Part") "CL10A105KP8NNNC")
        (field (name "BOM_Supplier Part") "C26413")
      )
      (libsource (lib "") (part "CL10A105KP8NNNC"))
    )
    (comp (ref "C15")
      (value "1uF")
      (fields
        (field (name "BOM_Manufacturer Part") "CL10A105KP8NNNC")
        (field (name "BOM_Supplier Part") "C26413")
      )
      (libsource (lib "") (part "CL10A105KP8NNNC"))
    )
    (comp (ref "C24")
      (value "1nF")
      (fields
        (field (name "BOM_Manufacturer Part") "0603CG102F500NT")
        (field (name "BOM_Supplier Part") "C507408")
      )
      (libsource (lib "") (part "0603CG102F500NT"))
    )
    (comp (ref "C25")
      (value "1nF")
      (fields
        (field (name "BOM_Manufacturer Part") "0603CG102F500NT")
        (field (name "BOM_Supplier Part") "C507408")
      )
      (libsource (lib "") (part "0603CG102F500NT"))
    )
    (comp (ref "C33")
      (value "100nF")
      (fields
        (field (name "BOM_Manufacturer Part") "CC0603JRX7R8BB104")
        (field (name "BOM_Supplier Part") "C327087")
      )
      (libsource (lib "") (part "CC0603JRX7R8BB104"))
    )
    (comp (ref "C58")
      (value "100nF")
      (fields
        (field (name "BOM_Manufacturer Part") "CC0603JRX7R8BB104")
        (field (name "BOM_Supplier Part") "C327087")
      )
      (libsource (lib "") (part "CC0603JRX7R8BB104_2"))
    )
    (comp (ref "C59")
      (value "100nF")
      (fields
        (field (name "BOM_Manufacturer Part") "CC0603JRX7R8BB104")
        (field (name "BOM_Supplier Part") "C327087")
      )
      (libsource (lib "") (part "CC0603JRX7R8BB104_1"))
    )
    (comp (ref "C60")
      (value "22uF")
      (fields
        (field (name "BOM_Manufacturer Part") "CL21A226MAQNNNE")
        (field (name "BOM_Supplier Part") "C45783")
      )
      (libsource (lib "") (part "CL21A226MAQNNNE"))
    )
    (comp (ref "CHA")
      (value "FC-D1608HYK-588J")
      (fields (field (name "BOM_Supplier Part") "C84268"))
      (libsource (lib "") (part "FC-D1608HYK-588J"))
    )
    (comp (ref "CHB")
      (value "FC-D1608HOK-600H")
      (fields (field (name "BOM_Supplier Part") "C84269"))
      (libsource (lib "") (part "FC-D1608HOK-600H_1"))
    )
    (comp (ref "CN1")
      (value "4x1 push_in connector")
      (fields
        (field (name "BOM_Manufacturer Part") "1825660000")
        (field (name "BOM_Supplier Part") "281-2044-ND")
      )
      (libsource (lib "") (part "4x1 push_in connector"))
    )
    (comp (ref "CN5")
      (value "4x1 push_in connector")
      (fields
        (field (name "BOM_Manufacturer Part") "1825660000")
        (field (name "BOM_Supplier Part") "281-2044-ND")
      )
      (libsource (lib "") (part "4x1 push_in connector"))
    )
    (comp (ref "DIFF")
      (value "FC-D1608UGK-520D10")
      (fields (field (name "BOM_Supplier Part") "C84267"))
      (libsource (lib "") (part "FC-D1608UGK-520D10"))
    )
    (comp (ref "F5")
      (value "BSMD0603-050-6V")
      (fields (field (name "BOM_Supplier Part") "C883095"))
      (libsource (lib "") (part "BSMD0603-050-6V"))
    )
    (comp (ref "F6")
      (value "BSMD0603-050-6V")
      (fields (field (name "BOM_Supplier Part") "C883095"))
      (libsource (lib "") (part "BSMD0603-050-6V"))
    )
    (comp (ref "FROT")
      (value "FC-DA1608HRK-620D")
      (fields (field (name "BOM_Supplier Part") "C84263"))
      (libsource (lib "") (part "FC-DA1608HRK-620D_1"))
    )
    (comp (ref "FWAS")
      (value "FC-DA1608HRK-620D")
      (fields (field (name "BOM_Supplier Part") "C84263"))
      (libsource (lib "") (part "FC-DA1608HRK-620D"))
    )
    (comp (ref "J4")
      (value "A2541WV-2P")
      (fields (field (name "BOM_Supplier Part") "C225477"))
      (libsource (lib "") (part "A2541WV-2P"))
    )
    (comp (ref "OP1") (value "Option M8 4pole") (libsource (lib "") (part "JUMPER")))
    (comp (ref "P2") (value "Ardusimple RTK2B Board") (libsource (lib "") (part "Ardusimple RTK2B Board")))
    (comp (ref "Q9")
      (value "BC856BW,115")
      (fields (field (name "BOM_Supplier Part") "C28063"))
      (libsource (lib "") (part "BC856BW,115"))
    )
    (comp (ref "Q10")
      (value "BC856BW,115")
      (fields (field (name "BOM_Supplier Part") "C28063"))
      (libsource (lib "") (part "BC856BW,115"))
    )
    (comp (ref "QWIIC")
      (value "QWIIC SMD JST")
      (fields
        (field (name "BOM_Manufacturer Part") "SM04B-SRSS-TB(LF)(SN)")
        (field (name "BOM_Supplier Part") "C160404")
      )
      (libsource (lib "") (part "QWIIC SMD JST"))
    )
    (comp (ref "R5")
      (value "2k2")
      (fields
        (field (name "BOM_Manufacturer Part") "RTT03222JTP")
        (field (name "BOM_Supplier Part") "C103203")
      )
      (libsource (lib "") (part "RTT03100JTP"))
    )
    (comp (ref "R13")
      (value "2k2")
      (fields
        (field (name "BOM_Manufacturer Part") "RTT03222JTP")
        (field (name "BOM_Supplier Part") "C103203")
      )
      (libsource (lib "") (part "RTT03100JTP"))
    )
    (comp (ref "R29")
      (value "1K")
      (fields
        (field (name "BOM_Manufacturer Part") "RTT03102JTP")
        (field (name "BOM_Supplier Part") "C103209")
      )
      (libsource (lib "") (part "RTT03102JTP"))
    )
    (comp (ref "R30")
      (value "1K")
      (fields
        (field (name "BOM_Manufacturer Part") "RTT03102JTP")
        (field (name "BOM_Supplier Part") "C103209")
      )
      (libsource (lib "") (part "RTT03102JTP"))
    )
    (comp (ref "R31")
      (value "1K")
      (fields
        (field (name "BOM_Manufacturer Part") "RTT03102JTP")
        (field (name "BOM_Supplier Part") "C103210")
      )
      (libsource (lib "") (part "RTT03103JTP"))
    )
    (comp (ref "R32")
      (value "1K")
      (fields
        (field (name "BOM_Manufacturer Part") "RTT03102JTP")
        (field (name "BOM_Supplier Part") "C103210")
      )
      (libsource (lib "") (part "RTT03103JTP"))
    )
    (comp (ref "R52")
      (value "1K")
      (fields
        (field (name "BOM_Manufacturer Part") "RTT03102JTP")
        (field (name "BOM_Supplier Part") "C103210")
      )
      (libsource (lib "") (part "RTT03103JTP"))
    )
    (comp (ref "R56")
      (value "1K")
      (fields
        (field (name "BOM_Manufacturer Part") "RTT03102JTP")
        (field (name "BOM_Supplier Part") "C103210")
      )
      (libsource (lib "") (part "RTT03103JTP"))
    )
    (comp (ref "R57")
      (value "1K")
      (fields
        (field (name "BOM_Manufacturer Part") "RTT03102JTP")
        (field (name "BOM_Supplier Part") "C103210")
      )
      (libsource (lib "") (part "RTT03103JTP"))
    )
    (comp (ref "R58")
      (value "1K")
      (fields
        (field (name "BOM_Manufacturer Part") "RTT03102JTP")
        (field (name "BOM_Supplier Part") "C103210")
      )
      (libsource (lib "") (part "RTT03103JTP"))
    )
    (comp (ref "R74")
      (value "10K")
      (fields
        (field (name "BOM_Manufacturer Part") "RTT03103JTP")
        (field (name "BOM_Supplier Part") "C103210")
      )
      (libsource (lib "") (part "RTT03103JTP_1"))
    )
    (comp (ref "R75")
      (value "1K")
      (fields
        (field (name "BOM_Manufacturer Part") "RTT03102JTP")
        (field (name "BOM_Supplier Part") "C103210")
      )
      (libsource (lib "") (part "RTT03103JTP_1"))
    )
    (comp (ref "R90")
      (value "1K")
      (fields
        (field (name "BOM_Manufacturer Part") "RTT03102JTP")
        (field (name "BOM_Supplier Part") "C103210")
      )
      (libsource (lib "") (part "RTT03103JTP_1"))
    )
    (comp (ref "R91")
      (value "1K")
      (fields
        (field (name "BOM_Manufacturer Part") "RTT03102JTP")
        (field (name "BOM_Supplier Part") "C103210")
      )
      (libsource (lib "") (part "RTT03103JTP_1"))
    )
    (comp (ref "R92")
      (value "120")
      (fields
        (field (name "BOM_Manufacturer Part") "RTT06121JTP")
        (field (name "BOM_Supplier Part") "C104621")
      )
      (libsource (lib "") (part "RTT06121JTP"))
    )
    (comp (ref "R98")
      (value "1K")
      (fields
        (field (name "BOM_Manufacturer Part") "RTT03102JTP")
        (field (name "BOM_Supplier Part") "C103210")
      )
      (libsource (lib "") (part "RTT03103JTP"))
    )
    (comp (ref "ROTARY/485") (value "M8 4pole female") (libsource (lib "") (part "M8 4pole female")))
    (comp (ref "U15") (value "CMPS14") (libsource (lib "") (part "CMPS14")))
    (comp (ref "U16") (value "Female2X14_2mm") (libsource (lib "") (part "Female2X14_2mm")))
    (comp (ref "U17")
      (value "ADS1115IDGSR")
      (fields (field (name "BOM_Supplier Part") "C37593"))
      (libsource (lib "") (part "ADS1115IDGSR"))
    )
    (comp (ref "U18")
      (value "MMA8452QR1_C11360")
      (fields (field (name "BOM_Manufacturer Part") "MMA8452QR1") (field (name "BOM_Supplier Part") "C11360"))
      (libsource (lib "") (part "MMA8452QR1_C11360"))
    )
    (comp (ref "U19")
      (value "CH340B")
      (fields (field (name "BOM_Supplier Part") "C81010"))
      (libsource (lib "") (part "CH340B"))
    )
    (comp (ref "WAS1") (value "M8 3pole female") (libsource (lib "") (part "M8 3pole female")))
    (comp (ref "WAS2")
      (value "FC-D1608HYK-588J")
      (fields (field (name "BOM_Supplier Part") "C84268"))
      (libsource (lib "") (part "FC-D1608HYK-588J_1"))
    )
    (comp (ref "WAS3")
      (value "FC-D1608HOK-600H")
      (fields (field (name "BOM_Supplier Part") "C84269"))
      (libsource (lib "") (part "FC-D1608HOK-600H"))
    )
  )
  (nets
    (net (code "1") (name "+3V3") (class "Default")
      (node (ref "3V3") (pin "2") (pinfunction "+_2") (pintype "input"))
      (node (ref "C15") (pin "1") (pinfunction "1_1") (pintype "input"))
      (node (ref "C36") (pin "1") (pinfunction "1_1") (pintype "input"))
      (node (ref "C41") (pin "2") (pinfunction "2_2") (pintype "input"))
      (node (ref "C42") (pin "2") (pinfunction "2_2") (pintype "input"))
      (node (ref "C43") (pin "2") (pinfunction "2_2") (pintype "input"))
      (node (ref "C45") (pin "2") (pinfunction "2_2") (pintype "unspecified"))
      (node (ref "C46") (pin "2") (pinfunction "2_2") (pintype "input"))
      (node (ref "C47") (pin "2") (pinfunction "2_2") (pintype "input"))
      (node (ref "C48") (pin "2") (pinfunction "2_2") (pintype "unspecified"))
      (node (ref "C49") (pin "2") (pinfunction "2_2") (pintype "input"))
      (node (ref "C50") (pin "2") (pinfunction "2_2") (pintype "input"))
      (node (ref "C51") (pin "2") (pinfunction "2_2") (pintype "input"))
      (node (ref "C54") (pin "2") (pinfunction "2_2") (pintype "input"))
      (node (ref "C60") (pin "2") (pinfunction "2_2") (pintype "unspecified"))
      (node (ref "CN15") (pin "1") (pinfunction "1_1") (pintype "unspecified"))
      (node (ref "CN6") (pin "1") (pinfunction "1_1") (pintype "unspecified"))
      (node (ref "L2") (pin "2") (pinfunction "2_2") (pintype "input"))
      (node (ref "P1") (pin "9") (pinfunction "9_9") (pintype "unspecified"))
      (node (ref "QWIIC") (pin "2") (pinfunction "3.3V_2") (pintype "unspecified"))
      (node (ref "R29") (pin "2") (pinfunction "2_2") (pintype "input"))
      (node (ref "R30") (pin "2") (pinfunction "2_2") (pintype "input"))
      (node (ref "R37") (pin "2") (pinfunction "2_2") (pintype "input"))
      (node (ref "R78") (pin "1") (pinfunction "1_1") (pintype "input"))
      (node (ref "R79") (pin "1") (pinfunction "1_1") (pintype "input"))
      (node (ref "R94") (pin "1") (pinfunction "1_1") (pintype "input"))
      (node (ref "RX485") (pin "2") (pinfunction "A_2") (pintype "input"))
      (node (ref "RXCAN") (pin "2") (pinfunction "A_2") (pintype "input"))
      (node (ref "RXCAN1") (pin "2") (pinfunction "A_2") (pintype "input"))
      (node (ref "TX485") (pin "2") (pinfunction "+_2") (pintype "input"))
      (node (ref "TXCAN") (pin "2") (pinfunction "+_2") (pintype "input"))
      (node (ref "TXCAN1") (pin "2") (pinfunction "+_2") (pintype "input"))
      (node (ref "U1") (pin "30") (pinfunction "3.3V_30") (pintype "unspecified"))
      (node (ref "U11") (pin "1") (pinfunction "VDD_1") (pintype "passive"))
      (node (ref "U11") (pin "10") (pinfunction "USB1_AVDDC3V3_10") (pintype "passive"))
      (node (ref "U11") (pin "11") (pinfunction "USB1_AVDDTX3V3_11") (pintype "passive"))
      (node (ref "U11") (pin "21") (pinfunction "VDD_21") (pintype "passive"))
      (node (ref "U11") (pin "31") (pinfunction "VREFP_31") (pintype "unspecified"))
      (node (ref "U11") (pin "32") (pinfunction "VDDA_32") (pintype "passive"))
      (node (ref "U11") (pin "33") (pinfunction "VDD_33") (pintype "passive"))
      (node (ref "U11") (pin "45") (pinfunction "VBAT_45") (pintype "bidirectional"))
      (node (ref "U11") (pin "50") (pinfunction "VDD_50") (pintype "passive"))
      (node (ref "U11") (pin "54") (pinfunction "VDD_54") (pintype "passive"))
      (node (ref "U11") (pin "75") (pinfunction "VDD_75") (pintype "passive"))
      (node (ref "U11") (pin "76") (pinfunction "VDD_76") (pintype "passive"))
      (node (ref "U11") (pin "99") (pinfunction "VDD_99") (pintype "passive"))
      (node (ref "U12") (pin "5") (pinfunction "VIO_5") (pintype "unspecified"))
      (node (ref "U16") (pin "6") (pinfunction "VCC_3V3_6") (pintype "unspecified"))
      (node (ref "U18") (pin "1") (pinfunction "VDDIO_1") (pintype "unspecified"))
      (node (ref "U18") (pin "14") (pinfunction "VDD_14") (pintype "unspecified"))
      (node (ref "U7") (pin "5") (pinfunction "VIO_5") (pintype "unspecified"))
      (node (ref "U8") (pin "8") (pinfunction "VCC_8") (pintype "unspecified"))
    )
    (net (code "2") (name "+5V") (class "Default")
      (node (ref "5V") (pin "2") (pinfunction "+_2") (pintype "input"))
      (node (ref "ARDU1") (pin "1") (pinfunction "1_1") (pintype "unspecified"))
      (node (ref "C14") (pin "1") (pinfunction "1_1") (pintype "input"))
      (node (ref "C2") (pin "1") (pinfunction "1_1") (pintype "input"))
      (node (ref "C21") (pin "2") (pinfunction "2_2") (pintype "unspecified"))
      (node (ref "C22") (pin "1") (pinfunction "1_1") (pintype "input"))
      (node (ref "C26") (pin "1") (pinfunction "1_1") (pintype "input"))
      (node (ref "C34") (pin "1") (pinfunction "1_1") (pintype "input"))
      (node (ref "C35") (pin "1") (pinfunction "1_1") (pintype "input"))
      (node (ref "C4") (pin "1") (pinfunction "1_1") (pintype "unspecified"))
      (node (ref "C40") (pin "1") (pinfunction "1_1") (pintype "input"))
      (node (ref "C53") (pin "2") (pinfunction "2_2") (pintype "unspecified"))
      (node (ref "C56") (pin "1") (pinfunction "1_1") (pintype "input"))
      (node (ref "C59") (pin "1") (pinfunction "1_1") (pintype "unspecified"))
      (node (ref "CHA") (pin "2") (pinfunction "A_2") (pintype "input"))
      (node (ref "CHB") (pin "2") (pinfunction "A_2") (pintype "input"))
      (node (ref "CN7") (pin "1") (pinfunction "1_1") (pintype "unspecified"))
      (node (ref "F1") (pin "2") (pinfunction "2_2") (pintype "unspecified"))
      (node (ref "F5") (pin "1") (pinfunction "1_1") (pintype "unspecified"))
      (node (ref "F6") (pin "1") (pinfunction "1_1") (pintype "unspecified"))
      (node (ref "F7") (pin "1") (pinfunction "1_1") (pintype "unspecified"))
      (node (ref "FGNSS") (pin "1") (pinfunction "A_1") (pintype "input"))
      (node (ref "FROT") (pin "1") (pinfunction "A_1") (pintype "input"))
      (node (ref "FSER") (pin "1") (pinfunction "A_1") (pintype "input"))
      (node (ref "FWAS") (pin "1") (pinfunction "A_1") (pintype "input"))
      (node (ref "H1") (pin "1") (pinfunction "1_1") (pintype "unspecified"))
      (node (ref "J1") (pin "2") (pinfunction "2_2") (pintype "unspecified"))
      (node (ref "J2") (pin "2") (pinfunction "2_2") (pintype "unspecified"))
      (node (ref "J3") (pin "2") (pinfunction "2_2") (pintype "unspecified"))
      (node (ref "L8") (pin "2") (pinfunction "2_2") (pintype "input"))
      (node (ref "R104") (pin "1") (pinfunction "1_1") (pintype "input"))
      (node (ref "R22") (pin "2") (pinfunction "2_2") (pintype "input"))
      (node (ref "R23") (pin "2") (pinfunction "2_2") (pintype "input"))
      (node (ref "R48") (pin "1") (pinfunction "1_1") (pintype "input"))
      (node (ref "R6") (pin "2") (pinfunction "2_2") (pintype "input"))
      (node (ref "U1") (pin "31") (pinfunction "VCC_31") (pintype "unspecified"))
      (node (ref "U11") (pin "9") (pinfunction "USB1_VBUS_9") (pintype "unspecified"))
      (node (ref "U12") (pin "3") (pinfunction "VCC_3") (pintype "unspecified"))
      (node (ref "U13") (pin "3") (pinfunction "Vin_3") (pintype "unspecified"))
      (node (ref "U13") (pin "5") (pinfunction "EN_5") (pintype "unspecified"))
      (node (ref "U15") (pin "1") (pinfunction "3.3v-5v_1") (pintype "passive"))
      (node (ref "U17") (pin "8") (pinfunction "VDD_8") (pintype "unspecified"))
      (node (ref "U19") (pin "16") (pinfunction "VCC_16") (pintype "unspecified"))
      (node (ref "U2") (pin "20") (pinfunction "VDD5_20") (pintype "unspecified"))
      (node (ref "U3") (pin "16") (pinfunction "VCC_16") (pintype "unspecified"))
      (node (ref "U5") (pin "18") (pinfunction "AVCC_18") (pintype "unspecified"))
      (node (ref "U5") (pin "4") (pinfunction "VCC_4") (pintype "unspecified"))
      (node (ref "U5") (pin "6") (pinfunction "VCC_6") (pintype "unspecified"))
      (node (ref "U6") (pin "16") (pinfunction "VCC_16") (pintype "unspecified"))
      (node (ref "U7") (pin "3") (pinfunction "VCC_3") (pintype "unspecified"))
      (node (ref "USB1") (pin "1") (pinfunction "VCC_1") (pintype "input"))
      (node (ref "USB_AUX") (pin "1") (pinfunction "VCC_1") (pintype "unspecified"))
      (node (ref "USB_AUX") (pin "5") (pinfunction "VCC_5") (pintype "unspecified"))
      (node (ref "WAS2") (pin "2") (pinfunction "A_2") (pintype "input"))
      (node (ref "WAS3") (pin "2") (pinfunction "A_2") (pintype "input"))
      (node (ref "WIFI") (pin "2") (pinfunction "+_2") (pintype "input"))
    )
    (net (code "3") (name "+Batt") (class "Default")
      (node (ref "CN4") (pin "2") (pinfunction "2_2") (pintype "unspecified"))
      (node (ref "D2") (pin "2") (pinfunction "A_2") (pintype "unspecified"))
      (node (ref "D3") (pin "1") (pinfunction "A_1") (pintype "unspecified"))
      (node (ref "F4") (pin "1") (pinfunction "1_1") (pintype "unspecified"))
      (node (ref "FINP") (pin "1") (pinfunction "A_1") (pintype "input"))
      (node (ref "POWER") (pin "1") (pinfunction "+_1") (pintype "unspecified"))
    )
    (net (code "4") (name "+Motor") (class "Default")
      (node (ref "C30") (pin "2") (pinfunction "2_2") (pintype "unspecified"))
      (node (ref "C31") (pin "1") (pinfunction "1_1") (pintype "unspecified"))
      (node (ref "CN4") (pin "1") (pinfunction "1_1") (pintype "unspecified"))
      (node (ref "D1") (pin "2") (pinfunction "A_2") (pintype "unspecified"))
      (node (ref "MOT") (pin "2") (pinfunction "+_2") (pintype "input"))
      (node (ref "POWER") (pin "4") (pinfunction "4_4") (pintype "unspecified"))
      (node (ref "Q2") (pin "2") (pinfunction "2_2") (pintype "input"))
      (node (ref "R35") (pin "1") (pinfunction "1_1") (pintype "input"))
      (node (ref "R51") (pin "2") (pinfunction "2_2") (pintype "input"))
      (node (ref "R53") (pin "2") (pinfunction "2_2") (pintype "unspecified"))
      (node (ref "U10") (pin "7") (pinfunction "VS_7") (pintype "unspecified"))
      (node (ref "U14") (pin "9") (pinfunction "EP_9") (pintype "unspecified"))
      (node (ref "U9") (pin "7") (pinfunction "VS_7") (pintype "unspecified"))
    )
    (net (code "5") (name "+SMPS") (class "Default")
      (node (ref "C20") (pin "2") (pinfunction "2_2") (pintype "unspecified"))
      (node (ref "C61") (pin "2") (pinfunction "2_2") (pintype "input"))
      (node (ref "L7") (pin "2") (pinfunction "2_2") (pintype "unspecified"))
      (node (ref "L8") (pin "1") (pinfunction "1_1") (pintype "input"))
      (node (ref "R17") (pin "2") (pinfunction "2_2") (pintype "input"))
    )
    (net (code "6") (name "+Vin") (class "Default")
      (node (ref "C17") (pin "2") (pinfunction "2_2") (pintype "unspecified"))
      (node (ref "C18") (pin "2") (pinfunction "2_2") (pintype "unspecified"))
      (node (ref "C19") (pin "2") (pinfunction "2_2") (pintype "unspecified"))
      (node (ref "C32") (pin "1") (pinfunction "1_1") (pintype "unspecified"))
      (node (ref "D3") (pin "2") (pinfunction "K_2") (pintype "unspecified"))
      (node (ref "J8") (pin "4") (pinfunction "4_4") (pintype "unspecified"))
      (node (ref "U4") (pin "3") (pinfunction "Vin_3") (pintype "unspecified"))
    )
    (net (code "7") (name "-Min") (class "Default")
      (node (ref "CN4") (pin "4") (pinfunction "4_4") (pintype "unspecified"))
      (node (ref "D1") (pin "1") (pinfunction "K_1") (pintype "unspecified"))
      (node (ref "POWER") (pin "2") (pinfunction "2_2") (pintype "unspecified"))
      (node (ref "Q8") (pin "5") (pinfunction "D_5") (pintype "unspecified"))
      (node (ref "Q8") (pin "6") (pinfunction "D_6") (pintype "unspecified"))
      (node (ref "Q8") (pin "7") (pinfunction "D_7") (pintype "unspecified"))
      (node (ref "Q8") (pin "8") (pinfunction "D_8") (pintype "unspecified"))
    )
    (net (code "8") (name "-Motor") (class "Default")
      (node (ref "C30") (pin "1") (pinfunction "1_1") (pintype "unspecified"))
      (node (ref "C31") (pin "2") (pinfunction "2_2") (pintype "unspecified"))
      (node (ref "Q8") (pin "1") (pinfunction "S_1") (pintype "unspecified"))
      (node (ref "Q8") (pin "2") (pinfunction "S_2") (pintype "unspecified"))
      (node (ref "Q8") (pin "3") (pinfunction "S_3") (pintype "unspecified"))
      (node (ref "R11") (pin "1") (pinfunction "1_1") (pintype "input"))
      (node (ref "R12") (pin "1") (pinfunction "1_1") (pintype "input"))
      (node (ref "R20") (pin "2") (pinfunction "2_2") (pintype "input"))
      (node (ref "R21") (pin "2") (pinfunction "2_2") (pintype "input"))
      (node (ref "R39") (pin "1") (pinfunction "1_1") (pintype "input"))
      (node (ref "R49") (pin "1") (pinfunction "1_1") (pintype "input"))
      (node (ref "R54") (pin "2") (pinfunction "2_2") (pintype "unspecified"))
      (node (ref "U10") (pin "1") (pinfunction "GND_1") (pintype "unspecified"))
      (node (ref "U14") (pin "1") (pinfunction "GND_1") (pintype "unspecified"))
      (node (ref "U9") (pin "1") (pinfunction "GND_1") (pintype "unspecified"))
    )
    (net (code "9") (name ".6V") (class "Default")
      (node (ref "C61") (pin "1") (pinfunction "1_1") (pintype "input"))
      (node (ref "R17") (pin "1") (pinfunction "1_1") (pintype "input"))
      (node (ref "R18") (pin "2") (pinfunction "2_2") (pintype "input"))
      (node (ref "U4") (pin "4") (pinfunction "FB_4") (pintype "unspecified"))
    )
    (net (code "10") (name "1V8Hub") (class "Default")
      (node (ref "C12") (pin "2") (pinfunction "2_2") (pintype "input"))
      (node (ref "U2") (pin "12") (pinfunction "VD18_O_12") (pintype "unspecified"))
      (node (ref "U2") (pin "28") (pinfunction "VD18_28") (pintype "unspecified"))
    )
    (net (code "11") (name "3V3Hub") (class "Default")
      (node (ref "C10") (pin "2") (pinfunction "2_2") (pintype "input"))
      (node (ref "Q7") (pin "1") (pinfunction "1_1") (pintype "input"))
      (node (ref "R2") (pin "2") (pinfunction "2_2") (pintype "input"))
      (node (ref "R34") (pin "2") (pinfunction "2_2") (pintype "input"))
      (node (ref "U2") (pin "13") (pinfunction "VD33_13") (pintype "unspecified"))
      (node (ref "U2") (pin "19") (pinfunction "BUSJ_19") (pintype "unspecified"))
      (node (ref "U2") (pin "21") (pinfunction "VD33_O_21") (pintype "unspecified"))
      (node (ref "U2") (pin "26") (pinfunction "OVCJ_26") (pintype "unspecified"))
    )
    (net (code "12") (name "A") (class "Default")
      (node (ref "CN1") (pin "4") (pinfunction "4_4") (pintype "unspecified"))
      (node (ref "D6") (pin "1") (pinfunction "1_1") (pintype "unspecified"))
      (node (ref "J4") (pin "1") (pinfunction "1_1") (pintype "unspecified"))
      (node (ref "R32") (pin "1") (pinfunction "1_1") (pintype "input"))
      (node (ref "R37") (pin "1") (pinfunction "1_1") (pintype "input"))
      (node (ref "R90") (pin "1") (pinfunction "1_1") (pintype "input"))
      (node (ref "ROTARY/485") (pin "4") (pinfunction "4_4") (pintype "unspecified"))
      (node (ref "U8") (pin "6") (pinfunction "A_6") (pintype "unspecified"))
    )
    (net (code "13") (name "A0{slash}WAS") (class "Default")
      (node (ref "C9") (pin "2") (pinfunction "2_2") (pintype "unspecified"))
      (node (ref "R13") (pin "1") (pinfunction "1_1") (pintype "input"))
      (node (ref "U1") (pin "6") (pinfunction "SVP_6") (pintype "unspecified"))
      (node (ref "U17") (pin "4") (pinfunction "AIN0_4") (pintype "unspecified"))
      (node (ref "U5") (pin "23") (pinfunction "PC0(ADC0/PCINT8)_23") (pintype "unspecified"))
    )
    (net (code "14") (name "A1{slash}Ch_B") (class "Default")
      (node (ref "R91") (pin "2") (pinfunction "2_2") (pintype "input"))
      (node (ref "U1") (pin "24") (pinfunction "IO4_24") (pintype "unspecified"))
      (node (ref "U5") (pin "24") (pinfunction "PC1(ADC1/PCINT9)_24") (pintype "unspecified"))
    )
    (net (code "15") (name "A2{slash}SafeSense") (class "Default")
      (node (ref "R25") (pin "1") (pinfunction "1_1") (pintype "input"))
      (node (ref "R48") (pin "2") (pinfunction "2_2") (pintype "input"))
      (node (ref "R53") (pin "1") (pinfunction "1_1") (pintype "unspecified"))
      (node (ref "R54") (pin "1") (pinfunction "1_1") (pintype "unspecified"))
      (node (ref "U5") (pin "25") (pinfunction "PC2(ADC2/PCINT10)_25") (pintype "unspecified"))
    )
    (net (code "16") (name "A3{slash}Out") (class "Default")
      (node (ref "R33") (pin "2") (pinfunction "2_2") (pintype "input"))
      (node (ref "R77") (pin "1") (pinfunction "1_1") (pintype "input"))
      (node (ref "U5") (pin "26") (pinfunction "PC3(ADC3/PCINT11)_26") (pintype "unspecified"))
    )
    (net (code "17") (name "A4{slash}SDA") (class "Default")
      (node (ref "ARDU1") (pin "5") (pinfunction "5_5") (pintype "unspecified"))
      (node (ref "J9") (pin "5") (pinfunction "5_5") (pintype "unspecified"))
      (node (ref "QWIIC") (pin "3") (pinfunction "SDA_3") (pintype "unspecified"))
      (node (ref "R30") (pin "1") (pinfunction "1_1") (pintype "input"))
      (node (ref "U1") (pin "15") (pinfunction "IO21_15") (pintype "unspecified"))
      (node (ref "U15") (pin "2") (pinfunction "SDA/TX_2") (pintype "bidirectional"))
      (node (ref "U17") (pin "9") (pinfunction "SDA_9") (pintype "unspecified"))
      (node (ref "U18") (pin "6") (pinfunction "SDA_6") (pintype "unspecified"))
      (node (ref "U5") (pin "27") (pinfunction "PC4(ADC4/SDA/PCINT12)_27") (pintype "unspecified"))
    )
    (net (code "18") (name "A5{slash}SCL") (class "Default")
      (node (ref "ARDU1") (pin "4") (pinfunction "4_4") (pintype "unspecified"))
      (node (ref "J9") (pin "6") (pinfunction "6_6") (pintype "unspecified"))
      (node (ref "QWIIC") (pin "4") (pinfunction "SCL_4") (pintype "unspecified"))
      (node (ref "R29") (pin "1") (pinfunction "1_1") (pintype "input"))
      (node (ref "U1") (pin "11") (pinfunction "IO22_11") (pintype "unspecified"))
      (node (ref "U15") (pin "3") (pinfunction "SCL/RX_3") (pintype "bidirectional"))
      (node (ref "U17") (pin "10") (pinfunction "SCL_10") (pintype "unspecified"))
      (node (ref "U18") (pin "4") (pinfunction "SCL_4") (pintype "unspecified"))
      (node (ref "U5") (pin "28") (pinfunction "PC5(ADC5/SCL/PCINT13)_28") (pintype "unspecified"))
    )
    (net (code "19") (name "A7{slash}CurrSen") (class "Default")
      (node (ref "C57") (pin "2") (pinfunction "2_2") (pintype "input"))
      (node (ref "R28") (pin "1") (pinfunction "1_1") (pintype "unspecified"))
      (node (ref "U1") (pin "13") (pinfunction "IO35_13") (pintype "unspecified"))
      (node (ref "U5") (pin "22") (pinfunction "ADC7_22") (pintype "unspecified"))
    )
    (net (code "20") (name "Aux") (class "Default")
      (node (ref "J8") (pin "2") (pinfunction "2_2") (pintype "unspecified"))
      (node (ref "POWER") (pin "5") (pinfunction "5_5") (pintype "unspecified"))
    )
    (net (code "21") (name "A{slash}RtSw") (class "Default")
      (node (ref "C24") (pin "2") (pinfunction "2_2") (pintype "input"))
      (node (ref "C27") (pin "2") (pinfunction "2_2") (pintype "unspecified"))
      (node (ref "Q4") (pin "1") (pinfunction "G_1") (pintype "unspecified"))
      (node (ref "R36") (pin "2") (pinfunction "2_2") (pintype "input"))
      (node (ref "R40") (pin "2") (pinfunction "2_2") (pintype "input"))
      (node (ref "U17") (pin "6") (pinfunction "AIN2_6") (pintype "unspecified"))
    )
    (net (code "22") (name "A{slash}WkSw") (class "Default")
      (node (ref "C25") (pin "2") (pinfunction "2_2") (pintype "input"))
      (node (ref "C29") (pin "2") (pinfunction "2_2") (pintype "unspecified"))
      (node (ref "Q3") (pin "1") (pinfunction "G_1") (pintype "unspecified"))
      (node (ref "R45") (pin "2") (pinfunction "2_2") (pintype "input"))
      (node (ref "R47") (pin "2") (pinfunction "2_2") (pintype "input"))
      (node (ref "U1") (pin "17") (pinfunction "IO33_17") (pintype "unspecified"))
      (node (ref "U17") (pin "7") (pinfunction "AIN3_7") (pintype "unspecified"))
    )
    (net (code "23") (name "B") (class "Default")
      (node (ref "CN1") (pin "2") (pinfunction "2_2") (pintype "unspecified"))
      (node (ref "D6") (pin "2") (pinfunction "2_2") (pintype "unspecified"))
      (node (ref "R31") (pin "1") (pinfunction "1_1") (pintype "input"))
      (node (ref "R38") (pin "1") (pinfunction "1_1") (pintype "input"))
      (node (ref "R91") (pin "1") (pinfunction "1_1") (pintype "input"))
      (node (ref "R92") (pin "2") (pinfunction "2_2") (pintype "input"))
      (node (ref "ROTARY/485") (pin "2") (pinfunction "2_2") (pintype "unspecified"))
      (node (ref "U8") (pin "7") (pinfunction "B_7") (pintype "unspecified"))
    )
    (net (code "24") (name "CAN+") (class "Default")
      (node (ref "CAN") (pin "1") (pinfunction "+_1") (pintype "unspecified"))
      (node (ref "CN11") (pin "1") (pinfunction "1_1") (pintype "unspecified"))
      (node (ref "F2") (pin "2") (pinfunction "2_2") (pintype "unspecified"))
      (node (ref "R71") (pin "2") (pinfunction "2_2") (pintype "input"))
    )
    (net (code "25") (name "CANB+") (class "Default")
      (node (ref "CANB") (pin "1") (pinfunction "+_1") (pintype "unspecified"))
      (node (ref "CN12") (pin "1") (pinfunction "1_1") (pintype "unspecified"))
      (node (ref "F3") (pin "2") (pinfunction "2_2") (pintype "unspecified"))
      (node (ref "R72") (pin "2") (pinfunction "2_2") (pintype "input"))
    )
    (net (code "26") (name "CANH") (class "Default")
      (node (ref "CAN") (pin "4") (pinfunction "4_4") (pintype "unspecified"))
      (node (ref "CN11") (pin "4") (pinfunction "4_4") (pintype "unspecified"))
      (node (ref "D5") (pin "2") (pinfunction "2_2") (pintype "unspecified"))
      (node (ref "R60") (pin "1") (pinfunction "1_1") (pintype "input"))
      (node (ref "U7") (pin "7") (pinfunction "CANH_7") (pintype "unspecified"))
    )
    (net (code "27") (name "CANH1") (class "Default")
      (node (ref "CANB") (pin "4") (pinfunction "4_4") (pintype "unspecified"))
      (node (ref "CN12") (pin "4") (pinfunction "4_4") (pintype "unspecified"))
      (node (ref "D7") (pin "1") (pinfunction "1_1") (pintype "unspecified"))
      (node (ref "R65") (pin "1") (pinfunction "1_1") (pintype "input"))
      (node (ref "U12") (pin "7") (pinfunction "CANH_7") (pintype "unspecified"))
    )
    (net (code "28") (name "CANL") (class "Default")
      (node (ref "CAN") (pin "2") (pinfunction "2_2") (pintype "unspecified"))
      (node (ref "CN11") (pin "2") (pinfunction "2_2") (pintype "unspecified"))
      (node (ref "D5") (pin "1") (pinfunction "1_1") (pintype "unspecified"))
      (node (ref "J2") (pin "3") (pinfunction "3_3") (pintype "unspecified"))
      (node (ref "U7") (pin "6") (pinfunction "CANL_6") (pintype "unspecified"))
    )
    (net (code "29") (name "CANL1") (class "Default")
      (node (ref "CANB") (pin "2") (pinfunction "2_2") (pintype "unspecified"))
      (node (ref "CN12") (pin "2") (pinfunction "2_2") (pintype "unspecified"))
      (node (ref "D7") (pin "2") (pinfunction "2_2") (pintype "unspecified"))
      (node (ref "J3") (pin "3") (pinfunction "3_3") (pintype "unspecified"))
      (node (ref "U12") (pin "6") (pinfunction "CANL_6") (pintype "unspecified"))
    )
    (net (code "30") (name "CC11") (class "Default")
      (node (ref "CN8") (pin "1") (pinfunction "1_1") (pintype "unspecified"))
      (node (ref "TO_PC") (pin "A5") (pinfunction "CC1_A5") (pintype "unspecified"))
    )
    (net (code "31") (name "CC12") (class "Default")
      (node (ref "CN10") (pin "1") (pinfunction "1_1") (pintype "unspecified"))
      (node (ref "CN9") (pin "1") (pinfunction "1_1") (pintype "unspecified"))
      (node (ref "DC/AUX") (pin "A5") (pinfunction "CC1_A5") (pintype "unspecified"))
    )
    (net (code "32") (name "CC21") (class "Default")
      (node (ref "CN8") (pin "2") (pinfunction "2_2") (pintype "unspecified"))
      (node (ref "TO_PC") (pin "B5") (pinfunction "CC2_B5") (pintype "unspecified"))
    )
    (net (code "33") (name "CC22") (class "Default")
      (node (ref "CN10") (pin "2") (pinfunction "2_2") (pintype "unspecified"))
      (node (ref "CN9") (pin "2") (pinfunction "2_2") (pintype "unspecified"))
      (node (ref "DC/AUX") (pin "B5") (pinfunction "CC2_B5") (pintype "unspecified"))
    )
    (net (code "34") (name "CurrentSense") (class "Default")
      (node (ref "R12") (pin "2") (pinfunction "2_2") (pintype "input"))
      (node (ref "R20") (pin "1") (pinfunction "1_1") (pintype "input"))
      (node (ref "R28") (pin "2") (pinfunction "2_2") (pintype "unspecified"))
      (node (ref "U10") (pin "6") (pinfunction "IS_6") (pintype "unspecified"))
      (node (ref "U14") (pin "4") (pinfunction "IS_4") (pintype "unspecified"))
      (node (ref "U9") (pin "6") (pinfunction "IS_6") (pintype "unspecified"))
    )
    (net (code "35") (name "D0{slash}RX") (class "Default")
      (node (ref "R9") (pin "1") (pinfunction "1_1") (pintype "input"))
      (node (ref "U5") (pin "30") (pinfunction "PD0(RXD/PCINT16)_30") (pintype "unspecified"))
    )
    (net (code "36") (name "D1{slash}TX") (class "Default")
      (node (ref "R7") (pin "2") (pinfunction "2_2") (pintype "input"))
      (node (ref "TXD") (pin "1") (pinfunction "-_1") (pintype "input"))
      (node (ref "U5") (pin "31") (pinfunction "PD1(TXD/PCINT17)_31") (pintype "unspecified"))
    )
    (net (code "37") (name "D2{slash}Ch_A") (class "Default")
      (node (ref "R90") (pin "2") (pinfunction "2_2") (pintype "input"))
      (node (ref "U1") (pin "16") (pinfunction "IO32_16") (pintype "unspecified"))
      (node (ref "U5") (pin "32") (pinfunction "PD2(INT0/PCINT18)_32") (pintype "unspecified"))
    )
    (net (code "38") (name "D3{slash}PWM0") (class "Default")
      (node (ref "R27") (pin "1") (pinfunction "1_1") (pintype "input"))
      (node (ref "R55") (pin "1") (pinfunction "1_1") (pintype "unspecified"))
      (node (ref "U1") (pin "8") (pinfunction "IO27_8") (pintype "unspecified"))
      (node (ref "U5") (pin "1") (pinfunction "(PCINT19/OC2B/INT1)PD3_1") (pintype "unspecified"))
    )
    (net (code "39") (name "D4{slash}INH") (class "Default")
      (node (ref "Q12") (pin "2") (pinfunction "2_2") (pintype "input"))
      (node (ref "U1") (pin "32") (pinfunction "IO2_32") (pintype "unspecified"))
      (node (ref "U5") (pin "2") (pinfunction "(PCINT20/XCK/T0)PD4_2") (pintype "unspecified"))
    )
    (net (code "40") (name "D5{slash}En") (class "Default")
      (node (ref "CN18") (pin "1") (pinfunction "1_1") (pintype "unspecified"))
      (node (ref "R59") (pin "2") (pinfunction "2_2") (pintype "input"))
      (node (ref "STEERING") (pin "5") (pinfunction "5_5") (pintype "unspecified"))
      (node (ref "U14") (pin "6") (pinfunction "OUT_6") (pintype "unspecified"))
      (node (ref "U14") (pin "7") (pinfunction "OUT_7") (pintype "unspecified"))
      (node (ref "U14") (pin "8") (pinfunction "OUT_8") (pintype "unspecified"))
    )
    (net (code "41") (name "D5{slash}Servo") (class "Default")
      (node (ref "R59") (pin "1") (pinfunction "1_1") (pintype "input"))
      (node (ref "R96") (pin "2") (pinfunction "2_2") (pintype "input"))
      (node (ref "U1") (pin "23") (pinfunction "IO16_23") (pintype "unspecified"))
      (node (ref "U5") (pin "9") (pinfunction "(PCINT21/OC0B/T1)PD5_9") (pintype "unspecified"))
    )
    (net (code "42") (name "D6{slash}StSw") (class "Default")
      (node (ref "Q1") (pin "3") (pinfunction "D_3") (pintype "unspecified"))
      (node (ref "Q5") (pin "3") (pinfunction "D_3") (pintype "unspecified"))
      (node (ref "R94") (pin "2") (pinfunction "2_2") (pintype "input"))
      (node (ref "U1") (pin "21") (pinfunction "IO34_21") (pintype "unspecified"))
      (node (ref "U5") (pin "10") (pinfunction "(PCINT22/OC0A/AIN0)PD6_10") (pintype "unspecified"))
    )
    (net (code "43") (name "D7{slash}WkSw") (class "Default")
      (node (ref "Q3") (pin "3") (pinfunction "D_3") (pintype "unspecified"))
      (node (ref "U5") (pin "11") (pinfunction "(PCINT23/AIN1)PD7_11") (pintype "unspecified"))
    )
    (net (code "44") (name "D8{slash}RtSw") (class "Default")
      (node (ref "Q4") (pin "3") (pinfunction "D_3") (pintype "unspecified"))
      (node (ref "U5") (pin "12") (pinfunction "(PCINT0/CLKO/ICP1)PB0_12") (pintype "unspecified"))
    )
    (net (code "45") (name "D9{slash}PWM1") (class "Default")
      (node (ref "R26") (pin "1") (pinfunction "1_1") (pintype "input"))
      (node (ref "R62") (pin "2") (pinfunction "2_2") (pintype "unspecified"))
      (node (ref "U1") (pin "10") (pinfunction "IO26_10") (pintype "unspecified"))
      (node (ref "U5") (pin "13") (pinfunction "(PCINT1/OC1A)PB1_13") (pintype "unspecified"))
    )
    (net (code "46") (name "D10{slash}nCS") (class "Default")
      (node (ref "P1") (pin "7") (pinfunction "7_7") (pintype "unspecified"))
      (node (ref "U1") (pin "26") (pinfunction "IO5_26") (pintype "unspecified"))
      (node (ref "U5") (pin "14") (pinfunction "(PCINT2/SS#/OC1B)PB2_14") (pintype "unspecified"))
    )
    (net (code "47") (name "D11{slash}MOSI") (class "Default")
      (node (ref "P1") (pin "5") (pinfunction "5_5") (pintype "unspecified"))
      (node (ref "U1") (pin "22") (pinfunction "IO23_22") (pintype "unspecified"))
      (node (ref "U5") (pin "15") (pinfunction "(PCINT3/OC2A/MOSI)PB3_15") (pintype "unspecified"))
    )
    (net (code "48") (name "D12{slash}MISO") (class "Default")
      (node (ref "P1") (pin "4") (pinfunction "4_4") (pintype "unspecified"))
      (node (ref "R104") (pin "2") (pinfunction "2_2") (pintype "input"))
      (node (ref "U1") (pin "18") (pinfunction "IO19_18") (pintype "unspecified"))
      (node (ref "U5") (pin "16") (pinfunction "(PCINT4/MISO)PB4_16") (pintype "unspecified"))
    )
    (net (code "49") (name "D13{slash}SCK") (class "Default")
      (node (ref "LED") (pin "1") (pinfunction "A_1") (pintype "input"))
      (node (ref "P1") (pin "6") (pinfunction "6_6") (pintype "unspecified"))
      (node (ref "U1") (pin "14") (pinfunction "IO18_14") (pintype "unspecified"))
      (node (ref "U5") (pin "17") (pinfunction "PB5(SCK/PCINT5)_17") (pintype "unspecified"))
    )
    (net (code "50") (name "DN1") (class "Default")
      (node (ref "CN8") (pin "6") (pinfunction "6_6") (pintype "unspecified"))
      (node (ref "TO_PC") (pin "A7") (pinfunction "DN1_A7") (pintype "unspecified"))
      (node (ref "TO_PC") (pin "B7") (pinfunction "DN2_B7") (pintype "unspecified"))
    )
    (net (code "51") (name "DN2") (class "Default")
      (node (ref "CN10") (pin "6") (pinfunction "6_6") (pintype "unspecified"))
      (node (ref "CN9") (pin "6") (pinfunction "6_6") (pintype "unspecified"))
      (node (ref "DC/AUX") (pin "A7") (pinfunction "DN1_A7") (pintype "unspecified"))
      (node (ref "DC/AUX") (pin "B7") (pinfunction "DN2_B7") (pintype "unspecified"))
    )
    (net (code "52") (name "DP1") (class "Default")
      (node (ref "CN8") (pin "5") (pinfunction "5_5") (pintype "unspecified"))
      (node (ref "TO_PC") (pin "A6") (pinfunction "DP1_A6") (pintype "unspecified"))
      (node (ref "TO_PC") (pin "B6") (pinfunction "DP2_B6") (pintype "unspecified"))
    )
    (net (code "53") (name "DP2") (class "Default")
      (node (ref "CN10") (pin "5") (pinfunction "5_5") (pintype "unspecified"))
      (node (ref "CN9") (pin "5") (pinfunction "5_5") (pintype "unspecified"))
      (node (ref "DC/AUX") (pin "A6") (pinfunction "DP1_A6") (pintype "unspecified"))
      (node (ref "DC/AUX") (pin "B6") (pinfunction "DP2_B6") (pintype "unspecified"))
    )
    (net (code "54") (name "Dir485") (class "Default")
      (node (ref "R93") (pin "1") (pinfunction "1_1") (pintype "input"))
      (node (ref "R96") (pin "1") (pinfunction "1_1") (pintype "input"))
      (node (ref "U6") (pin "15") (pinfunction "TNOW_15") (pintype "unspecified"))
      (node (ref "U8") (pin "2") (pinfunction "RE#_2") (pintype "unspecified"))
      (node (ref "U8") (pin "3") (pinfunction "DE_3") (pintype "unspecified"))
    )
    (net (code "55") (name "GND") (class "Default")
      (node (ref "12V") (pin "1") (pinfunction "-_1") (pintype "input"))
      (node (ref "ANT1") (pin "1") (pinfunction "K_1") (pintype "input"))
      (node (ref "ANT2") (pin "1") (pinfunction "K_1") (pintype "input"))
      (node (ref "ARDU1") (pin "6") (pinfunction "6_6") (pintype "unspecified"))
      (node (ref "ARDU1") (pin "8") (pinfunction "8_8") (pintype "unspecified"))
      (node (ref "BOOT") (pin "2") (pinfunction "2_2") (pintype "unspecified"))
      (node (ref "C1") (pin "2") (pinfunction "2_2") (pintype "unspecified"))
      (node (ref "C10") (pin "1") (pinfunction "1_1") (pintype "input"))
      (node (ref "C12") (pin "1") (pinfunction "1_1") (pintype "input"))
      (node (ref "C13") (pin "1") (pinfunction "1_1") (pintype "input"))
      (node (ref "C14") (pin "2") (pinfunction "2_2") (pintype "input"))
      (node (ref "C15") (pin "2") (pinfunction "2_2") (pintype "input"))
      (node (ref "C17") (pin "1") (pinfunction "1_1") (pintype "unspecified"))
      (node (ref "C18") (pin "1") (pinfunction "1_1") (pintype "unspecified"))
      (node (ref "C19") (pin "1") (pinfunction "1_1") (pintype "unspecified"))
      (node (ref "C2") (pin "2") (pinfunction "2_2") (pintype "input"))
      (node (ref "C20") (pin "1") (pinfunction "1_1") (pintype "unspecified"))
      (node (ref "C21") (pin "1") (pinfunction "1_1") (pintype "unspecified"))
      (node (ref "C22") (pin "2") (pinfunction "2_2") (pintype "input"))
      (node (ref "C23") (pin "2") (pinfunction "2_2") (pintype "input"))
      (node (ref "C24") (pin "1") (pinfunction "1_1") (pintype "input"))
      (node (ref "C25") (pin "1") (pinfunction "1_1") (pintype "input"))
      (node (ref "C26") (pin "2") (pinfunction "2_2") (pintype "input"))
      (node (ref "C27") (pin "1") (pinfunction "1_1") (pintype "unspecified"))
      (node (ref "C28") (pin "1") (pinfunction "1_1") (pintype "unspecified"))
      (node (ref "C29") (pin "1") (pinfunction "1_1") (pintype "unspecified"))
      (node (ref "C3") (pin "2") (pinfunction "2_2") (pintype "unspecified"))
      (node (ref "C32") (pin "2") (pinfunction "2_2") (pintype "unspecified"))
      (node (ref "C33") (pin "1") (pinfunction "1_1") (pintype "unspecified"))
      (node (ref "C34") (pin "2") (pinfunction "2_2") (pintype "input"))
      (node (ref "C35") (pin "2") (pinfunction "2_2") (pintype "input"))
      (node (ref "C36") (pin "2") (pinfunction "2_2") (pintype "input"))
      (node (ref "C37") (pin "1") (pinfunction "1_1") (pintype "input"))
      (node (ref "C38") (pin "2") (pinfunction "2_2") (pintype "unspecified"))
      (node (ref "C39") (pin "1") (pinfunction "1_1") (pintype "input"))
      (node (ref "C4") (pin "2") (pinfunction "2_2") (pintype "unspecified"))
      (node (ref "C40") (pin "2") (pinfunction "2_2") (pintype "input"))
      (node (ref "C41") (pin "1") (pinfunction "1_1") (pintype "input"))
      (node (ref "C42") (pin "1") (pinfunction "1_1") (pintype "input"))
      (node (ref "C43") (pin "1") (pinfunction "1_1") (pintype "input"))
      (node (ref "C45") (pin "1") (pinfunction "1_1") (pintype "unspecified"))
      (node (ref "C46") (pin "1") (pinfunction "1_1") (pintype "input"))
      (node (ref "C47") (pin "1") (pinfunction "1_1") (pintype "input"))
      (node (ref "C48") (pin "1") (pinfunction "1_1") (pintype "unspecified"))
      (node (ref "C49") (pin "1") (pinfunction "1_1") (pintype "input"))
      (node (ref "C5") (pin "1") (pinfunction "1_1") (pintype "unspecified"))
      (node (ref "C50") (pin "1") (pinfunction "1_1") (pintype "input"))
      (node (ref "C51") (pin "1") (pinfunction "1_1") (pintype "input"))
      (node (ref "C52") (pin "1") (pinfunction "1_1") (pintype "unspecified"))
      (node (ref "C53") (pin "1") (pinfunction "1_1") (pintype "unspecified"))
      (node (ref "C54") (pin "1") (pinfunction "1_1") (pintype "input"))
      (node (ref "C55") (pin "1") (pinfunction "1_1") (pintype "unspecified"))
      (node (ref "C56") (pin "2") (pinfunction "2_2") (pintype "input"))
      (node (ref "C57") (pin "1") (pinfunction "1_1") (pintype "input"))
      (node (ref "C58") (pin "2") (pinfunction "2_2") (pintype "unspecified"))
      (node (ref "C59") (pin "2") (pinfunction "2_2") (pintype "unspecified"))
      (node (ref "C6") (pin "1") (pinfunction "1_1") (pintype "unspecified"))
      (node (ref "C60") (pin "1") (pinfunction "1_1") (pintype "unspecified"))
      (node (ref "C8") (pin "1") (pinfunction "1_1") (pintype "unspecified"))
      (node (ref "C9") (pin "1") (pinfunction "1_1") (pintype "unspecified"))
      (node (ref "CAN") (pin "3") (pinfunction "-_3") (pintype "unspecified"))
      (node (ref "CAN") (pin "Shield") (pinfunction "Shield_Shield") (pintype "unspecified"))
      (node (ref "CANB") (pin "3") (pinfunction "-_3") (pintype "unspecified"))
      (node (ref "CANB") (pin "Shield") (pinfunction "Shield_Shield") (pintype "unspecified"))
      (node (ref "CN1") (pin "3") (pinfunction "3_3") (pintype "unspecified"))
      (node (ref "CN10") (pin "4") (pinfunction "4_4") (pintype "unspecified"))
      (node (ref "CN11") (pin "3") (pinfunction "3_3") (pintype "unspecified"))
      (node (ref "CN12") (pin "3") (pinfunction "3_3") (pintype "unspecified"))
      (node (ref "CN13") (pin "4") (pinfunction "4_4") (pintype "unspecified"))
      (node (ref "CN14") (pin "4") (pinfunction "4_4") (pintype "unspecified"))
      (node (ref "CN15") (pin "2") (pinfunction "2_2") (pintype "unspecified"))
      (node (ref "CN2") (pin "4") (pinfunction "4_4") (pintype "unspecified"))
      (node (ref "CN3") (pin "1") (pinfunction "1_1") (pintype "unspecified"))
      (node (ref "CN3") (pin "2") (pinfunction "2_2") (pintype "unspecified"))
      (node (ref "CN4") (pin "3") (pinfunction "3_3") (pintype "unspecified"))
      (node (ref "CN5") (pin "2") (pinfunction "2_2") (pintype "unspecified"))
      (node (ref "CN6") (pin "3") (pinfunction "3_3") (pintype "unspecified"))
      (node (ref "CN6") (pin "5") (pinfunction "5_5") (pintype "unspecified"))
      (node (ref "CN6") (pin "9") (pinfunction "9_9") (pintype "unspecified"))
      (node (ref "CN7") (pin "2") (pinfunction "2_2") (pintype "unspecified"))
      (node (ref "CN8") (pin "4") (pinfunction "4_4") (pintype "unspecified"))
      (node (ref "CN9") (pin "4") (pinfunction "4_4") (pintype "unspecified"))
      (node (ref "D2") (pin "1") (pinfunction "K_1") (pintype "unspecified"))
      (node (ref "D5") (pin "3") (pinfunction "3_3") (pintype "unspecified"))
      (node (ref "D6") (pin "3") (pinfunction "3_3") (pintype "unspecified"))
      (node (ref "D7") (pin "3") (pinfunction "3_3") (pintype "unspecified"))
      (node (ref "DC/AUX") (pin "1") (pinfunction "EP_1") (pintype "unspecified"))
      (node (ref "DC/AUX") (pin "2") (pinfunction "EP_2") (pintype "unspecified"))
      (node (ref "DC/AUX") (pin "3") (pinfunction "EP_3") (pintype "unspecified"))
      (node (ref "DC/AUX") (pin "4") (pinfunction "EP_4") (pintype "unspecified"))
      (node (ref "DC/AUX") (pin "A1") (pinfunction "GND_A1") (pintype "unspecified"))
      (node (ref "DC/AUX") (pin "A12") (pinfunction "GND_A12") (pintype "unspecified"))
      (node (ref "DC/AUX") (pin "B1") (pinfunction "GND_B1") (pintype "unspecified"))
      (node (ref "DC/AUX") (pin "B12") (pinfunction "GND_B12") (pintype "unspecified"))
      (node (ref "DIFF") (pin "1") (pinfunction "K_1") (pintype "input"))
      (node (ref "GNSS") (pin "4") (pinfunction "gn_4") (pintype "unspecified"))
      (node (ref "GNSS") (pin "Shield") (pinfunction "Shield_Shield") (pintype "unspecified"))
      (node (ref "H1") (pin "3") (pinfunction "3_3") (pintype "unspecified"))
      (node (ref "INPUTS") (pin "3") (pinfunction "-_3") (pintype "unspecified"))
      (node (ref "INPUTS") (pin "Shield") (pinfunction "Shield_Shield") (pintype "unspecified"))
      (node (ref "J7") (pin "1") (pinfunction "1_1") (pintype "unspecified"))
      (node (ref "LED1") (pin "1") (pinfunction "K_1") (pintype "input"))
      (node (ref "LED2") (pin "1") (pinfunction "-_1") (pintype "input"))
      (node (ref "LED3") (pin "1") (pinfunction "K_1") (pintype "input"))
      (node (ref "LED4") (pin "1") (pinfunction "-_1") (pintype "input"))
      (node (ref "P1") (pin "10") (pinfunction "10_10") (pintype "unspecified"))
      (node (ref "POWER") (pin "3") (pinfunction "-_3") (pintype "unspecified"))
      (node (ref "POWER") (pin "Shield") (pinfunction "Shield_Shield") (pintype "unspecified"))
      (node (ref "Q1") (pin "2") (pinfunction "S_2") (pintype "unspecified"))
      (node (ref "Q10") (pin "3") (pinfunction "3_3") (pintype "input"))
      (node (ref "Q11") (pin "3") (pinfunction "3_3") (pintype "input"))
      (node (ref "Q3") (pin "2") (pinfunction "S_2") (pintype "unspecified"))
      (node (ref "Q4") (pin "2") (pinfunction "S_2") (pintype "unspecified"))
      (node (ref "Q5") (pin "2") (pinfunction "S_2") (pintype "unspecified"))
      (node (ref "Q6") (pin "2") (pinfunction "S_2") (pintype "unspecified"))
      (node (ref "Q9") (pin "3") (pinfunction "3_3") (pintype "input"))
      (node (ref "QWIIC") (pin "1") (pinfunction "GND_1") (pintype "unspecified"))
      (node (ref "QWIIC") (pin "5") (pinfunction "NC1_5") (pintype "unspecified"))
      (node (ref "QWIIC") (pin "6") (pinfunction "NC2_6") (pintype "unspecified"))
      (node (ref "R1") (pin "1") (pinfunction "1_1") (pintype "input"))
      (node (ref "R10") (pin "1") (pinfunction "1_1") (pintype "input"))
      (node (ref "R100") (pin "1") (pinfunction "1_1") (pintype "input"))
      (node (ref "R102") (pin "2") (pinfunction "2_2") (pintype "input"))
      (node (ref "R14") (pin "1") (pinfunction "1_1") (pintype "input"))
      (node (ref "R16") (pin "2") (pinfunction "2_2") (pintype "input"))
      (node (ref "R18") (pin "1") (pinfunction "1_1") (pintype "input"))
      (node (ref "R25") (pin "2") (pinfunction "2_2") (pintype "input"))
      (node (ref "R26") (pin "2") (pinfunction "2_2") (pintype "input"))
      (node (ref "R27") (pin "2") (pinfunction "2_2") (pintype "input"))
      (node (ref "R36") (pin "1") (pinfunction "1_1") (pintype "input"))
      (node (ref "R38") (pin "2") (pinfunction "2_2") (pintype "input"))
      (node (ref "R42") (pin "2") (pinfunction "2_2") (pintype "input"))
      (node (ref "R43") (pin "1") (pinfunction "1_1") (pintype "input"))
      (node (ref "R44") (pin "1") (pinfunction "1_1") (pintype "input"))
      (node (ref "R46") (pin "1") (pinfunction "1_1") (pintype "input"))
      (node (ref "R47") (pin "1") (pinfunction "1_1") (pintype "input"))
      (node (ref "R70") (pin "1") (pinfunction "1_1") (pintype "input"))
      (node (ref "R77") (pin "2") (pinfunction "2_2") (pintype "input"))
      (node (ref "R81") (pin "2") (pinfunction "2_2") (pintype "input"))
      (node (ref "R82") (pin "2") (pinfunction "2_2") (pintype "input"))
      (node (ref "R93") (pin "2") (pinfunction "2_2") (pintype "input"))
      (node (ref "R99") (pin "2") (pinfunction "2_2") (pintype "input"))
      (node (ref "ROTARY/485") (pin "3") (pinfunction "-_3") (pintype "unspecified"))
      (node (ref "ROTARY/485") (pin "Shield") (pinfunction "Shield_Shield") (pintype "unspecified"))
      (node (ref "STEERING") (pin "3") (pinfunction "-_3") (pintype "unspecified"))
      (node (ref "STEERING") (pin "Shield") (pinfunction "Shield_Shield") (pintype "unspecified"))
      (node (ref "TO_PC") (pin "1") (pinfunction "EP_1") (pintype "unspecified"))
      (node (ref "TO_PC") (pin "2") (pinfunction "EP_2") (pintype "unspecified"))
      (node (ref "TO_PC") (pin "3") (pinfunction "EP_3") (pintype "unspecified"))
      (node (ref "TO_PC") (pin "4") (pinfunction "EP_4") (pintype "unspecified"))
      (node (ref "TO_PC") (pin "A1") (pinfunction "GND_A1") (pintype "unspecified"))
      (node (ref "TO_PC") (pin "A12") (pinfunction "GND_A12") (pintype "unspecified"))
      (node (ref "TO_PC") (pin "B1") (pinfunction "GND_B1") (pintype "unspecified"))
      (node (ref "TO_PC") (pin "B12") (pinfunction "GND_B12") (pintype "unspecified"))
      (node (ref "U1") (pin "1") (pinfunction "GND_1") (pintype "unspecified"))
      (node (ref "U1") (pin "27") (pinfunction "GND_27") (pintype "unspecified"))
      (node (ref "U1") (pin "4") (pinfunction "GND_4") (pintype "unspecified"))
      (node (ref "U11") (pin "14") (pinfunction "USB1_AVSSTX3V3_14") (pintype "unspecified"))
      (node (ref "U11") (pin "2") (pinfunction "VSS_2") (pintype "unspecified"))
      (node (ref "U11") (pin "22") (pinfunction "VSS_22") (pintype "unspecified"))
      (node (ref "U11") (pin "30") (pinfunction "VSSA/VREFN_30") (pintype "unspecified"))
      (node (ref "U11") (pin "34") (pinfunction "VSS_34") (pintype "unspecified"))
      (node (ref "U11") (pin "49") (pinfunction "VSS_49") (pintype "unspecified"))
      (node (ref "U11") (pin "51") (pinfunction "RTCXIN_51") (pintype "unspecified"))
      (node (ref "U11") (pin "53") (pinfunction "VSS_53") (pintype "unspecified"))
      (node (ref "U11") (pin "6") (pinfunction "USB1_AVSSC_6") (pintype "unspecified"))
      (node (ref "U11") (pin "71") (pinfunction "VSS_71") (pintype "unspecified"))
      (node (ref "U11") (pin "79") (pinfunction "VSS_79") (pintype "unspecified"))
      (node (ref "U11") (pin "96") (pinfunction "VSS_96") (pintype "unspecified"))
      (node (ref "U12") (pin "2") (pinfunction "GND_2") (pintype "unspecified"))
      (node (ref "U12") (pin "8") (pinfunction "S_8") (pintype "unspecified"))
      (node (ref "U13") (pin "1") (pinfunction "GND_1") (pintype "unspecified"))
      (node (ref "U15") (pin "6") (pinfunction "GND_6") (pintype "passive"))
      (node (ref "U16") (pin "14") (pinfunction "GND_14") (pintype "unspecified"))
      (node (ref "U16") (pin "17") (pinfunction "GND_17") (pintype "unspecified"))
      (node (ref "U16") (pin "20") (pinfunction "GND_20") (pintype "unspecified"))
      (node (ref "U16") (pin "22") (pinfunction "GND_22") (pintype "unspecified"))
      (node (ref "U17") (pin "1") (pinfunction "ADDR_1") (pintype "unspecified"))
      (node (ref "U17") (pin "3") (pinfunction "GND_3") (pintype "unspecified"))
      (node (ref "U18") (pin "10") (pinfunction "GND_10") (pintype "unspecified"))
      (node (ref "U18") (pin "12") (pinfunction "GND_12") (pintype "unspecified"))
      (node (ref "U18") (pin "5") (pinfunction "GND_5") (pintype "unspecified"))
      (node (ref "U18") (pin "7") (pinfunction "SA0_7") (pintype "unspecified"))
      (node (ref "U19") (pin "1") (pinfunction "GND_1") (pintype "unspecified"))
      (node (ref "U2") (pin "1") (pinfunction "VSS_1") (pintype "unspecified"))
      (node (ref "U3") (pin "1") (pinfunction "GND_1") (pintype "unspecified"))
      (node (ref "U4") (pin "1") (pinfunction "GND_1") (pintype "unspecified"))
      (node (ref "U5") (pin "21") (pinfunction "GND_21") (pintype "unspecified"))
      (node (ref "U5") (pin "3") (pinfunction "GND_3") (pintype "unspecified"))
      (node (ref "U5") (pin "5") (pinfunction "GND_5") (pintype "unspecified"))
      (node (ref "U6") (pin "1") (pinfunction "GND_1") (pintype "unspecified"))
      (node (ref "U7") (pin "2") (pinfunction "GND_2") (pintype "unspecified"))
      (node (ref "U7") (pin "8") (pinfunction "S_8") (pintype "unspecified"))
      (node (ref "U8") (pin "5") (pinfunction "GND_5") (pintype "unspecified"))
      (node (ref "USB1") (pin "0") (pinfunction "SHLD_0") (pintype "unspecified"))
      (node (ref "USB1") (pin "4") (pinfunction "GND_4") (pintype "input"))
      (node (ref "USB_AUX") (pin "4") (pinfunction "GND_4") (pintype "unspecified"))
      (node (ref "USB_AUX") (pin "8") (pinfunction "GND_8") (pintype "unspecified"))
      (node (ref "USB_AUX") (pin "9") (pinfunction "9_9") (pintype "unspecified"))
      (node (ref "WAS1") (pin "3") (pinfunction "-_3") (pintype "unspecified"))
      (node (ref "WAS1") (pin "Shield") (pinfunction "Shield_Shield") (pintype "unspecified"))
      (node (ref "X1") (pin "2") (pinfunction "GND_2") (pintype "input"))
      (node (ref "X1") (pin "4") (pinfunction "GND_4") (pintype "input"))
      (node (ref "X2") (pin "2") (pinfunction "GND_2") (pintype "unspecified"))
      (node (ref "X2") (pin "4") (pinfunction "GND_4") (pintype "unspecified"))
      (node (ref "X3") (pin "2") (pinfunction "GND_2") (pintype "unspecified"))
      (node (ref "X3") (pin "4") (pinfunction "GND_4") (pintype "unspecified"))
    )
    (net (code "56") (name "GNSS+") (class "Default")
      (node (ref "F1") (pin "1") (pinfunction "1_1") (pintype "unspecified"))
      (node (ref "GNSS") (pin "2") (pinfunction "wh/gn_2") (pintype "unspecified"))
      (node (ref "R64") (pin "2") (pinfunction "2_2") (pintype "input"))
    )
    (net (code "57") (name "INH") (class "Default")
      (node (ref "R61") (pin "2") (pinfunction "2_2") (pintype "unspecified"))
      (node (ref "U10") (pin "3") (pinfunction "INH_3") (pintype "unspecified"))
      (node (ref "U14") (pin "2") (pinfunction "IN_2") (pintype "unspecified"))
      (node (ref "U14") (pin "3") (pinfunction "DEN_3") (pintype "unspecified"))
      (node (ref "U9") (pin "3") (pinfunction "INH_3") (pintype "unspecified"))
    )
    (net (code "58") (name "In+") (class "Default")
      (node (ref "ARDU1") (pin "7") (pinfunction "7_7") (pintype "unspecified"))
      (node (ref "CN17") (pin "1") (pinfunction "1_1") (pintype "unspecified"))
      (node (ref "F4") (pin "2") (pinfunction "2_2") (pintype "unspecified"))
      (node (ref "INPUTS") (pin "2") (pinfunction "2_2") (pintype "unspecified"))
      (node (ref "R73") (pin "2") (pinfunction "2_2") (pintype "input"))
    )
    (net (code "59") (name "In0") (class "Default")
      (node (ref "CN17") (pin "4") (pinfunction "4_4") (pintype "unspecified"))
      (node (ref "INPUTS") (pin "5") (pinfunction "5_5") (pintype "unspecified"))
      (node (ref "STEER") (pin "2") (pinfunction "A_2") (pintype "input"))
    )
    (net (code "60") (name "In1") (class "Default")
      (node (ref "CN17") (pin "2") (pinfunction "2_2") (pintype "unspecified"))
      (node (ref "INPUTS") (pin "1") (pinfunction "+_1") (pintype "unspecified"))
      (node (ref "WORK") (pin "2") (pinfunction "A_2") (pintype "input"))
    )
    (net (code "61") (name "In2") (class "Default")
      (node (ref "CN17") (pin "3") (pinfunction "3_3") (pintype "unspecified"))
      (node (ref "INPUTS") (pin "4") (pinfunction "4_4") (pintype "unspecified"))
      (node (ref "REMOTE") (pin "2") (pinfunction "A_2") (pintype "input"))
    )
    (net (code "62") (name "MA") (class "Default")
      (node (ref "CN18") (pin "4") (pinfunction "4_4") (pintype "unspecified"))
      (node (ref "M1") (pin "2") (pinfunction "A_2") (pintype "input"))
      (node (ref "M2") (pin "1") (pinfunction "K_1") (pintype "input"))
      (node (ref "STEERING") (pin "4") (pinfunction "4_4") (pintype "unspecified"))
      (node (ref "U10") (pin "8") (pinfunction "OUT_8") (pintype "unspecified"))
    )
    (net (code "63") (name "MB") (class "Default")
      (node (ref "CN18") (pin "2") (pinfunction "2_2") (pintype "unspecified"))
      (node (ref "R24") (pin "2") (pinfunction "2_2") (pintype "input"))
      (node (ref "STEERING") (pin "2") (pinfunction "2_2") (pintype "unspecified"))
      (node (ref "U9") (pin "4") (pinfunction "OUT_4") (pintype "unspecified"))
      (node (ref "U9") (pin "8") (pinfunction "OUT_8") (pintype "unspecified"))
    )
    (net (code "64") (name "Net-(3V3--)") (class "Default")
      (node (ref "3V3") (pin "1") (pinfunction "-_1") (pintype "input"))
      (node (ref "R102") (pin "1") (pinfunction "1_1") (pintype "input"))
    )
    (net (code "65") (name "Net-(5V--)") (class "Default")
      (node (ref "5V") (pin "1") (pinfunction "-_1") (pintype "input"))
      (node (ref "R70") (pin "2") (pinfunction "2_2") (pintype "input"))
    )
    (net (code "66") (name "Net-(12V-+)") (class "Default")
      (node (ref "12V") (pin "2") (pinfunction "+_2") (pintype "input"))
      (node (ref "R100") (pin "2") (pinfunction "2_2") (pintype "input"))
      (node (ref "R15") (pin "1") (pinfunction "1_1") (pintype "input"))
      (node (ref "U4") (pin "5") (pinfunction "EN_5") (pintype "unspecified"))
    )
    (net (code "67") (name "Net-(ANT1-A)") (class "Default")
      (node (ref "ANT1") (pin "2") (pinfunction "A_2") (pintype "input"))
      (node (ref "R56") (pin "1") (pinfunction "1_1") (pintype "input"))
    )
    (net (code "68") (name "Net-(ANT2-A)") (class "Default")
      (node (ref "ANT2") (pin "2") (pinfunction "A_2") (pintype "input"))
      (node (ref "R52") (pin "1") (pinfunction "1_1") (pintype "input"))
    )
    (net (code "69") (name "Net-(ARDU-A)") (class "Default")
      (node (ref "ARDU") (pin "2") (pinfunction "A_2") (pintype "input"))
      (node (ref "AUX0") (pin "2") (pinfunction "A_2") (pintype "input"))
      (node (ref "AUX1") (pin "1") (pinfunction "-_1") (pintype "input"))
      (node (ref "GNSS_") (pin "1") (pinfunction "-_1") (pintype "input"))
      (node (ref "U2") (pin "22") (pinfunction "DRV_22") (pintype "unspecified"))
      (node (ref "USB:") (pin "2") (pinfunction "A_2") (pintype "input"))
    )
    (net (code "70") (name "Net-(ARDU-K)") (class "Default")
      (node (ref "ARDU") (pin "1") (pinfunction "K_1") (pintype "input"))
      (node (ref "AUX1") (pin "2") (pinfunction "+_2") (pintype "input"))
      (node (ref "R4") (pin "1") (pinfunction "1_1") (pintype "input"))
    )
    (net (code "71") (name "Net-(AUX0-K)") (class "Default")
      (node (ref "AUX0") (pin "1") (pinfunction "K_1") (pintype "input"))
      (node (ref "GNSS_") (pin "2") (pinfunction "+_2") (pintype "input"))
      (node (ref "R3") (pin "2") (pinfunction "2_2") (pintype "input"))
    )
    (net (code "72") (name "Net-(C52-Pad2)") (class "Default")
      (node (ref "C52") (pin "2") (pinfunction "2_2") (pintype "unspecified"))
      (node (ref "C62") (pin "2") (pinfunction "2_2") (pintype "input"))
      (node (ref "L1") (pin "2") (pinfunction "2_2") (pintype "unspecified"))
      (node (ref "L2") (pin "1") (pinfunction "1_1") (pintype "input"))
      (node (ref "R19") (pin "2") (pinfunction "2_2") (pintype "input"))
    )
    (net (code "73") (name "Net-(CHA-K)") (class "Default")
      (node (ref "CHA") (pin "1") (pinfunction "K_1") (pintype "input"))
      (node (ref "R32") (pin "2") (pinfunction "2_2") (pintype "input"))
    )
    (net (code "74") (name "Net-(CHB-K)") (class "Default")
      (node (ref "CHB") (pin "1") (pinfunction "K_1") (pintype "input"))
      (node (ref "R31") (pin "2") (pinfunction "2_2") (pintype "input"))
    )
    (net (code "75") (name "Net-(CN13-Pad1)") (class "Default")
      (node (ref "CN13") (pin "1") (pinfunction "1_1") (pintype "unspecified"))
      (node (ref "CN14") (pin "1") (pinfunction "1_1") (pintype "unspecified"))
      (node (ref "R46") (pin "2") (pinfunction "2_2") (pintype "input"))
    )
    (net (code "76") (name "Net-(CN13-Pad2)") (class "Default")
      (node (ref "CN13") (pin "2") (pinfunction "2_2") (pintype "unspecified"))
      (node (ref "CN14") (pin "2") (pinfunction "2_2") (pintype "unspecified"))
      (node (ref "R43") (pin "2") (pinfunction "2_2") (pintype "input"))
    )
    (net (code "77") (name "Net-(CN13-Pad3)") (class "Default")
      (node (ref "CN13") (pin "3") (pinfunction "3_3") (pintype "unspecified"))
      (node (ref "CN2") (pin "1") (pinfunction "1_1") (pintype "unspecified"))
      (node (ref "CN3") (pin "5") (pinfunction "5_5") (pintype "unspecified"))
      (node (ref "R50") (pin "1") (pinfunction "1_1") (pintype "input"))
    )
    (net (code "78") (name "Net-(CN14-Pad3)") (class "Default")
      (node (ref "CN14") (pin "3") (pinfunction "3_3") (pintype "unspecified"))
      (node (ref "J1") (pin "1") (pinfunction "1_1") (pintype "unspecified"))
    )
    (net (code "79") (name "Net-(DIFF-A)") (class "Default")
      (node (ref "DIFF") (pin "2") (pinfunction "A_2") (pintype "input"))
      (node (ref "R98") (pin "1") (pinfunction "1_1") (pintype "input"))
    )
    (net (code "80") (name "Net-(FCAN-A)") (class "Default")
      (node (ref "F2") (pin "1") (pinfunction "1_1") (pintype "unspecified"))
      (node (ref "FCAN") (pin "1") (pinfunction "A_1") (pintype "input"))
      (node (ref "J2") (pin "1") (pinfunction "1_1") (pintype "unspecified"))
    )
    (net (code "81") (name "Net-(FCAN-K)") (class "Default")
      (node (ref "FCAN") (pin "2") (pinfunction "K_2") (pintype "input"))
      (node (ref "R71") (pin "1") (pinfunction "1_1") (pintype "input"))
    )
    (net (code "82") (name "Net-(FCAN1-A)") (class "Default")
      (node (ref "F3") (pin "1") (pinfunction "1_1") (pintype "unspecified"))
      (node (ref "FCAN1") (pin "1") (pinfunction "A_1") (pintype "input"))
      (node (ref "J3") (pin "1") (pinfunction "1_1") (pintype "unspecified"))
    )
    (net (code "83") (name "Net-(FCAN1-K)") (class "Default")
      (node (ref "FCAN1") (pin "2") (pinfunction "K_2") (pintype "input"))
      (node (ref "R72") (pin "1") (pinfunction "1_1") (pintype "input"))
    )
    (net (code "84") (name "Net-(FGNSS-K)") (class "Default")
      (node (ref "FGNSS") (pin "2") (pinfunction "K_2") (pintype "input"))
      (node (ref "R64") (pin "1") (pinfunction "1_1") (pintype "input"))
    )
    (net (code "85") (name "Net-(FINP-K)") (class "Default")
      (node (ref "FINP") (pin "2") (pinfunction "K_2") (pintype "input"))
      (node (ref "R73") (pin "1") (pinfunction "1_1") (pintype "input"))
    )
    (net (code "86") (name "Net-(FROT-K)") (class "Default")
      (node (ref "FROT") (pin "2") (pinfunction "K_2") (pintype "input"))
      (node (ref "R75") (pin "1") (pinfunction "1_1") (pintype "input"))
    )
    (net (code "87") (name "Net-(FSER-K)") (class "Default")
      (node (ref "FSER") (pin "2") (pinfunction "K_2") (pintype "input"))
      (node (ref "R76") (pin "2") (pinfunction "2_2") (pintype "input"))
    )
    (net (code "88") (name "Net-(FWAS-K)") (class "Default")
      (node (ref "FWAS") (pin "2") (pinfunction "K_2") (pintype "input"))
      (node (ref "R74") (pin "1") (pinfunction "1_1") (pintype "input"))
    )
    (net (code "89") (name "Net-(GNSS-+_wh{slash}or)") (class "Default")
      (node (ref "GNSS") (pin "1") (pinfunction "+_wh/or_1") (pintype "unspecified"))
      (node (ref "J9") (pin "4") (pinfunction "4_4") (pintype "unspecified"))
    )
    (net (code "90") (name "Net-(GNSS--_or)") (class "Default")
      (node (ref "GNSS") (pin "3") (pinfunction "-_or_3") (pintype "unspecified"))
      (node (ref "J9") (pin "3") (pinfunction "3_3") (pintype "unspecified"))
    )
    (net (code "91") (name "Net-(J2-Pad4)") (class "Default")
      (node (ref "J2") (pin "4") (pinfunction "4_4") (pintype "unspecified"))
      (node (ref "R60") (pin "2") (pinfunction "2_2") (pintype "input"))
    )
    (net (code "92") (name "Net-(J3-Pad4)") (class "Default")
      (node (ref "J3") (pin "4") (pinfunction "4_4") (pintype "unspecified"))
      (node (ref "R65") (pin "2") (pinfunction "2_2") (pintype "input"))
    )
    (net (code "93") (name "Net-(J4-Pad2)") (class "Default")
      (node (ref "J4") (pin "2") (pinfunction "2_2") (pintype "unspecified"))
      (node (ref "R92") (pin "1") (pinfunction "1_1") (pintype "input"))
    )
    (net (code "94") (name "Net-(J8-Pad3)") (class "Default")
      (node (ref "J8") (pin "3") (pinfunction "3_3") (pintype "unspecified"))
      (node (ref "R15") (pin "2") (pinfunction "2_2") (pintype "input"))
    )
    (net (code "95") (name "Net-(LED-K)") (class "Default")
      (node (ref "LED") (pin "2") (pinfunction "K_2") (pintype "input"))
      (node (ref "R10") (pin "2") (pinfunction "2_2") (pintype "input"))
    )
    (net (code "96") (name "Net-(LED1-A)") (class "Default")
      (node (ref "LED1") (pin "2") (pinfunction "A_2") (pintype "input"))
      (node (ref "R84") (pin "1") (pinfunction "1_1") (pintype "input"))
    )
    (net (code "97") (name "Net-(LED2-+)") (class "Default")
      (node (ref "LED2") (pin "2") (pinfunction "+_2") (pintype "input"))
      (node (ref "R85") (pin "1") (pinfunction "1_1") (pintype "input"))
    )
    (net (code "98") (name "Net-(LED3-A)") (class "Default")
      (node (ref "LED3") (pin "2") (pinfunction "A_2") (pintype "input"))
      (node (ref "R86") (pin "1") (pinfunction "1_1") (pintype "input"))
    )
    (net (code "99") (name "Net-(LED4-+)") (class "Default")
      (node (ref "LED4") (pin "2") (pinfunction "+_2") (pintype "input"))
      (node (ref "R87") (pin "1") (pinfunction "1_1") (pintype "input"))
    )
    (net (code "100") (name "Net-(M1-K)") (class "Default")
      (node (ref "M1") (pin "1") (pinfunction "K_1") (pintype "input"))
      (node (ref "M2") (pin "2") (pinfunction "A_2") (pintype "input"))
      (node (ref "R24") (pin "1") (pinfunction "1_1") (pintype "input"))
    )
    (net (code "101") (name "Net-(MOT--)") (class "Default")
      (node (ref "MOT") (pin "1") (pinfunction "-_1") (pintype "input"))
      (node (ref "R49") (pin "2") (pinfunction "2_2") (pintype "input"))
      (node (ref "R51") (pin "1") (pinfunction "1_1") (pintype "input"))
      (node (ref "R8") (pin "1") (pinfunction "1_1") (pintype "input"))
    )
    (net (code "102") (name "Net-(Q1-G)") (class "Default")
      (node (ref "C28") (pin "2") (pinfunction "2_2") (pintype "unspecified"))
      (node (ref "Q1") (pin "1") (pinfunction "G_1") (pintype "unspecified"))
      (node (ref "R41") (pin "2") (pinfunction "2_2") (pintype "input"))
      (node (ref "R44") (pin "2") (pinfunction "2_2") (pintype "input"))
    )
    (net (code "103") (name "Net-(Q2-Pad1)") (class "Default")
      (node (ref "Q2") (pin "1") (pinfunction "1_1") (pintype "input"))
      (node (ref "R8") (pin "2") (pinfunction "2_2") (pintype "input"))
    )
    (net (code "104") (name "Net-(Q2-Pad3)") (class "Default")
      (node (ref "Q2") (pin "3") (pinfunction "3_3") (pintype "input"))
      (node (ref "R63") (pin "1") (pinfunction "1_1") (pintype "unspecified"))
    )
    (net (code "105") (name "Net-(Q6-G)") (class "Default")
      (node (ref "Q6") (pin "1") (pinfunction "G_1") (pintype "unspecified"))
      (node (ref "R33") (pin "1") (pinfunction "1_1") (pintype "input"))
    )
    (net (code "106") (name "Net-(Q8-G)") (class "Default")
      (node (ref "Q8") (pin "4") (pinfunction "G_4") (pintype "unspecified"))
      (node (ref "R35") (pin "2") (pinfunction "2_2") (pintype "input"))
      (node (ref "R39") (pin "2") (pinfunction "2_2") (pintype "input"))
    )
    (net (code "107") (name "Net-(Q9-Pad2)") (class "Default")
      (node (ref "Q9") (pin "2") (pinfunction "2_2") (pintype "input"))
      (node (ref "R58") (pin "1") (pinfunction "1_1") (pintype "input"))
    )
    (net (code "108") (name "Net-(Q10-Pad2)") (class "Default")
      (node (ref "Q10") (pin "2") (pinfunction "2_2") (pintype "input"))
      (node (ref "R57") (pin "1") (pinfunction "1_1") (pintype "input"))
    )
    (net (code "109") (name "Net-(Q12-Pad1)") (class "Default")
      (node (ref "Q12") (pin "1") (pinfunction "1_1") (pintype "input"))
      (node (ref "R42") (pin "1") (pinfunction "1_1") (pintype "input"))
    )
    (net (code "110") (name "Net-(Q12-Pad3)") (class "Default")
      (node (ref "Q12") (pin "3") (pinfunction "3_3") (pintype "input"))
      (node (ref "R61") (pin "1") (pinfunction "1_1") (pintype "unspecified"))
    )
    (net (code "111") (name "Net-(R80-Pad2)") (class "Default")
      (node (ref "R80") (pin "2") (pinfunction "2_2") (pintype "input"))
      (node (ref "R81") (pin "1") (pinfunction "1_1") (pintype "input"))
      (node (ref "R82") (pin "1") (pinfunction "1_1") (pintype "input"))
    )
    (net (code "112") (name "Net-(REMOTE-K)") (class "Default")
      (node (ref "R40") (pin "1") (pinfunction "1_1") (pintype "input"))
      (node (ref "REMOTE") (pin "1") (pinfunction "K_1") (pintype "input"))
    )
    (net (code "113") (name "Net-(RX485-K)") (class "Default")
      (node (ref "R66") (pin "1") (pinfunction "1_1") (pintype "input"))
      (node (ref "RX485") (pin "1") (pinfunction "K_1") (pintype "input"))
    )
    (net (code "114") (name "Net-(RXCAN-K)") (class "Default")
      (node (ref "R68") (pin "1") (pinfunction "1_1") (pintype "input"))
      (node (ref "RXCAN") (pin "1") (pinfunction "K_1") (pintype "input"))
    )
    (net (code "115") (name "Net-(RXCAN1-K)") (class "Default")
      (node (ref "R89") (pin "1") (pinfunction "1_1") (pintype "input"))
      (node (ref "RXCAN1") (pin "1") (pinfunction "K_1") (pintype "input"))
    )
    (net (code "116") (name "Net-(RXD-A)") (class "Default")
      (node (ref "R23") (pin "1") (pinfunction "1_1") (pintype "input"))
      (node (ref "RXD") (pin "2") (pinfunction "A_2") (pintype "input"))
    )
    (net (code "117") (name "Net-(STEER-K)") (class "Default")
      (node (ref "R41") (pin "1") (pinfunction "1_1") (pintype "input"))
      (node (ref "STEER") (pin "1") (pinfunction "K_1") (pintype "input"))
    )
    (net (code "118") (name "Net-(TX485--)") (class "Default")
      (node (ref "R67") (pin "1") (pinfunction "1_1") (pintype "input"))
      (node (ref "TX485") (pin "1") (pinfunction "-_1") (pintype "input"))
    )
    (net (code "119") (name "Net-(TXCAN--)") (class "Default")
      (node (ref "R69") (pin "1") (pinfunction "1_1") (pintype "input"))
      (node (ref "TXCAN") (pin "1") (pinfunction "-_1") (pintype "input"))
    )
    (net (code "120") (name "Net-(TXCAN1--)") (class "Default")
      (node (ref "R88") (pin "1") (pinfunction "1_1") (pintype "input"))
      (node (ref "TXCAN1") (pin "1") (pinfunction "-_1") (pintype "input"))
    )
    (net (code "121") (name "Net-(TXD-+)") (class "Default")
      (node (ref "R22") (pin "1") (pinfunction "1_1") (pintype "input"))
      (node (ref "TXD") (pin "2") (pinfunction "+_2") (pintype "input"))
    )
    (net (code "122") (name "Net-(U1-RES)") (class "Default")
      (node (ref "C55") (pin "2") (pinfunction "2_2") (pintype "unspecified"))
      (node (ref "U1") (pin "2") (pinfunction "RES_2") (pintype "unspecified"))
    )
    (net (code "123") (name "Net-(U2-LED1)") (class "Default")
      (node (ref "R4") (pin "2") (pinfunction "2_2") (pintype "input"))
      (node (ref "U2") (pin "23") (pinfunction "LED1_23") (pintype "unspecified"))
    )
    (net (code "124") (name "Net-(U2-LED2)") (class "Default")
      (node (ref "R3") (pin "1") (pinfunction "1_1") (pintype "input"))
      (node (ref "U2") (pin "24") (pinfunction "LED2_24") (pintype "unspecified"))
    )
    (net (code "125") (name "Net-(U2-REXT)") (class "Default")
      (node (ref "R1") (pin "2") (pinfunction "2_2") (pintype "input"))
      (node (ref "U2") (pin "14") (pinfunction "REXT_14") (pintype "unspecified"))
    )
    (net (code "126") (name "Net-(U2-TESTJ)") (class "Default")
      (node (ref "R2") (pin "1") (pinfunction "1_1") (pintype "input"))
      (node (ref "U2") (pin "27") (pinfunction "TESTJ_27") (pintype "unspecified"))
    )
    (net (code "127") (name "Net-(U2-VBUSM)") (class "Default")
      (node (ref "Q7") (pin "3") (pinfunction "3_3") (pintype "input"))
      (node (ref "R50") (pin "2") (pinfunction "2_2") (pintype "input"))
      (node (ref "U2") (pin "18") (pinfunction "VBUSM_18") (pintype "unspecified"))
    )
    (net (code "128") (name "Net-(U2-XIN)") (class "Default")
      (node (ref "C23") (pin "1") (pinfunction "1_1") (pintype "input"))
      (node (ref "U2") (pin "3") (pinfunction "XIN_3") (pintype "unspecified"))
      (node (ref "X2") (pin "3") (pinfunction "OSC2_3") (pintype "unspecified"))
    )
    (net (code "129") (name "Net-(U2-XOUT)") (class "Default")
      (node (ref "C13") (pin "2") (pinfunction "2_2") (pintype "input"))
      (node (ref "U2") (pin "2") (pinfunction "XOUT_2") (pintype "unspecified"))
      (node (ref "X2") (pin "1") (pinfunction "OSC1_1") (pintype "unspecified"))
    )
    (net (code "130") (name "Net-(U3-DTR#)") (class "Default")
      (node (ref "C7") (pin "2") (pinfunction "2_2") (pintype "unspecified"))
      (node (ref "U3") (pin "13") (pinfunction "DTR#_13") (pintype "unspecified"))
    )
    (net (code "131") (name "Net-(U3-V3)") (class "Default")
      (node (ref "C1") (pin "1") (pinfunction "1_1") (pintype "unspecified"))
      (node (ref "U3") (pin "4") (pinfunction "V3_4") (pintype "unspecified"))
    )
    (net (code "132") (name "Net-(U4-BOOT)") (class "Default")
      (node (ref "C16") (pin "1") (pinfunction "1_1") (pintype "unspecified"))
      (node (ref "U4") (pin "6") (pinfunction "BOOT_6") (pintype "unspecified"))
    )
    (net (code "133") (name "Net-(U5-(PCINT6{slash}XTAL1{slash}TOSC1)PB6)") (class "Default")
      (node (ref "C6") (pin "2") (pinfunction "2_2") (pintype "unspecified"))
      (node (ref "U5") (pin "7") (pinfunction "(PCINT6/XTAL1/TOSC1)PB6_7") (pintype "unspecified"))
      (node (ref "X1") (pin "3") (pinfunction "3_3") (pintype "input"))
    )
    (net (code "134") (name "Net-(U5-(PCINT7{slash}XTAL2{slash}TOSC2)PB7)") (class "Default")
      (node (ref "C5") (pin "2") (pinfunction "2_2") (pintype "unspecified"))
      (node (ref "U5") (pin "8") (pinfunction "(PCINT7/XTAL2/TOSC2)PB7_8") (pintype "unspecified"))
      (node (ref "X1") (pin "1") (pinfunction "1_1") (pintype "input"))
    )
    (net (code "135") (name "Net-(U5-AREF)") (class "Default")
      (node (ref "C3") (pin "1") (pinfunction "1_1") (pintype "unspecified"))
      (node (ref "U5") (pin "20") (pinfunction "AREF_20") (pintype "unspecified"))
    )
    (net (code "136") (name "Net-(U6-V3)") (class "Default")
      (node (ref "C38") (pin "1") (pinfunction "1_1") (pintype "unspecified"))
      (node (ref "U6") (pin "4") (pinfunction "V3_4") (pintype "unspecified"))
    )
    (net (code "137") (name "Net-(U9-IN)") (class "Default")
      (node (ref "R55") (pin "2") (pinfunction "2_2") (pintype "unspecified"))
      (node (ref "U9") (pin "2") (pinfunction "IN_2") (pintype "unspecified"))
    )
    (net (code "138") (name "Net-(U9-SR)") (class "Default")
      (node (ref "R11") (pin "2") (pinfunction "2_2") (pintype "input"))
      (node (ref "U9") (pin "5") (pinfunction "SR_5") (pintype "unspecified"))
    )
    (net (code "139") (name "Net-(U10-IN)") (class "Default")
      (node (ref "R62") (pin "1") (pinfunction "1_1") (pintype "unspecified"))
      (node (ref "U10") (pin "2") (pinfunction "IN_2") (pintype "unspecified"))
    )
    (net (code "140") (name "Net-(U10-SR)") (class "Default")
      (node (ref "R21") (pin "1") (pinfunction "1_1") (pintype "input"))
      (node (ref "U10") (pin "5") (pinfunction "SR_5") (pintype "unspecified"))
    )
    (net (code "141") (name "Net-(U11-PIO0_5{slash}CAN0_TD)") (class "Default")
      (node (ref "R83") (pin "2") (pinfunction "2_2") (pintype "input"))
      (node (ref "U11") (pin "89") (pinfunction "PIO0_5/CAN0_TD_89") (pintype "bidirectional"))
    )
    (net (code "142") (name "Net-(U11-PIO0_6{slash}FC3_SCK)") (class "Default")
      (node (ref "BOOT") (pin "1") (pinfunction "1_1") (pintype "unspecified"))
      (node (ref "R83") (pin "1") (pinfunction "1_1") (pintype "input"))
      (node (ref "U11") (pin "90") (pinfunction "PIO0_6/FC3_SCK_90") (pintype "bidirectional"))
    )
    (net (code "143") (name "Net-(U11-PIO0_23{slash}SPIFI_CSN)") (class "Default")
      (node (ref "R84") (pin "2") (pinfunction "2_2") (pintype "input"))
      (node (ref "U11") (pin "35") (pinfunction "PIO0_23/SPIFI_CSN_35") (pintype "bidirectional"))
    )
    (net (code "144") (name "Net-(U11-PIO0_24{slash}SPIFI_IO0)") (class "Default")
      (node (ref "R87") (pin "2") (pinfunction "2_2") (pintype "input"))
      (node (ref "U11") (pin "38") (pinfunction "PIO0_24/SPIFI_IO0_38") (pintype "bidirectional"))
    )
    (net (code "145") (name "Net-(U11-PIO1_8{slash}SD_CLK)") (class "Default")
      (node (ref "R85") (pin "2") (pinfunction "2_2") (pintype "input"))
      (node (ref "U11") (pin "36") (pinfunction "PIO1_8/SD_CLK_36") (pintype "bidirectional"))
    )
    (net (code "146") (name "Net-(U11-PIO1_21{slash}FC4_RXD_SDA_MOSI)") (class "Default")
      (node (ref "R86") (pin "2") (pinfunction "2_2") (pintype "input"))
      (node (ref "U11") (pin "37") (pinfunction "PIO1_21/FC4_RXD_SDA_MOSI_37") (pintype "bidirectional"))
    )
    (net (code "147") (name "Net-(U11-USB1_REXT)") (class "Default")
      (node (ref "R80") (pin "1") (pinfunction "1_1") (pintype "input"))
      (node (ref "U11") (pin "7") (pinfunction "USB1_REXT_7") (pintype "unspecified"))
    )
    (net (code "148") (name "Net-(U11-XTALIN)") (class "Default")
      (node (ref "C39") (pin "2") (pinfunction "2_2") (pintype "input"))
      (node (ref "U11") (pin "20") (pinfunction "XTALIN_20") (pintype "unspecified"))
      (node (ref "X3") (pin "3") (pinfunction "OSC2_3") (pintype "unspecified"))
    )
    (net (code "149") (name "Net-(U11-XTALOUT)") (class "Default")
      (node (ref "C37") (pin "2") (pinfunction "2_2") (pintype "input"))
      (node (ref "U11") (pin "19") (pinfunction "XTALOUT_19") (pintype "unspecified"))
      (node (ref "X3") (pin "1") (pinfunction "OSC1_1") (pintype "unspecified"))
    )
    (net (code "150") (name "Net-(U13-BOOT)") (class "Default")
      (node (ref "C11") (pin "1") (pinfunction "1_1") (pintype "unspecified"))
      (node (ref "U13") (pin "6") (pinfunction "BOOT_6") (pintype "unspecified"))
    )
    (net (code "151") (name "Net-(U13-FB)") (class "Default")
      (node (ref "C62") (pin "1") (pinfunction "1_1") (pintype "input"))
      (node (ref "R19") (pin "1") (pinfunction "1_1") (pintype "input"))
      (node (ref "R99") (pin "1") (pinfunction "1_1") (pintype "input"))
      (node (ref "U13") (pin "4") (pinfunction "FB_4") (pintype "unspecified"))
    )
    (net (code "152") (name "Net-(U13-SW)") (class "Default")
      (node (ref "C11") (pin "2") (pinfunction "2_2") (pintype "unspecified"))
      (node (ref "L1") (pin "1") (pinfunction "1_1") (pintype "unspecified"))
      (node (ref "U13") (pin "2") (pinfunction "SW_2") (pintype "unspecified"))
    )
    (net (code "153") (name "Net-(U16-Ant1{slash}{slash})") (class "Default")
      (node (ref "R56") (pin "2") (pinfunction "2_2") (pintype "input"))
      (node (ref "U16") (pin "7") (pinfunction "Ant1//_7") (pintype "unspecified"))
    )
    (net (code "154") (name "Net-(U16-Ant2{slash}CANRX{slash}{slash})") (class "Default")
      (node (ref "R52") (pin "2") (pinfunction "2_2") (pintype "input"))
      (node (ref "U16") (pin "10") (pinfunction "Ant2/CANRX//_10") (pintype "unspecified"))
    )
    (net (code "155") (name "Net-(U16-SCLK{slash}{slash})") (class "Default")
      (node (ref "R98") (pin "2") (pinfunction "2_2") (pintype "input"))
      (node (ref "U16") (pin "21") (pinfunction "SCLK//_21") (pintype "unspecified"))
    )
    (net (code "156") (name "Net-(U18-BYP)") (class "Default")
      (node (ref "C8") (pin "2") (pinfunction "2_2") (pintype "unspecified"))
      (node (ref "U18") (pin "2") (pinfunction "BYP_2") (pintype "unspecified"))
    )
    (net (code "157") (name "Net-(U19-V3)") (class "Default")
      (node (ref "C58") (pin "1") (pinfunction "1_1") (pintype "unspecified"))
      (node (ref "U19") (pin "4") (pinfunction "V3_4") (pintype "unspecified"))
    )
    (net (code "158") (name "Net-(USB:-K)") (class "Default")
      (node (ref "R14") (pin "2") (pinfunction "2_2") (pintype "input"))
      (node (ref "USB:") (pin "1") (pinfunction "K_1") (pintype "input"))
    )
    (net (code "159") (name "Net-(WAS2-K)") (class "Default")
      (node (ref "R58") (pin "2") (pinfunction "2_2") (pintype "input"))
      (node (ref "WAS2") (pin "1") (pinfunction "K_1") (pintype "input"))
    )
    (net (code "160") (name "Net-(WAS3-K)") (class "Default")
      (node (ref "R57") (pin "2") (pinfunction "2_2") (pintype "input"))
      (node (ref "WAS3") (pin "1") (pinfunction "K_1") (pintype "input"))
    )
    (net (code "161") (name "Net-(WIFI--)") (class "Default")
      (node (ref "R95") (pin "2") (pinfunction "2_2") (pintype "input"))
      (node (ref "WIFI") (pin "1") (pinfunction "-_1") (pintype "input"))
    )
    (net (code "162") (name "Net-(WORK-K)") (class "Default")
      (node (ref "R45") (pin "1") (pinfunction "1_1") (pintype "input"))
      (node (ref "WORK") (pin "1") (pinfunction "K_1") (pintype "input"))
    )
    (net (code "163") (name "Out") (class "Default")
      (node (ref "J8") (pin "1") (pinfunction "1_1") (pintype "unspecified"))
      (node (ref "Q6") (pin "3") (pinfunction "D_3") (pintype "unspecified"))
    )
    (net (code "164") (name "Rot+") (class "Default")
      (node (ref "CN1") (pin "1") (pinfunction "1_1") (pintype "unspecified"))
      (node (ref "F6") (pin "2") (pinfunction "2_2") (pintype "unspecified"))
      (node (ref "R75") (pin "2") (pinfunction "2_2") (pintype "input"))
      (node (ref "ROTARY/485") (pin "1") (pinfunction "+_1") (pintype "unspecified"))
    )
    (net (code "165") (name "RxD485") (class "Default")
      (node (ref "Q11") (pin "1") (pinfunction "1_1") (pintype "input"))
      (node (ref "R66") (pin "2") (pinfunction "2_2") (pintype "input"))
      (node (ref "U6") (pin "3") (pinfunction "RXD_3") (pintype "unspecified"))
      (node (ref "U8") (pin "1") (pinfunction "RO_1") (pintype "unspecified"))
    )
    (net (code "166") (name "RxDCAN") (class "Default")
      (node (ref "R68") (pin "2") (pinfunction "2_2") (pintype "input"))
      (node (ref "U1") (pin "12") (pinfunction "IO25_12") (pintype "unspecified"))
      (node (ref "U11") (pin "60") (pinfunction "PIO1_3/CAN0_RD_60") (pintype "bidirectional"))
      (node (ref "U7") (pin "4") (pinfunction "RXD_4") (pintype "unspecified"))
    )
    (net (code "167") (name "RxDCAN1") (class "Default")
      (node (ref "R89") (pin "2") (pinfunction "2_2") (pintype "input"))
      (node (ref "U11") (pin "5") (pinfunction "PIO1_18/FC8_TXD_SCL_MISO_5") (pintype "bidirectional"))
      (node (ref "U12") (pin "4") (pinfunction "RXD_4") (pintype "unspecified"))
    )
    (net (code "168") (name "RxD_ESP") (class "Default")
      (node (ref "Q11") (pin "2") (pinfunction "2_2") (pintype "input"))
      (node (ref "U1") (pin "7") (pinfunction "RXD_7") (pintype "unspecified"))
    )
    (net (code "169") (name "RxD_GNSS") (class "Default")
      (node (ref "ARDU1") (pin "2") (pinfunction "2_2") (pintype "unspecified"))
      (node (ref "U16") (pin "16") (pinfunction "RxD1_16") (pintype "unspecified"))
      (node (ref "U19") (pin "2") (pinfunction "TXD_2") (pintype "unspecified"))
    )
    (net (code "170") (name "SW!") (class "Default")
      (node (ref "C16") (pin "2") (pinfunction "2_2") (pintype "unspecified"))
      (node (ref "L7") (pin "1") (pinfunction "1_1") (pintype "unspecified"))
      (node (ref "U4") (pin "2") (pinfunction "SW_2") (pintype "unspecified"))
    )
    (net (code "171") (name "SWCLK") (class "Default")
      (node (ref "CN6") (pin "4") (pinfunction "4_4") (pintype "unspecified"))
      (node (ref "R78") (pin "2") (pinfunction "2_2") (pintype "input"))
      (node (ref "U11") (pin "24") (pinfunction "PIO0_11/SWCLK_24") (pintype "unspecified"))
    )
    (net (code "172") (name "SWDIO") (class "Default")
      (node (ref "CN6") (pin "2") (pinfunction "2_2") (pintype "unspecified"))
      (node (ref "R79") (pin "2") (pinfunction "2_2") (pintype "input"))
      (node (ref "U11") (pin "25") (pinfunction "PIO0_12/SWDIO_25") (pintype "unspecified"))
    )
    (net (code "173") (name "Servo+") (class "Default")
      (node (ref "CN18") (pin "3") (pinfunction "3_3") (pintype "unspecified"))
      (node (ref "F7") (pin "2") (pinfunction "2_2") (pintype "unspecified"))
      (node (ref "R76") (pin "1") (pinfunction "1_1") (pintype "input"))
      (node (ref "STEERING") (pin "1") (pinfunction "+_1") (pintype "unspecified"))
    )
    (net (code "174") (name "SteerEnable") (class "Default")
      (node (ref "J7") (pin "2") (pinfunction "2_2") (pintype "unspecified"))
      (node (ref "Q5") (pin "1") (pinfunction "G_1") (pintype "unspecified"))
      (node (ref "R16") (pin "1") (pinfunction "1_1") (pintype "input"))
      (node (ref "R63") (pin "2") (pinfunction "2_2") (pintype "unspecified"))
    )
    (net (code "175") (name "TxD485") (class "Default")
      (node (ref "R67") (pin "2") (pinfunction "2_2") (pintype "input"))
      (node (ref "U1") (pin "3") (pinfunction "TXD_3") (pintype "unspecified"))
      (node (ref "U6") (pin "2") (pinfunction "TXD_2") (pintype "unspecified"))
      (node (ref "U8") (pin "4") (pinfunction "DI_4") (pintype "unspecified"))
    )
    (net (code "176") (name "TxDCAN") (class "Default")
      (node (ref "R69") (pin "2") (pinfunction "2_2") (pintype "input"))
      (node (ref "U1") (pin "19") (pinfunction "IO17_19") (pintype "unspecified"))
      (node (ref "U11") (pin "58") (pinfunction "PIO1_2/CAN0_TD_58") (pintype "bidirectional"))
      (node (ref "U7") (pin "1") (pinfunction "TXD_1") (pintype "unspecified"))
    )
    (net (code "177") (name "TxDCAN1") (class "Default")
      (node (ref "R88") (pin "2") (pinfunction "2_2") (pintype "input"))
      (node (ref "U11") (pin "47") (pinfunction "PIO1_17/ENET_MDIO_47") (pintype "bidirectional"))
      (node (ref "U12") (pin "1") (pinfunction "TXD_1") (pintype "unspecified"))
    )
    (net (code "178") (name "TxD_GNSS") (class "Default")
      (node (ref "ARDU1") (pin "3") (pinfunction "3_3") (pintype "unspecified"))
      (node (ref "U16") (pin "15") (pinfunction "TxD1_15") (pintype "unspecified"))
      (node (ref "U19") (pin "3") (pinfunction "RXD_3") (pintype "unspecified"))
    )
    (net (code "179") (name "USB_Aux0_N") (class "Default")
      (node (ref "CN14") (pin "6") (pinfunction "6_6") (pintype "unspecified"))
      (node (ref "U2") (pin "8") (pinfunction "DM2_8") (pintype "unspecified"))
      (node (ref "U6") (pin "6") (pinfunction "UD-_6") (pintype "unspecified"))
      (node (ref "USB_AUX") (pin "6") (pinfunction "D-_6") (pintype "unspecified"))
    )
    (net (code "180") (name "USB_Aux0_P") (class "Default")
      (node (ref "CN14") (pin "5") (pinfunction "5_5") (pintype "unspecified"))
      (node (ref "U2") (pin "9") (pinfunction "DP2_9") (pintype "unspecified"))
      (node (ref "U6") (pin "5") (pinfunction "UD+_5") (pintype "unspecified"))
      (node (ref "USB_AUX") (pin "7") (pinfunction "D+_7") (pintype "unspecified"))
    )
    (net (code "181") (name "USB_Aux1_N") (class "Default")
      (node (ref "U11") (pin "12") (pinfunction "USB1_DM_12") (pintype "unspecified"))
      (node (ref "U2") (pin "6") (pinfunction "DM3_6") (pintype "unspecified"))
      (node (ref "USB_AUX") (pin "2") (pinfunction "D-_2") (pintype "unspecified"))
    )
    (net (code "182") (name "USB_Aux1_P") (class "Default")
      (node (ref "U11") (pin "13") (pinfunction "USB1_DP_13") (pintype "unspecified"))
      (node (ref "U2") (pin "7") (pinfunction "DP3_7") (pintype "unspecified"))
      (node (ref "USB_AUX") (pin "3") (pinfunction "D+_3") (pintype "unspecified"))
    )
    (net (code "183") (name "USB_Nano_N") (class "Default")
      (node (ref "U2") (pin "10") (pinfunction "DM1_10") (pintype "unspecified"))
      (node (ref "U3") (pin "6") (pinfunction "UD-_6") (pintype "unspecified"))
      (node (ref "UARDU") (pin "1") (pinfunction "1_1") (pintype "unspecified"))
    )
    (net (code "184") (name "USB_Nano_P") (class "Default")
      (node (ref "U2") (pin "11") (pinfunction "DP1_11") (pintype "unspecified"))
      (node (ref "U3") (pin "5") (pinfunction "UD+_5") (pintype "unspecified"))
      (node (ref "UARDU") (pin "2") (pinfunction "2_2") (pintype "unspecified"))
    )
    (net (code "185") (name "USB_RTU_N") (class "Default")
      (node (ref "J9") (pin "1") (pinfunction "1_1") (pintype "unspecified"))
      (node (ref "U19") (pin "6") (pinfunction "UD-_6") (pintype "unspecified"))
      (node (ref "U2") (pin "4") (pinfunction "DM4_4") (pintype "unspecified"))
      (node (ref "USB1") (pin "2") (pinfunction "D-_2") (pintype "input"))
    )
    (net (code "186") (name "USB_RTU_P") (class "Default")
      (node (ref "J9") (pin "2") (pinfunction "2_2") (pintype "unspecified"))
      (node (ref "U19") (pin "5") (pinfunction "UD+_5") (pintype "unspecified"))
      (node (ref "U2") (pin "5") (pinfunction "DP4_5") (pintype "unspecified"))
      (node (ref "USB1") (pin "3") (pinfunction "D+_3") (pintype "input"))
    )
    (net (code "187") (name "USB_Up_N") (class "Default")
      (node (ref "CN13") (pin "6") (pinfunction "6_6") (pintype "unspecified"))
      (node (ref "CN2") (pin "2") (pinfunction "2_2") (pintype "unspecified"))
      (node (ref "CN3") (pin "4") (pinfunction "4_4") (pintype "unspecified"))
      (node (ref "U2") (pin "15") (pinfunction "DMU_15") (pintype "unspecified"))
    )
    (net (code "188") (name "USB_Up_P") (class "Default")
      (node (ref "CN13") (pin "5") (pinfunction "5_5") (pintype "unspecified"))
      (node (ref "CN2") (pin "3") (pinfunction "3_3") (pintype "unspecified"))
      (node (ref "CN3") (pin "3") (pinfunction "3_3") (pintype "unspecified"))
      (node (ref "U2") (pin "16") (pinfunction "DPU_16") (pintype "unspecified"))
    )
    (net (code "189") (name "VBUS") (class "Default")
      (node (ref "CN10") (pin "3") (pinfunction "3_3") (pintype "unspecified"))
      (node (ref "CN8") (pin "3") (pinfunction "3_3") (pintype "unspecified"))
      (node (ref "CN9") (pin "3") (pinfunction "3_3") (pintype "unspecified"))
      (node (ref "DC/AUX") (pin "A4") (pinfunction "VBUS_A4") (pintype "unspecified"))
      (node (ref "DC/AUX") (pin "A9") (pinfunction "VBUS_A9") (pintype "unspecified"))
      (node (ref "DC/AUX") (pin "B4") (pinfunction "VBUS_B4") (pintype "unspecified"))
      (node (ref "DC/AUX") (pin "B9") (pinfunction "VBUS_B9") (pintype "unspecified"))
      (node (ref "TO_PC") (pin "A4") (pinfunction "VBUS_A4") (pintype "unspecified"))
      (node (ref "TO_PC") (pin "A9") (pinfunction "VBUS_A9") (pintype "unspecified"))
      (node (ref "TO_PC") (pin "B4") (pinfunction "VBUS_B4") (pintype "unspecified"))
      (node (ref "TO_PC") (pin "B9") (pinfunction "VBUS_B9") (pintype "unspecified"))
    )
    (net (code "190") (name "WAS") (class "Default")
      (node (ref "CN5") (pin "3") (pinfunction "3_3") (pintype "unspecified"))
      (node (ref "OP1") (pin "1") (pinfunction "1_1") (pintype "unspecified"))
      (node (ref "Q9") (pin "1") (pinfunction "1_1") (pintype "input"))
      (node (ref "R13") (pin "2") (pinfunction "2_2") (pintype "input"))
      (node (ref "WAS1") (pin "4") (pinfunction "4_4") (pintype "unspecified"))
    )
    (net (code "191") (name "WAS+") (class "Default")
      (node (ref "CN5") (pin "1") (pinfunction "1_1") (pintype "unspecified"))
      (node (ref "F5") (pin "2") (pinfunction "2_2") (pintype "unspecified"))
      (node (ref "R74") (pin "2") (pinfunction "2_2") (pintype "input"))
      (node (ref "WAS1") (pin "1") (pinfunction "+_1") (pintype "unspecified"))
    )
    (net (code "192") (name "WAS_0V") (class "Default")
      (node (ref "CN5") (pin "4") (pinfunction "4_4") (pintype "unspecified"))
      (node (ref "OP1") (pin "2") (pinfunction "2_2") (pintype "unspecified"))
      (node (ref "Q10") (pin "1") (pinfunction "1_1") (pintype "input"))
      (node (ref "R5") (pin "2") (pinfunction "2_2") (pintype "input"))
    )
    (net (code "193") (name "WAS_N") (class "Default")
      (node (ref "C33") (pin "2") (pinfunction "2_2") (pintype "unspecified"))
      (node (ref "R5") (pin "1") (pinfunction "1_1") (pintype "input"))
      (node (ref "U1") (pin "9") (pinfunction "SVN_9") (pintype "unspecified"))
      (node (ref "U17") (pin "5") (pinfunction "AIN1_5") (pintype "unspecified"))
    )
    (net (code "194") (name "WiFiLED") (class "Default")
      (node (ref "R95") (pin "1") (pinfunction "1_1") (pintype "input"))
      (node (ref "U1") (pin "28") (pinfunction "IO0_28") (pintype "unspecified"))
    )
    (net (code "195") (name "_Reset") (class "Default")
      (node (ref "C7") (pin "1") (pinfunction "1_1") (pintype "unspecified"))
      (node (ref "H1") (pin "2") (pinfunction "2_2") (pintype "unspecified"))
      (node (ref "R6") (pin "1") (pinfunction "1_1") (pintype "input"))
      (node (ref "U5") (pin "29") (pinfunction "PC6(RESET#/PCINT14)_29") (pintype "unspecified"))
    )
    (net (code "196") (name "_ResetNXP") (class "Default")
      (node (ref "CN6") (pin "10") (pinfunction "10_10") (pintype "unspecified"))
      (node (ref "U11") (pin "48") (pinfunction "RESETN_48") (pintype "unspecified"))
    )
    (net (code "197") (name "_RxD") (class "Default")
      (node (ref "R9") (pin "2") (pinfunction "2_2") (pintype "input"))
      (node (ref "RXD") (pin "1") (pinfunction "K_1") (pintype "input"))
      (node (ref "U3") (pin "2") (pinfunction "TXD_2") (pintype "unspecified"))
    )
    (net (code "198") (name "_TxD") (class "Default")
      (node (ref "R7") (pin "1") (pinfunction "1_1") (pintype "input"))
      (node (ref "U3") (pin "3") (pinfunction "RXD_3") (pintype "unspecified"))
    )
    (net (code "199") (name "_URES") (class "Default")
      (node (ref "R34") (pin "1") (pinfunction "1_1") (pintype "input"))
      (node (ref "U2") (pin "17") (pinfunction "XRSTJ_17") (pintype "unspecified"))
    )
    (net (code "200") (name "unconnected-(CN6-Pad6)") (class "Default")
      (node (ref "CN6") (pin "6") (pinfunction "6_6") (pintype "unspecified+no_connect"))
    )
    (net (code "201") (name "unconnected-(CN6-Pad7)") (class "Default")
      (node (ref "CN6") (pin "7") (pinfunction "7_7") (pintype "unspecified+no_connect"))
    )
    (net (code "202") (name "unconnected-(CN6-Pad8)") (class "Default")
      (node (ref "CN6") (pin "8") (pinfunction "8_8") (pintype "unspecified+no_connect"))
    )
    (net (code "203") (name "unconnected-(CN6-Pad11)") (class "Default")
      (node (ref "CN6") (pin "11") (pinfunction "11_11") (pintype "unspecified+no_connect"))
    )
    (net (code "204") (name "unconnected-(CN6-Pad12)") (class "Default")
      (node (ref "CN6") (pin "12") (pinfunction "12_12") (pintype "unspecified+no_connect"))
    )
    (net (code "205") (name "unconnected-(DC/AUX-SUB1-PadA8)") (class "Default")
      (node (ref "DC/AUX") (pin "A8") (pinfunction "SUB1_A8") (pintype "unspecified+no_connect"))
    )
    (net (code "206") (name "unconnected-(DC/AUX-SUB2-PadB8)") (class "Default")
      (node (ref "DC/AUX") (pin "B8") (pinfunction "SUB2_B8") (pintype "unspecified+no_connect"))
    )
    (net (code "207") (name "unconnected-(P1-Pad1)") (class "Default")
      (node (ref "P1") (pin "1") (pinfunction "1_1") (pintype "unspecified+no_connect"))
    )
    (net (code "208") (name "unconnected-(P1-Pad2)") (class "Default")
      (node (ref "P1") (pin "2") (pinfunction "2_2") (pintype "unspecified+no_connect"))
    )
    (net (code "209") (name "unconnected-(P1-Pad3)") (class "Default")
      (node (ref "P1") (pin "3") (pinfunction "3_3") (pintype "unspecified+no_connect"))
    )
    (net (code "210") (name "unconnected-(P1-Pad8)") (class "Default")
      (node (ref "P1") (pin "8") (pinfunction "8_8") (pintype "unspecified+no_connect"))
    )
    (net (code "211") (name "unconnected-(P2---Pad2)") (class "Default")
      (node (ref "P2") (pin "2") (pinfunction "-_2") (pintype "unspecified+no_connect"))
    )
    (net (code "212") (name "unconnected-(P2---Pad3)") (class "Default")
      (node (ref "P2") (pin "3") (pinfunction "-_3") (pintype "unspecified+no_connect"))
    )
    (net (code "213") (name "unconnected-(P2---Pad4)") (class "Default")
      (node (ref "P2") (pin "4") (pinfunction "-_4") (pintype "unspecified+no_connect"))
    )
    (net (code "214") (name "unconnected-(P2---Pad5)") (class "Default")
      (node (ref "P2") (pin "5") (pinfunction "-_5") (pintype "unspecified+no_connect"))
    )
    (net (code "215") (name "unconnected-(P2---Pad6)") (class "Default")
      (node (ref "P2") (pin "6") (pinfunction "-_6") (pintype "unspecified+no_connect"))
    )
    (net (code "216") (name "unconnected-(P2---Pad8)") (class "Default")
      (node (ref "P2") (pin "8") (pinfunction "-_8") (pintype "unspecified+no_connect"))
    )
    (net (code "217") (name "unconnected-(P2---Pad9)") (class "Default")
      (node (ref "P2") (pin "9") (pinfunction "-_9") (pintype "unspecified+no_connect"))
    )
    (net (code "218") (name "unconnected-(P2---Pad10)") (class "Default")
      (node (ref "P2") (pin "10") (pinfunction "-_10") (pintype "unspecified+no_connect"))
    )
    (net (code "219") (name "unconnected-(P2---Pad14)") (class "Default")
      (node (ref "P2") (pin "14") (pinfunction "-_14") (pintype "unspecified+no_connect"))
    )
    (net (code "220") (name "unconnected-(P2---Pad15)") (class "Default")
      (node (ref "P2") (pin "15") (pinfunction "-_15") (pintype "unspecified+no_connect"))
    )
    (net (code "221") (name "unconnected-(P2---Pad16)") (class "Default")
      (node (ref "P2") (pin "16") (pinfunction "-_16") (pintype "unspecified+no_connect"))
    )
    (net (code "222") (name "unconnected-(P2---Pad17)") (class "Default")
      (node (ref "P2") (pin "17") (pinfunction "-_17") (pintype "unspecified+no_connect"))
    )
    (net (code "223") (name "unconnected-(P2---Pad18)") (class "Default")
      (node (ref "P2") (pin "18") (pinfunction "-_18") (pintype "unspecified+no_connect"))
    )
    (net (code "224") (name "unconnected-(P2---Pad19)") (class "Default")
      (node (ref "P2") (pin "19") (pinfunction "-_19") (pintype "unspecified+no_connect"))
    )
    (net (code "225") (name "unconnected-(P2---Pad20)") (class "Default")
      (node (ref "P2") (pin "20") (pinfunction "-_20") (pintype "unspecified+no_connect"))
    )
    (net (code "226") (name "unconnected-(P2---Pad21)") (class "Default")
      (node (ref "P2") (pin "21") (pinfunction "-_21") (pintype "unspecified+no_connect"))
    )
    (net (code "227") (name "unconnected-(P2---Pad22)") (class "Default")
      (node (ref "P2") (pin "22") (pinfunction "-_22") (pintype "unspecified+no_connect"))
    )
    (net (code "228") (name "unconnected-(P2---Pad23)") (class "Default")
      (node (ref "P2") (pin "23") (pinfunction "-_23") (pintype "unspecified+no_connect"))
    )
    (net (code "229") (name "unconnected-(P2---Pad24)") (class "Default")
      (node (ref "P2") (pin "24") (pinfunction "-_24") (pintype "unspecified+no_connect"))
    )
    (net (code "230") (name "unconnected-(P2---Pad25)") (class "Default")
      (node (ref "P2") (pin "25") (pinfunction "-_25") (pintype "unspecified+no_connect"))
    )
    (net (code "231") (name "unconnected-(P2---Pad27)") (class "Default")
      (node (ref "P2") (pin "27") (pinfunction "-_27") (pintype "unspecified+no_connect"))
    )
    (net (code "232") (name "unconnected-(P2---Pad28)") (class "Default")
      (node (ref "P2") (pin "28") (pinfunction "-_28") (pintype "unspecified+no_connect"))
    )
    (net (code "233") (name "unconnected-(P2---Pad32)") (class "Default")
      (node (ref "P2") (pin "32") (pinfunction "-_32") (pintype "unspecified+no_connect"))
    )
    (net (code "234") (name "unconnected-(P2-5V_IN-Pad29)") (class "Default")
      (node (ref "P2") (pin "29") (pinfunction "5V_IN_29") (pintype "unspecified+no_connect"))
    )
    (net (code "235") (name "unconnected-(P2-GND-Pad7)") (class "Default")
      (node (ref "P2") (pin "7") (pinfunction "GND_7") (pintype "unspecified+no_connect"))
    )
    (net (code "236") (name "unconnected-(P2-GND-Pad30)") (class "Default")
      (node (ref "P2") (pin "30") (pinfunction "GND_30") (pintype "unspecified+no_connect"))
    )
    (net (code "237") (name "unconnected-(P2-GND-Pad31)") (class "Default")
      (node (ref "P2") (pin "31") (pinfunction "GND_31") (pintype "unspecified+no_connect"))
    )
    (net (code "238") (name "unconnected-(P2-IOREF-Pad26)") (class "Default")
      (node (ref "P2") (pin "26") (pinfunction "IOREF_26") (pintype "unspecified+no_connect"))
    )
    (net (code "239") (name "unconnected-(P2-RX1-Pad12)") (class "Default")
      (node (ref "P2") (pin "12") (pinfunction "RX1_12") (pintype "unspecified+no_connect"))
    )
    (net (code "240") (name "unconnected-(P2-RX2-Pad1)") (class "Default")
      (node (ref "P2") (pin "1") (pinfunction "RX2_1") (pintype "unspecified+no_connect"))
    )
    (net (code "241") (name "unconnected-(P2-TX1-Pad11)") (class "Default")
      (node (ref "P2") (pin "11") (pinfunction "TX1_11") (pintype "unspecified+no_connect"))
    )
    (net (code "242") (name "unconnected-(P2-TX2-Pad13)") (class "Default")
      (node (ref "P2") (pin "13") (pinfunction "TX2_13") (pintype "unspecified+no_connect"))
    )
    (net (code "243") (name "unconnected-(Q7-Pad2)") (class "Default")
      (node (ref "Q7") (pin "2") (pinfunction "2_2") (pintype "input+no_connect"))
    )
    (net (code "244") (name "unconnected-(TO_PC-SUB1-PadA8)") (class "Default")
      (node (ref "TO_PC") (pin "A8") (pinfunction "SUB1_A8") (pintype "unspecified+no_connect"))
    )
    (net (code "245") (name "unconnected-(TO_PC-SUB2-PadB8)") (class "Default")
      (node (ref "TO_PC") (pin "B8") (pinfunction "SUB2_B8") (pintype "unspecified+no_connect"))
    )
    (net (code "246") (name "unconnected-(U1-CLK-Pad40)") (class "Default")
      (node (ref "U1") (pin "40") (pinfunction "CLK_40") (pintype "unspecified+no_connect"))
    )
    (net (code "247") (name "unconnected-(U1-CMD-Pad37)") (class "Default")
      (node (ref "U1") (pin "37") (pinfunction "CMD_37") (pintype "unspecified+no_connect"))
    )
    (net (code "248") (name "unconnected-(U1-NC-Pad5)") (class "Default")
      (node (ref "U1") (pin "5") (pinfunction "NC_5") (pintype "unspecified+no_connect"))
    )
    (net (code "249") (name "unconnected-(U1-NC-Pad29)") (class "Default")
      (node (ref "U1") (pin "29") (pinfunction "NC_29") (pintype "unspecified+no_connect"))
    )
    (net (code "250") (name "unconnected-(U1-SD0-Pad39)") (class "Default")
      (node (ref "U1") (pin "39") (pinfunction "SD0_39") (pintype "unspecified+no_connect"))
    )
    (net (code "251") (name "unconnected-(U1-SD1-Pad36)") (class "Default")
      (node (ref "U1") (pin "36") (pinfunction "SD1_36") (pintype "unspecified+no_connect"))
    )
    (net (code "252") (name "unconnected-(U1-SD2-Pad33)") (class "Default")
      (node (ref "U1") (pin "33") (pinfunction "SD2_33") (pintype "unspecified+no_connect"))
    )
    (net (code "253") (name "unconnected-(U1-SD3-Pad38)") (class "Default")
      (node (ref "U1") (pin "38") (pinfunction "SD3_38") (pintype "unspecified+no_connect"))
    )
    (net (code "254") (name "unconnected-(U1-TCK-Pad34)") (class "Default")
      (node (ref "U1") (pin "34") (pinfunction "TCK_34") (pintype "unspecified+no_connect"))
    )
    (net (code "255") (name "unconnected-(U1-TD0-Pad35)") (class "Default")
      (node (ref "U1") (pin "35") (pinfunction "TD0_35") (pintype "unspecified+no_connect"))
    )
    (net (code "256") (name "unconnected-(U1-TDI-Pad20)") (class "Default")
      (node (ref "U1") (pin "20") (pinfunction "TDI_20") (pintype "unspecified+no_connect"))
    )
    (net (code "257") (name "unconnected-(U1-TMS-Pad25)") (class "Default")
      (node (ref "U1") (pin "25") (pinfunction "TMS_25") (pintype "unspecified+no_connect"))
    )
    (net (code "258") (name "unconnected-(U2-PWRJ-Pad25)") (class "Default")
      (node (ref "U2") (pin "25") (pinfunction "PWRJ_25") (pintype "unspecified+no_connect"))
    )
    (net (code "259") (name "unconnected-(U3-CTS#-Pad9)") (class "Default")
      (node (ref "U3") (pin "9") (pinfunction "CTS#_9") (pintype "unspecified+no_connect"))
    )
    (net (code "260") (name "unconnected-(U3-DCD#-Pad12)") (class "Default")
      (node (ref "U3") (pin "12") (pinfunction "DCD#_12") (pintype "unspecified+no_connect"))
    )
    (net (code "261") (name "unconnected-(U3-DSR#-Pad10)") (class "Default")
      (node (ref "U3") (pin "10") (pinfunction "DSR#_10") (pintype "unspecified+no_connect"))
    )
    (net (code "262") (name "unconnected-(U3-NC.-Pad8)") (class "Default")
      (node (ref "U3") (pin "8") (pinfunction "NC._8") (pintype "unspecified+no_connect"))
    )
    (net (code "263") (name "unconnected-(U3-RI#-Pad11)") (class "Default")
      (node (ref "U3") (pin "11") (pinfunction "RI#_11") (pintype "unspecified+no_connect"))
    )
    (net (code "264") (name "unconnected-(U3-RST#-Pad7)") (class "Default")
      (node (ref "U3") (pin "7") (pinfunction "RST#_7") (pintype "unspecified+no_connect"))
    )
    (net (code "265") (name "unconnected-(U3-RTS#-Pad14)") (class "Default")
      (node (ref "U3") (pin "14") (pinfunction "RTS#_14") (pintype "unspecified+no_connect"))
    )
    (net (code "266") (name "unconnected-(U3-TNOW-Pad15)") (class "Default")
      (node (ref "U3") (pin "15") (pinfunction "TNOW_15") (pintype "unspecified+no_connect"))
    )
    (net (code "267") (name "unconnected-(U5-ADC6-Pad19)") (class "Default")
      (node (ref "U5") (pin "19") (pinfunction "ADC6_19") (pintype "unspecified+no_connect"))
    )
    (net (code "268") (name "unconnected-(U6-CTS#-Pad9)") (class "Default")
      (node (ref "U6") (pin "9") (pinfunction "CTS#_9") (pintype "unspecified+no_connect"))
    )
    (net (code "269") (name "unconnected-(U6-DCD#-Pad12)") (class "Default")
      (node (ref "U6") (pin "12") (pinfunction "DCD#_12") (pintype "unspecified+no_connect"))
    )
    (net (code "270") (name "unconnected-(U6-DSR#-Pad10)") (class "Default")
      (node (ref "U6") (pin "10") (pinfunction "DSR#_10") (pintype "unspecified+no_connect"))
    )
    (net (code "271") (name "unconnected-(U6-DTR#-Pad13)") (class "Default")
      (node (ref "U6") (pin "13") (pinfunction "DTR#_13") (pintype "unspecified+no_connect"))
    )
    (net (code "272") (name "unconnected-(U6-NC.-Pad8)") (class "Default")
      (node (ref "U6") (pin "8") (pinfunction "NC._8") (pintype "unspecified+no_connect"))
    )
    (net (code "273") (name "unconnected-(U6-RI#-Pad11)") (class "Default")
      (node (ref "U6") (pin "11") (pinfunction "RI#_11") (pintype "unspecified+no_connect"))
    )
    (net (code "274") (name "unconnected-(U6-RST#-Pad7)") (class "Default")
      (node (ref "U6") (pin "7") (pinfunction "RST#_7") (pintype "unspecified+no_connect"))
    )
    (net (code "275") (name "unconnected-(U6-RTS#-Pad14)") (class "Default")
      (node (ref "U6") (pin "14") (pinfunction "RTS#_14") (pintype "unspecified+no_connect"))
    )
    (net (code "276") (name "unconnected-(U10-OUT-Pad4)") (class "Default")
      (node (ref "U10") (pin "4") (pinfunction "OUT_4") (pintype "unspecified+no_connect"))
    )
    (net (code "277") (name "unconnected-(U11-PIO0_0{slash}CAN1_RD-Pad93)") (class "Default")
      (node (ref "U11") (pin "93") (pinfunction "PIO0_0/CAN1_RD_93") (pintype "bidirectional+no_connect"))
    )
    (net (code "278") (name "unconnected-(U11-PIO0_1{slash}CAN1_TD-Pad100)") (class "Default")
      (node (ref "U11") (pin "100") (pinfunction "PIO0_1/CAN1_TD_100") (pintype "bidirectional+no_connect"))
    )
    (net (code "279") (name "unconnected-(U11-PIO0_2{slash}FC3_TXD_SCL_MISO-Pad83)") (class "Default")
      (node (ref "U11") (pin "83") (pinfunction "PIO0_2/FC3_TXD_SCL_MISO_83") (pintype "bidirectional+no_connect"))
    )
    (net (code "280") (name "unconnected-(U11-PIO0_3{slash}FC3_RXD_SDA_MOSI-Pad85)") (class "Default")
      (node (ref "U11") (pin "85") (pinfunction "PIO0_3/FC3_RXD_SDA_MOSI_85") (pintype "bidirectional+no_connect"))
    )
    (net (code "281") (name "unconnected-(U11-PIO0_4{slash}CAN0_RD-Pad87)") (class "Default")
      (node (ref "U11") (pin "87") (pinfunction "PIO0_4/CAN0_RD_87") (pintype "bidirectional+no_connect"))
    )
    (net (code "282") (name "unconnected-(U11-PIO0_7{slash}FC5_SCK-Pad61)") (class "Default")
      (node (ref "U11") (pin "61") (pinfunction "PIO0_7/FC5_SCK_61") (pintype "bidirectional+no_connect"))
    )
    (net (code "283") (name "unconnected-(U11-PIO0_8{slash}FC5_RXD_SDA_MOSI-Pad64)") (class "Default")
      (node (ref "U11") (pin "64") (pinfunction "PIO0_8/FC5_RXD_SDA_MOSI_64") (pintype "bidirectional+no_connect"))
    )
    (net (code "284") (name "unconnected-(U11-PIO0_9{slash}FC5_TXD_SCL_MISO-Pad65)") (class "Default")
      (node (ref "U11") (pin "65") (pinfunction "PIO0_9/FC5_TXD_SCL_MISO_65") (pintype "bidirectional+no_connect"))
    )
    (net (code "285") (name "unconnected-(U11-PIO0_10{slash}SWO-Pad23)") (class "Default")
      (node (ref "U11") (pin "23") (pinfunction "PIO0_10/SWO_23") (pintype "unspecified+no_connect"))
    )
    (net (code "286") (name "unconnected-(U11-PIO0_13{slash}FC1_CTS_SDA_SSEL0-Pad67)") (class "Default")
      (node (ref "U11") (pin "67") (pinfunction "PIO0_13/FC1_CTS_SDA_SSEL0_67") (pintype "bidirectional+no_connect"))
    )
    (net (code "287") (name "unconnected-(U11-PIO0_14{slash}FC1_RTS_SCL_SSEL1-Pad69)") (class "Default")
      (node (ref "U11") (pin "69") (pinfunction "PIO0_14/FC1_RTS_SCL_SSEL1_69") (pintype "bidirectional+no_connect"))
    )
    (net (code "288") (name "unconnected-(U11-PIO0_15{slash}ADC0_3-Pad26)") (class "Default")
      (node (ref "U11") (pin "26") (pinfunction "PIO0_15/ADC0_3_26") (pintype "bidirectional+no_connect"))
    )
    (net (code "289") (name "unconnected-(U11-PIO0_16{slash}ADC0_4-Pad27)") (class "Default")
      (node (ref "U11") (pin "27") (pinfunction "PIO0_16/ADC0_4_27") (pintype "bidirectional+no_connect"))
    )
    (net (code "290") (name "unconnected-(U11-PIO0_17{slash}FC4_SSEL2-Pad70)") (class "Default")
      (node (ref "U11") (pin "70") (pinfunction "PIO0_17/FC4_SSEL2_70") (pintype "bidirectional+no_connect"))
    )
    (net (code "291") (name "unconnected-(U11-PIO0_18{slash}FC4_CTS_SDA_SSEL0-Pad72)") (class "Default")
      (node (ref "U11") (pin "72") (pinfunction "PIO0_18/FC4_CTS_SDA_SSEL0_72") (pintype "bidirectional+no_connect"))
    )
    (net (code "292") (name "unconnected-(U11-PIO0_19{slash}FC4_RTS_SCL_SSEL1-Pad91)") (class "Default")
      (node (ref "U11") (pin "91") (pinfunction "PIO0_19/FC4_RTS_SCL_SSEL1_91") (pintype "bidirectional+no_connect"))
    )
    (net (code "293") (name "unconnected-(U11-PIO0_20{slash}FC3_CTS_SDA_SSEL0-Pad74)") (class "Default")
      (node (ref "U11") (pin "74") (pinfunction "PIO0_20/FC3_CTS_SDA_SSEL0_74") (pintype "bidirectional+no_connect"))
    )
    (net (code "294") (name "unconnected-(U11-PIO0_21{slash}FC3_RTS_SCL_SSEL1-Pad77)") (class "Default")
      (node (ref "U11") (pin "77") (pinfunction "PIO0_21/FC3_RTS_SCL_SSEL1_77") (pintype "bidirectional+no_connect"))
    )
    (net (code "295") (name "unconnected-(U11-PIO0_22{slash}FC6_TXD_SCL_MISO_WS-Pad80)") (class "Default")
      (node (ref "U11") (pin "80") (pinfunction "PIO0_22/FC6_TXD_SCL_MISO_WS_80") (pintype "bidirectional+no_connect"))
    )
    (net (code "296") (name "unconnected-(U11-PIO0_25{slash}SPIFI_IO1-Pad40)") (class "Default")
      (node (ref "U11") (pin "40") (pinfunction "PIO0_25/SPIFI_IO1_40") (pintype "bidirectional+no_connect"))
    )
    (net (code "297") (name "unconnected-(U11-PIO0_26{slash}SPIFI_CLK-Pad56)") (class "Default")
      (node (ref "U11") (pin "56") (pinfunction "PIO0_26/SPIFI_CLK_56") (pintype "bidirectional+no_connect"))
    )
    (net (code "298") (name "unconnected-(U11-PIO0_27{slash}SPIFI_IO3-Pad42)") (class "Default")
      (node (ref "U11") (pin "42") (pinfunction "PIO0_27/SPIFI_IO3_42") (pintype "bidirectional+no_connect"))
    )
    (net (code "299") (name "unconnected-(U11-PIO0_28{slash}SPIFI_IO2-Pad44)") (class "Default")
      (node (ref "U11") (pin "44") (pinfunction "PIO0_28/SPIFI_IO2_44") (pintype "bidirectional+no_connect"))
    )
    (net (code "300") (name "unconnected-(U11-PIO0_29{slash}FC0_RXD_SDA_MOSI-Pad82)") (class "Default")
      (node (ref "U11") (pin "82") (pinfunction "PIO0_29/FC0_RXD_SDA_MOSI_82") (pintype "bidirectional+no_connect"))
    )
    (net (code "301") (name "unconnected-(U11-PIO0_30{slash}PIO0_30-Pad95)") (class "Default")
      (node (ref "U11") (pin "95") (pinfunction "PIO0_30/PIO0_30_95") (pintype "bidirectional+no_connect"))
    )
    (net (code "302") (name "unconnected-(U11-PIO0_31{slash}SD_D2-Pad28)") (class "Default")
      (node (ref "U11") (pin "28") (pinfunction "PIO0_31/SD_D2_28") (pintype "bidirectional+no_connect"))
    )
    (net (code "303") (name "unconnected-(U11-PIO1_0{slash}SD_D3-Pad29)") (class "Default")
      (node (ref "U11") (pin "29") (pinfunction "PIO1_0/SD_D3_29") (pintype "bidirectional+no_connect"))
    )
    (net (code "304") (name "unconnected-(U11-PIO1_1{slash}FC3_RXD_SDA_MOSI-Pad55)") (class "Default")
      (node (ref "U11") (pin "55") (pinfunction "PIO1_1/FC3_RXD_SDA_MOSI_55") (pintype "bidirectional+no_connect"))
    )
    (net (code "305") (name "unconnected-(U11-PIO1_4{slash}SD_D0-Pad3)") (class "Default")
      (node (ref "U11") (pin "3") (pinfunction "PIO1_4/SD_D0_3") (pintype "bidirectional+no_connect"))
    )
    (net (code "306") (name "unconnected-(U11-PIO1_5{slash}FC0_RXD_SDA_MOSI-Pad4)") (class "Default")
      (node (ref "U11") (pin "4") (pinfunction "PIO1_5/FC0_RXD_SDA_MOSI_4") (pintype "bidirectional+no_connect"))
    )
    (net (code "307") (name "unconnected-(U11-PIO1_6{slash}FC0_TXD_SCL_MISO-Pad15)") (class "Default")
      (node (ref "U11") (pin "15") (pinfunction "PIO1_6/FC0_TXD_SCL_MISO_15") (pintype "bidirectional+no_connect"))
    )
    (net (code "308") (name "unconnected-(U11-PIO1_7{slash}SD_D1-Pad18)") (class "Default")
      (node (ref "U11") (pin "18") (pinfunction "PIO1_7/SD_D1_18") (pintype "bidirectional+no_connect"))
    )
    (net (code "309") (name "unconnected-(U11-PIO1_9{slash}FC4_CTS_SDA_SSEL0-Pad39)") (class "Default")
      (node (ref "U11") (pin "39") (pinfunction "PIO1_9/FC4_CTS_SDA_SSEL0_39") (pintype "bidirectional+no_connect"))
    )
    (net (code "310") (name "unconnected-(U11-PIO1_10{slash}ENET_TXD1-Pad41)") (class "Default")
      (node (ref "U11") (pin "41") (pinfunction "PIO1_10/ENET_TXD1_41") (pintype "bidirectional+no_connect"))
    )
    (net (code "311") (name "unconnected-(U11-PIO1_11{slash}ENET_TX_EN-Pad94)") (class "Default")
      (node (ref "U11") (pin "94") (pinfunction "PIO1_11/ENET_TX_EN_94") (pintype "bidirectional+no_connect"))
    )
    (net (code "312") (name "unconnected-(U11-PIO1_12{slash}ENET_RXD0-Pad62)") (class "Default")
      (node (ref "U11") (pin "62") (pinfunction "PIO1_12/ENET_RXD0_62") (pintype "bidirectional+no_connect"))
    )
    (net (code "313") (name "unconnected-(U11-PIO1_13{slash}ENET_RXD1-Pad66)") (class "Default")
      (node (ref "U11") (pin "66") (pinfunction "PIO1_13/ENET_RXD1_66") (pintype "bidirectional+no_connect"))
    )
    (net (code "314") (name "unconnected-(U11-PIO1_14{slash}FC5_CTS_SDA_SSEL0-Pad78)") (class "Default")
      (node (ref "U11") (pin "78") (pinfunction "PIO1_14/FC5_CTS_SDA_SSEL0_78") (pintype "bidirectional+no_connect"))
    )
    (net (code "315") (name "unconnected-(U11-PIO1_15{slash}ENET_RX_CLK-Pad84)") (class "Default")
      (node (ref "U11") (pin "84") (pinfunction "PIO1_15/ENET_RX_CLK_84") (pintype "bidirectional+no_connect"))
    )
    (net (code "316") (name "unconnected-(U11-PIO1_16{slash}ENET_MDC-Pad88)") (class "Default")
      (node (ref "U11") (pin "88") (pinfunction "PIO1_16/ENET_MDC_88") (pintype "bidirectional+no_connect"))
    )
    (net (code "317") (name "unconnected-(U11-PIO1_19{slash}FC4_SCK-Pad16)") (class "Default")
      (node (ref "U11") (pin "16") (pinfunction "PIO1_19/FC4_SCK_16") (pintype "bidirectional+no_connect"))
    )
    (net (code "318") (name "unconnected-(U11-PIO1_20{slash}FC4_TXD_SCL_MISO-Pad17)") (class "Default")
      (node (ref "U11") (pin "17") (pinfunction "PIO1_20/FC4_TXD_SCL_MISO_17") (pintype "bidirectional+no_connect"))
    )
    (net (code "319") (name "unconnected-(U11-PIO1_22{slash}SD_CMD-Pad43)") (class "Default")
      (node (ref "U11") (pin "43") (pinfunction "PIO1_22/SD_CMD_43") (pintype "bidirectional+no_connect"))
    )
    (net (code "320") (name "unconnected-(U11-PIO1_23{slash}FC2_SCK-Pad46)") (class "Default")
      (node (ref "U11") (pin "46") (pinfunction "PIO1_23/FC2_SCK_46") (pintype "bidirectional+no_connect"))
    )
    (net (code "321") (name "unconnected-(U11-PIO1_24{slash}FC2_RXD_SDA_MOSI-Pad57)") (class "Default")
      (node (ref "U11") (pin "57") (pinfunction "PIO1_24/FC2_RXD_SDA_MOSI_57") (pintype "bidirectional+no_connect"))
    )
    (net (code "322") (name "unconnected-(U11-PIO1_25{slash}FC2_TXD_SCL_MISO-Pad59)") (class "Default")
      (node (ref "U11") (pin "59") (pinfunction "PIO1_25/FC2_TXD_SCL_MISO_59") (pintype "bidirectional+no_connect"))
    )
    (net (code "323") (name "unconnected-(U11-PIO1_26{slash}FC2_CTS_SDA_SSEL0-Pad63)") (class "Default")
      (node (ref "U11") (pin "63") (pinfunction "PIO1_26/FC2_CTS_SDA_SSEL0_63") (pintype "bidirectional+no_connect"))
    )
    (net (code "324") (name "unconnected-(U11-PIO1_27{slash}CLKOUT-Pad68)") (class "Default")
      (node (ref "U11") (pin "68") (pinfunction "PIO1_27/CLKOUT_68") (pintype "bidirectional+no_connect"))
    )
    (net (code "325") (name "unconnected-(U11-PIO1_28{slash}FC7_SCK-Pad73)") (class "Default")
      (node (ref "U11") (pin "73") (pinfunction "PIO1_28/FC7_SCK_73") (pintype "bidirectional+no_connect"))
    )
    (net (code "326") (name "unconnected-(U11-PIO1_29{slash}FC7_RXD_SDA_MOSI_DATA-Pad81)") (class "Default")
      (node (ref "U11") (pin "81") (pinfunction "PIO1_29/FC7_RXD_SDA_MOSI_DATA_81") (pintype "bidirectional+no_connect"))
    )
    (net (code "327") (name "unconnected-(U11-PIO1_30{slash}USB1_UP_LED-Pad86)") (class "Default")
      (node (ref "U11") (pin "86") (pinfunction "PIO1_30/USB1_UP_LED_86") (pintype "bidirectional+no_connect"))
    )
    (net (code "328") (name "unconnected-(U11-PIO1_31{slash}MCLK-Pad92)") (class "Default")
      (node (ref "U11") (pin "92") (pinfunction "PIO1_31/MCLK_92") (pintype "bidirectional+no_connect"))
    )
    (net (code "329") (name "unconnected-(U11-RTCXOUT-Pad52)") (class "Default")
      (node (ref "U11") (pin "52") (pinfunction "RTCXOUT_52") (pintype "unspecified+no_connect"))
    )
    (net (code "330") (name "unconnected-(U11-USB0_DM-Pad98)") (class "Default")
      (node (ref "U11") (pin "98") (pinfunction "USB0_DM_98") (pintype "unspecified+no_connect"))
    )
    (net (code "331") (name "unconnected-(U11-USB0_DP-Pad97)") (class "Default")
      (node (ref "U11") (pin "97") (pinfunction "USB0_DP_97") (pintype "unspecified+no_connect"))
    )
    (net (code "332") (name "unconnected-(U11-USB1_ID-Pad8)") (class "Default")
      (node (ref "U11") (pin "8") (pinfunction "USB1_ID_8") (pintype "unspecified+no_connect"))
    )
    (net (code "333") (name "unconnected-(U14-NC-Pad5)") (class "Default")
      (node (ref "U14") (pin "5") (pinfunction "NC_5") (pintype "unspecified+no_connect"))
    )
    (net (code "334") (name "unconnected-(U15-Factory_Use-Pad5)") (class "Default")
      (node (ref "U15") (pin "5") (pinfunction "Factory_Use_5") (pintype "input+no_connect"))
    )
    (net (code "335") (name "unconnected-(U15-Mode-Pad4)") (class "Default")
      (node (ref "U15") (pin "4") (pinfunction "Mode_4") (pintype "input+no_connect"))
    )
    (net (code "336") (name "unconnected-(U16-Bias-Pad4)") (class "Default")
      (node (ref "U16") (pin "4") (pinfunction "Bias_4") (pintype "unspecified+no_connect"))
    )
    (net (code "337") (name "unconnected-(U16-CAN2RX-Pad12)") (class "Default")
      (node (ref "U16") (pin "12") (pinfunction "CAN2RX_12") (pintype "unspecified+no_connect"))
    )
    (net (code "338") (name "unconnected-(U16-CAN2TX{slash}{slash}-Pad24)") (class "Default")
      (node (ref "U16") (pin "24") (pinfunction "CAN2TX//_24") (pintype "unspecified+no_connect"))
    )
    (net (code "339") (name "unconnected-(U16-CANTX{slash}{slash}-Pad11)") (class "Default")
      (node (ref "U16") (pin "11") (pinfunction "CANTX//_11") (pintype "unspecified+no_connect"))
    )
    (net (code "340") (name "unconnected-(U16-Link_Act-Pad3)") (class "Default")
      (node (ref "U16") (pin "3") (pinfunction "Link_Act_3") (pintype "unspecified+no_connect"))
    )
    (net (code "341") (name "unconnected-(U16-MISO{slash}RxD3-Pad8)") (class "Default")
      (node (ref "U16") (pin "8") (pinfunction "MISO/RxD3_8") (pintype "unspecified+no_connect"))
    )
    (net (code "342") (name "unconnected-(U16-MOSI{slash}SDA-Pad1)") (class "Default")
      (node (ref "U16") (pin "1") (pinfunction "MOSI/SDA_1") (pintype "unspecified+no_connect"))
    )
    (net (code "343") (name "unconnected-(U16-PPS-Pad23)") (class "Default")
      (node (ref "U16") (pin "23") (pinfunction "PPS_23") (pintype "unspecified+no_connect"))
    )
    (net (code "344") (name "unconnected-(U16-RD+-Pad26)") (class "Default")
      (node (ref "U16") (pin "26") (pinfunction "RD+_26") (pintype "unspecified+no_connect"))
    )
    (net (code "345") (name "unconnected-(U16-RD--Pad28)") (class "Default")
      (node (ref "U16") (pin "28") (pinfunction "RD-_28") (pintype "unspecified+no_connect"))
    )
    (net (code "346") (name "unconnected-(U16-RxD2{slash}{slash}-Pad19)") (class "Default")
      (node (ref "U16") (pin "19") (pinfunction "RxD2//_19") (pintype "unspecified+no_connect"))
    )
    (net (code "347") (name "unconnected-(U16-TD+-Pad25)") (class "Default")
      (node (ref "U16") (pin "25") (pinfunction "TD+_25") (pintype "unspecified+no_connect"))
    )
    (net (code "348") (name "unconnected-(U16-TD--Pad27)") (class "Default")
      (node (ref "U16") (pin "27") (pinfunction "TD-_27") (pintype "unspecified+no_connect"))
    )
    (net (code "349") (name "unconnected-(U16-TxD2{slash}{slash}-Pad18)") (class "Default")
      (node (ref "U16") (pin "18") (pinfunction "TxD2//_18") (pintype "unspecified+no_connect"))
    )
    (net (code "350") (name "unconnected-(U16-TxD3-Pad13)") (class "Default")
      (node (ref "U16") (pin "13") (pinfunction "TxD3_13") (pintype "unspecified+no_connect"))
    )
    (net (code "351") (name "unconnected-(U16-_CS{slash}SCL-Pad2)") (class "Default")
      (node (ref "U16") (pin "2") (pinfunction "_CS/SCL_2") (pintype "unspecified+no_connect"))
    )
    (net (code "352") (name "unconnected-(U16-_Reset-Pad9)") (class "Default")
      (node (ref "U16") (pin "9") (pinfunction "_Reset_9") (pintype "unspecified+no_connect"))
    )
    (net (code "353") (name "unconnected-(U16-n.c.-Pad5)") (class "Default")
      (node (ref "U16") (pin "5") (pinfunction "n.c._5") (pintype "unspecified+no_connect"))
    )
    (net (code "354") (name "unconnected-(U17-ALERT{slash}RDY-Pad2)") (class "Default")
      (node (ref "U17") (pin "2") (pinfunction "ALERT/RDY_2") (pintype "unspecified+no_connect"))
    )
    (net (code "355") (name "unconnected-(U18-INT1-Pad11)") (class "Default")
      (node (ref "U18") (pin "11") (pinfunction "INT1_11") (pintype "unspecified+no_connect"))
    )
    (net (code "356") (name "unconnected-(U18-INT2-Pad9)") (class "Default")
      (node (ref "U18") (pin "9") (pinfunction "INT2_9") (pintype "unspecified+no_connect"))
    )
    (net (code "357") (name "unconnected-(U18-NC-Pad3)") (class "Default")
      (node (ref "U18") (pin "3") (pinfunction "NC_3") (pintype "unspecified+no_connect"))
    )
    (net (code "358") (name "unconnected-(U18-NC-Pad8)") (class "Default")
      (node (ref "U18") (pin "8") (pinfunction "NC_8") (pintype "unspecified+no_connect"))
    )
    (net (code "359") (name "unconnected-(U18-NC-Pad13)") (class "Default")
      (node (ref "U18") (pin "13") (pinfunction "NC_13") (pintype "unspecified+no_connect"))
    )
    (net (code "360") (name "unconnected-(U18-NC-Pad15)") (class "Default")
      (node (ref "U18") (pin "15") (pinfunction "NC_15") (pintype "unspecified+no_connect"))
    )
    (net (code "361") (name "unconnected-(U18-NC-Pad16)") (class "Default")
      (node (ref "U18") (pin "16") (pinfunction "NC_16") (pintype "unspecified+no_connect"))
    )
    (net (code "362") (name "unconnected-(U19-CTS#-Pad9)") (class "Default")
      (node (ref "U19") (pin "9") (pinfunction "CTS#_9") (pintype "unspecified+no_connect"))
    )
    (net (code "363") (name "unconnected-(U19-DCD#-Pad12)") (class "Default")
      (node (ref "U19") (pin "12") (pinfunction "DCD#_12") (pintype "unspecified+no_connect"))
    )
    (net (code "364") (name "unconnected-(U19-DSR#-Pad10)") (class "Default")
      (node (ref "U19") (pin "10") (pinfunction "DSR#_10") (pintype "unspecified+no_connect"))
    )
    (net (code "365") (name "unconnected-(U19-DTR#-Pad13)") (class "Default")
      (node (ref "U19") (pin "13") (pinfunction "DTR#_13") (pintype "unspecified+no_connect"))
    )
    (net (code "366") (name "unconnected-(U19-NC.-Pad8)") (class "Default")
      (node (ref "U19") (pin "8") (pinfunction "NC._8") (pintype "unspecified+no_connect"))
    )
    (net (code "367") (name "unconnected-(U19-RI#-Pad11)") (class "Default")
      (node (ref "U19") (pin "11") (pinfunction "RI#_11") (pintype "unspecified+no_connect"))
    )
    (net (code "368") (name "unconnected-(U19-RST#-Pad7)") (class "Default")
      (node (ref "U19") (pin "7") (pinfunction "RST#_7") (pintype "unspecified+no_connect"))
    )
    (net (code "369") (name "unconnected-(U19-RTS#-Pad14)") (class "Default")
      (node (ref "U19") (pin "14") (pinfunction "RTS#_14") (pintype "unspecified+no_connect"))
    )
    (net (code "370") (name "unconnected-(U19-TNOW-Pad15)") (class "Default")
      (node (ref "U19") (pin "15") (pinfunction "TNOW_15") (pintype "unspecified+no_connect"))
    )
  )
)
